# VC8E.net
KiCad netlist of a schematic drawn in EAGLE
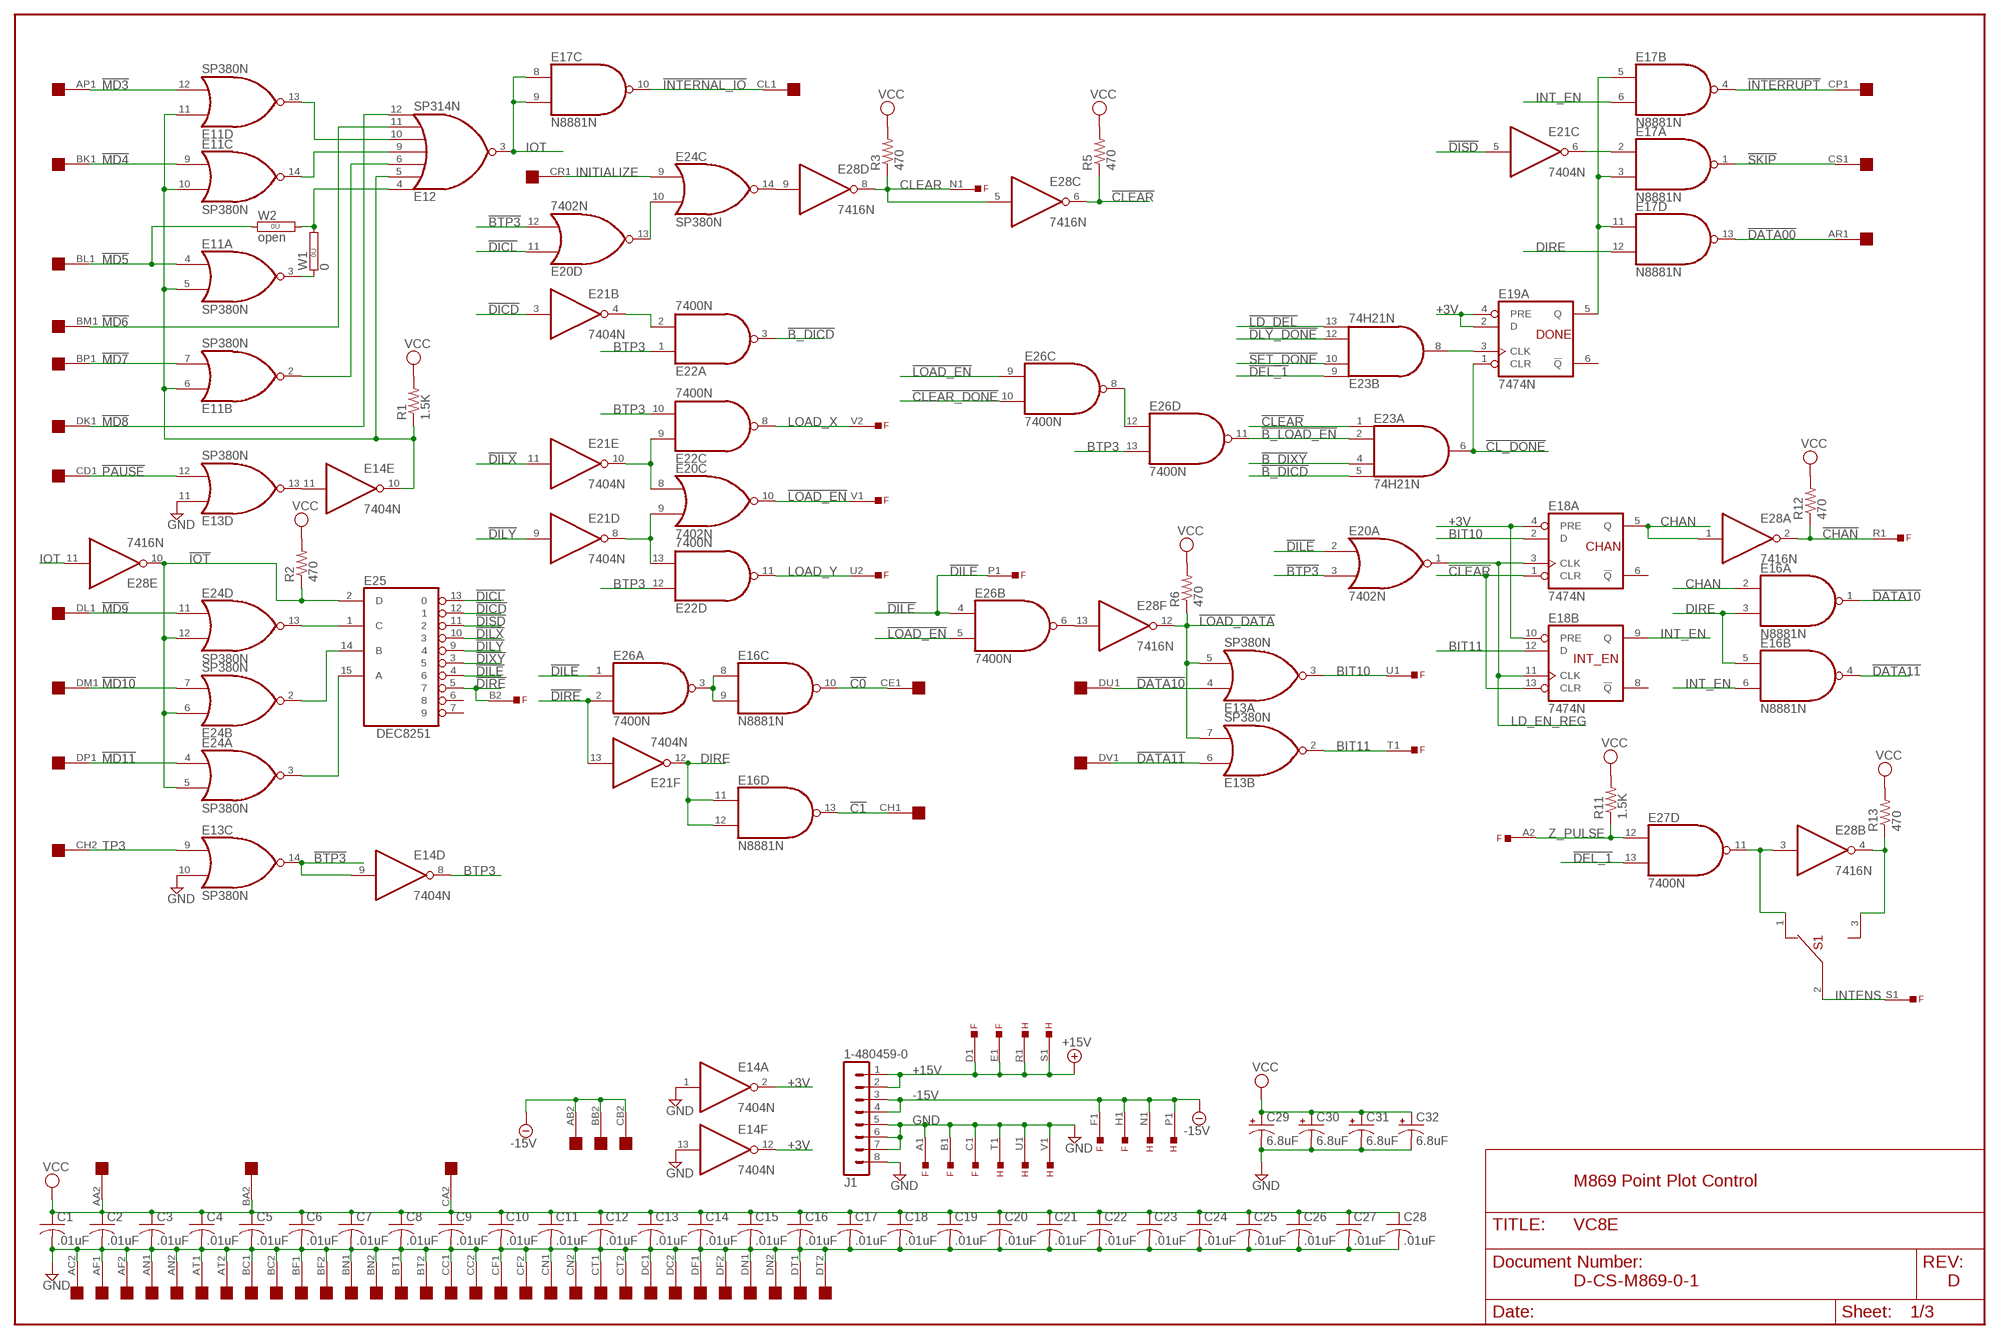
[diagram p0: schematic, sheet 1]
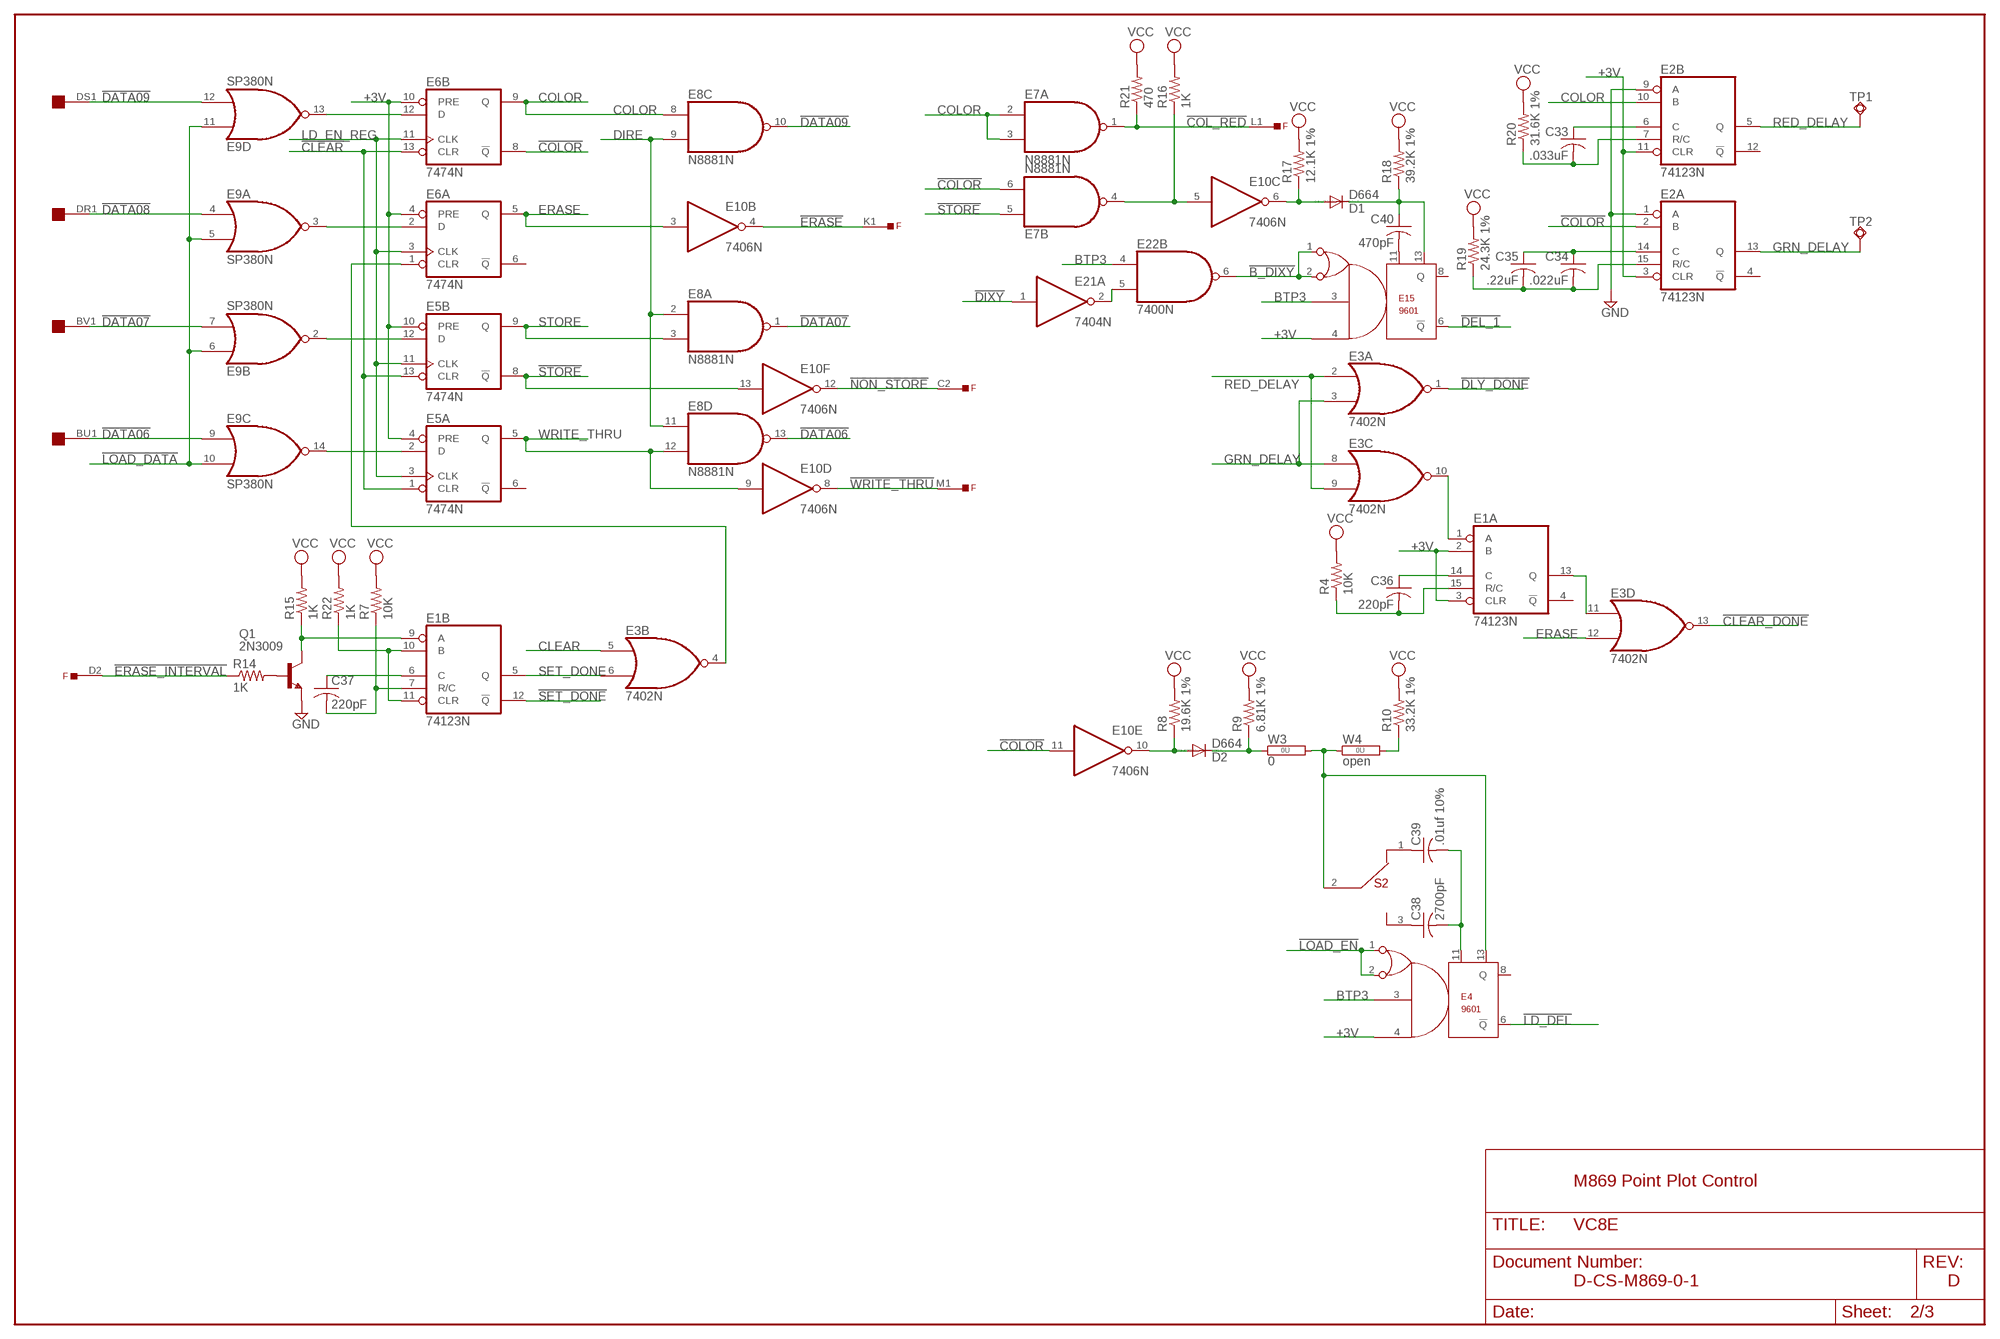
[diagram p1: schematic, sheet 2]
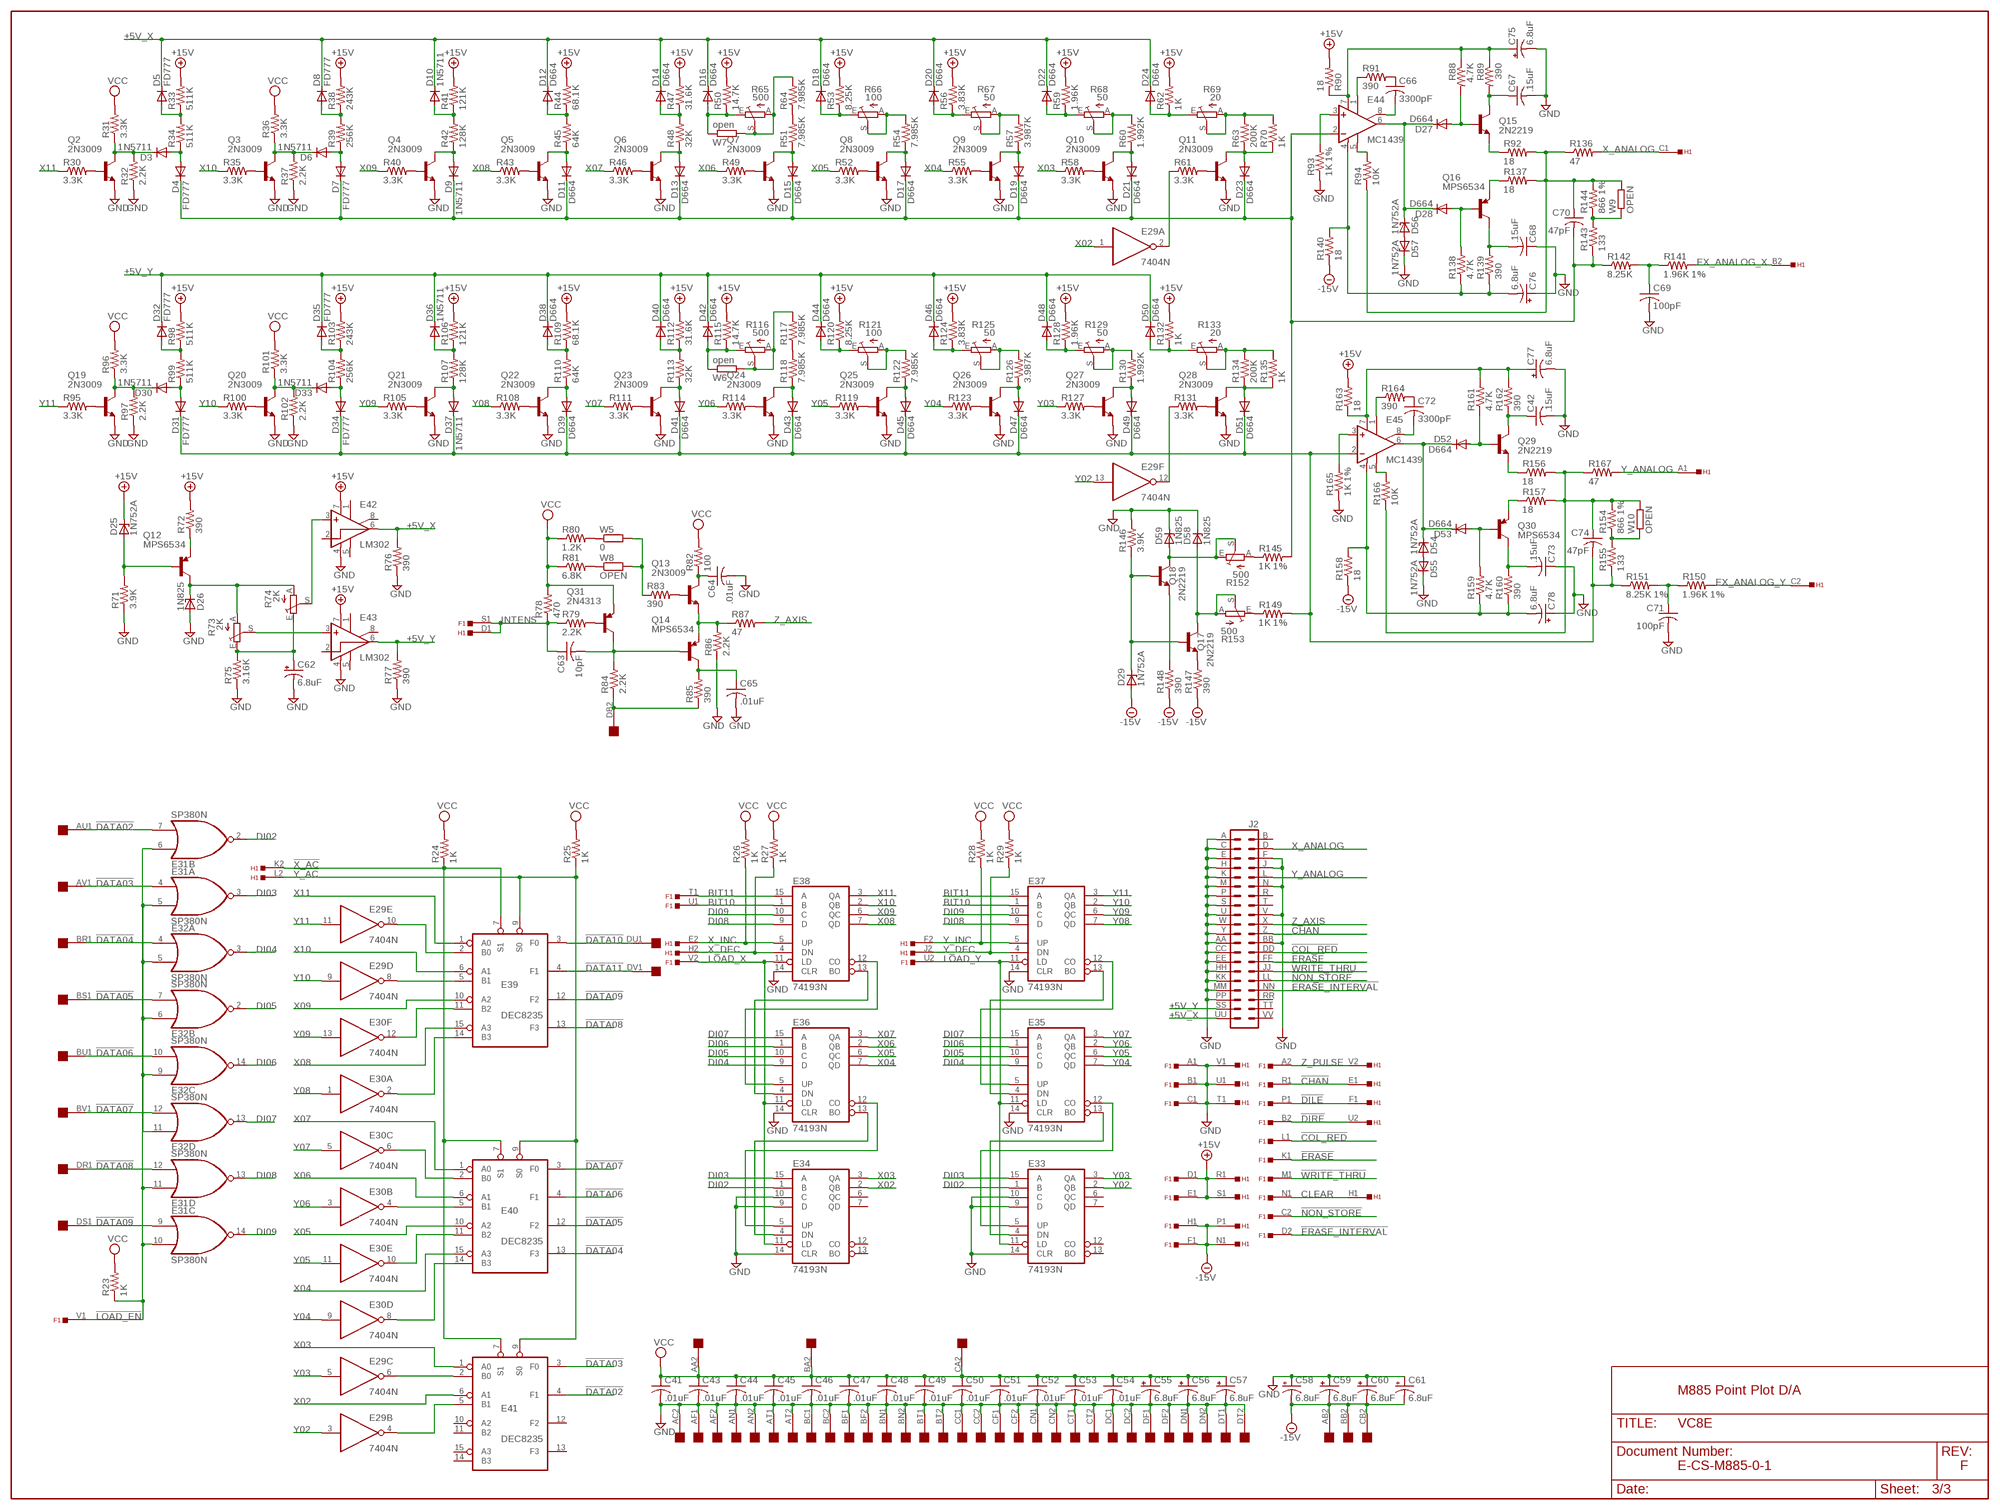
[diagram p2: schematic, sheet 3]

(export (version "E")
  (design (tool "Eeschema 10.0.6"))
  (components
    (comp (ref "C41")
      (value ".01uF")
      (footprint "eagle-import:C063-025X075")
      (libsource (lib "eagle-import") (part "C-US"))
    )
    (comp (ref "C42")
      (value ".15uF")
      (footprint "eagle-import:C150-054X183")
      (libsource (lib "eagle-import") (part "C-US150-054X183"))
    )
    (comp (ref "C43")
      (value ".01uF")
      (footprint "eagle-import:C063-025X075")
      (libsource (lib "eagle-import") (part "C-US"))
    )
    (comp (ref "C44")
      (value ".01uF")
      (footprint "eagle-import:C063-025X075")
      (libsource (lib "eagle-import") (part "C-US"))
    )
    (comp (ref "C45")
      (value ".01uF")
      (footprint "eagle-import:C063-025X075")
      (libsource (lib "eagle-import") (part "C-US"))
    )
    (comp (ref "C46")
      (value ".01uF")
      (footprint "eagle-import:C063-025X075")
      (libsource (lib "eagle-import") (part "C-US"))
    )
    (comp (ref "C47")
      (value ".01uF")
      (footprint "eagle-import:C063-025X075")
      (libsource (lib "eagle-import") (part "C-US"))
    )
    (comp (ref "C48")
      (value ".01uF")
      (footprint "eagle-import:C063-025X075")
      (libsource (lib "eagle-import") (part "C-US"))
    )
    (comp (ref "C49")
      (value ".01uF")
      (footprint "eagle-import:C063-025X075")
      (libsource (lib "eagle-import") (part "C-US"))
    )
    (comp (ref "C50")
      (value ".01uF")
      (footprint "eagle-import:C063-025X075")
      (libsource (lib "eagle-import") (part "C-US"))
    )
    (comp (ref "C51")
      (value ".01uF")
      (footprint "eagle-import:C063-025X075")
      (libsource (lib "eagle-import") (part "C-US"))
    )
    (comp (ref "C52")
      (value ".01uF")
      (footprint "eagle-import:C063-025X075")
      (libsource (lib "eagle-import") (part "C-US"))
    )
    (comp (ref "C53")
      (value ".01uF")
      (footprint "eagle-import:C063-025X075")
      (libsource (lib "eagle-import") (part "C-US"))
    )
    (comp (ref "C54")
      (value ".01uF")
      (footprint "eagle-import:C063-025X075")
      (libsource (lib "eagle-import") (part "C-US"))
    )
    (comp (ref "C55")
      (value "6.8uF")
      (footprint "eagle-import:E12-8")
      (libsource (lib "eagle-import") (part "CPOL-USE20-8AXIAL"))
    )
    (comp (ref "C56")
      (value "6.8uF")
      (footprint "eagle-import:E12-8")
      (libsource (lib "eagle-import") (part "CPOL-USE20-8AXIAL"))
    )
    (comp (ref "C57")
      (value "6.8uF")
      (footprint "eagle-import:E12-8")
      (libsource (lib "eagle-import") (part "CPOL-USE20-8AXIAL"))
    )
    (comp (ref "C58")
      (value "6.8uF")
      (footprint "eagle-import:E12-8")
      (libsource (lib "eagle-import") (part "CPOL-USE20-8AXIAL"))
    )
    (comp (ref "C59")
      (value "6.8uF")
      (footprint "eagle-import:E12-8")
      (libsource (lib "eagle-import") (part "CPOL-USE20-8AXIAL"))
    )
    (comp (ref "C60")
      (value "6.8uF")
      (footprint "eagle-import:E12-8")
      (libsource (lib "eagle-import") (part "CPOL-USE20-8AXIAL"))
    )
    (comp (ref "C61")
      (value "6.8uF")
      (footprint "eagle-import:E12-8")
      (libsource (lib "eagle-import") (part "CPOL-USE20-8AXIAL"))
    )
    (comp (ref "C62")
      (value "6.8uF")
      (footprint "eagle-import:E12-8")
      (libsource (lib "eagle-import") (part "CPOL-USE20-8AXIAL"))
    )
    (comp (ref "C63")
      (value "10pF")
      (footprint "eagle-import:C063-025X075")
      (libsource (lib "eagle-import") (part "C-US"))
    )
    (comp (ref "C64")
      (value ".01uF")
      (footprint "eagle-import:C063-025X075")
      (libsource (lib "eagle-import") (part "C-US"))
    )
    (comp (ref "C65")
      (value ".01uF")
      (footprint "eagle-import:C063-025X075")
      (libsource (lib "eagle-import") (part "C-US"))
    )
    (comp (ref "C66")
      (value "3300pF")
      (footprint "eagle-import:C150-054X183")
      (libsource (lib "eagle-import") (part "C-US150-054X183"))
    )
    (comp (ref "C67")
      (value ".15uF")
      (footprint "eagle-import:C150-054X183")
      (libsource (lib "eagle-import") (part "C-US150-054X183"))
    )
    (comp (ref "C68")
      (value ".15uF")
      (footprint "eagle-import:C150-054X183")
      (libsource (lib "eagle-import") (part "C-US150-054X183"))
    )
    (comp (ref "C69")
      (value "100pF")
      (footprint "eagle-import:C063-025X075")
      (libsource (lib "eagle-import") (part "C-US"))
    )
    (comp (ref "C70")
      (value "47pF")
      (footprint "eagle-import:C063-025X075")
      (libsource (lib "eagle-import") (part "C-US"))
    )
    (comp (ref "C71")
      (value "100pF")
      (footprint "eagle-import:C063-025X075")
      (libsource (lib "eagle-import") (part "C-US"))
    )
    (comp (ref "C72")
      (value "3300pF")
      (footprint "eagle-import:C150-054X183")
      (libsource (lib "eagle-import") (part "C-US150-054X183"))
    )
    (comp (ref "C73")
      (value ".15uF")
      (footprint "eagle-import:C150-054X183")
      (libsource (lib "eagle-import") (part "C-US150-054X183"))
    )
    (comp (ref "C74")
      (value "47pF")
      (footprint "eagle-import:C063-025X075")
      (libsource (lib "eagle-import") (part "C-US"))
    )
    (comp (ref "C75")
      (value "6.8uF")
      (footprint "eagle-import:E12-8")
      (libsource (lib "eagle-import") (part "CPOL-USE20-8AXIAL"))
    )
    (comp (ref "C76")
      (value "6.8uF")
      (footprint "eagle-import:E12-8")
      (libsource (lib "eagle-import") (part "CPOL-USE20-8AXIAL"))
    )
    (comp (ref "C77")
      (value "6.8uF")
      (footprint "eagle-import:E12-8")
      (libsource (lib "eagle-import") (part "CPOL-USE20-8AXIAL"))
    )
    (comp (ref "C78")
      (value "6.8uF")
      (footprint "eagle-import:E12-8")
      (libsource (lib "eagle-import") (part "CPOL-USE20-8AXIAL"))
    )
    (comp (ref "D3")
      (value "1N5711")
      (footprint "eagle-import:DO35-10")
      (libsource (lib "eagle-import") (part "DIODE-DO35-10"))
    )
    (comp (ref "D4")
      (value "FD777")
      (footprint "eagle-import:DO35-10")
      (libsource (lib "eagle-import") (part "DIODE-DO35-10"))
    )
    (comp (ref "D5")
      (value "FD777")
      (footprint "eagle-import:DO35-10")
      (libsource (lib "eagle-import") (part "DIODE-DO35-10"))
    )
    (comp (ref "D6")
      (value "1N5711")
      (footprint "eagle-import:DO35-10")
      (libsource (lib "eagle-import") (part "DIODE-DO35-10"))
    )
    (comp (ref "D7")
      (value "FD777")
      (footprint "eagle-import:DO35-10")
      (libsource (lib "eagle-import") (part "DIODE-DO35-10"))
    )
    (comp (ref "D8")
      (value "FD777")
      (footprint "eagle-import:DO35-10")
      (libsource (lib "eagle-import") (part "DIODE-DO35-10"))
    )
    (comp (ref "D9")
      (value "1N5711")
      (footprint "eagle-import:DO35-10")
      (libsource (lib "eagle-import") (part "DIODE-DO35-10"))
    )
    (comp (ref "D10")
      (value "1N5711")
      (footprint "eagle-import:DO35-10")
      (libsource (lib "eagle-import") (part "DIODE-DO35-10"))
    )
    (comp (ref "D11")
      (value "D664")
      (footprint "eagle-import:DO35-10")
      (libsource (lib "eagle-import") (part "DIODE-DO35-10"))
    )
    (comp (ref "D12")
      (value "D664")
      (footprint "eagle-import:DO35-10")
      (libsource (lib "eagle-import") (part "DIODE-DO35-10"))
    )
    (comp (ref "D13")
      (value "D664")
      (footprint "eagle-import:DO35-10")
      (libsource (lib "eagle-import") (part "DIODE-DO35-10"))
    )
    (comp (ref "D14")
      (value "D664")
      (footprint "eagle-import:DO35-10")
      (libsource (lib "eagle-import") (part "DIODE-DO35-10"))
    )
    (comp (ref "D15")
      (value "D664")
      (footprint "eagle-import:DO35-10")
      (libsource (lib "eagle-import") (part "DIODE-DO35-10"))
    )
    (comp (ref "D16")
      (value "D664")
      (footprint "eagle-import:DO35-10")
      (libsource (lib "eagle-import") (part "DIODE-DO35-10"))
    )
    (comp (ref "D17")
      (value "D664")
      (footprint "eagle-import:DO35-10")
      (libsource (lib "eagle-import") (part "DIODE-DO35-10"))
    )
    (comp (ref "D18")
      (value "D664")
      (footprint "eagle-import:DO35-10")
      (libsource (lib "eagle-import") (part "DIODE-DO35-10"))
    )
    (comp (ref "D19")
      (value "D664")
      (footprint "eagle-import:DO35-10")
      (libsource (lib "eagle-import") (part "DIODE-DO35-10"))
    )
    (comp (ref "D20")
      (value "D664")
      (footprint "eagle-import:DO35-10")
      (libsource (lib "eagle-import") (part "DIODE-DO35-10"))
    )
    (comp (ref "D21")
      (value "D664")
      (footprint "eagle-import:DO35-10")
      (libsource (lib "eagle-import") (part "DIODE-DO35-10"))
    )
    (comp (ref "D22")
      (value "D664")
      (footprint "eagle-import:DO35-10")
      (libsource (lib "eagle-import") (part "DIODE-DO35-10"))
    )
    (comp (ref "D23")
      (value "D664")
      (footprint "eagle-import:DO35-10")
      (libsource (lib "eagle-import") (part "DIODE-DO35-10"))
    )
    (comp (ref "D24")
      (value "D664")
      (footprint "eagle-import:DO35-10")
      (libsource (lib "eagle-import") (part "DIODE-DO35-10"))
    )
    (comp (ref "D25")
      (value "1N752A")
      (footprint "eagle-import:DO35Z10")
      (libsource (lib "eagle-import") (part "ZENER-DIODEDO35Z10"))
    )
    (comp (ref "D26")
      (value "1N825")
      (footprint "eagle-import:DO35Z10")
      (libsource (lib "eagle-import") (part "ZENER-DIODEDO35Z10"))
    )
    (comp (ref "D27")
      (value "D664")
      (footprint "eagle-import:DO35-10")
      (libsource (lib "eagle-import") (part "DIODE-DO35-10"))
    )
    (comp (ref "D28")
      (value "D664")
      (footprint "eagle-import:DO35-10")
      (libsource (lib "eagle-import") (part "DIODE-DO35-10"))
    )
    (comp (ref "D29")
      (value "1N752A")
      (footprint "eagle-import:DO35Z10")
      (libsource (lib "eagle-import") (part "ZENER-DIODEDO35Z10"))
    )
    (comp (ref "D30")
      (value "1N5711")
      (footprint "eagle-import:DO35-10")
      (libsource (lib "eagle-import") (part "DIODE-DO35-10"))
    )
    (comp (ref "D31")
      (value "FD777")
      (footprint "eagle-import:DO35-10")
      (libsource (lib "eagle-import") (part "DIODE-DO35-10"))
    )
    (comp (ref "D32")
      (value "FD777")
      (footprint "eagle-import:DO35-10")
      (libsource (lib "eagle-import") (part "DIODE-DO35-10"))
    )
    (comp (ref "D33")
      (value "1N5711")
      (footprint "eagle-import:DO35-10")
      (libsource (lib "eagle-import") (part "DIODE-DO35-10"))
    )
    (comp (ref "D34")
      (value "FD777")
      (footprint "eagle-import:DO35-10")
      (libsource (lib "eagle-import") (part "DIODE-DO35-10"))
    )
    (comp (ref "D35")
      (value "FD777")
      (footprint "eagle-import:DO35-10")
      (libsource (lib "eagle-import") (part "DIODE-DO35-10"))
    )
    (comp (ref "D36")
      (value "1N5711")
      (footprint "eagle-import:DO35-10")
      (libsource (lib "eagle-import") (part "DIODE-DO35-10"))
    )
    (comp (ref "D37")
      (value "1N5711")
      (footprint "eagle-import:DO35-10")
      (libsource (lib "eagle-import") (part "DIODE-DO35-10"))
    )
    (comp (ref "D38")
      (value "D664")
      (footprint "eagle-import:DO35-10")
      (libsource (lib "eagle-import") (part "DIODE-DO35-10"))
    )
    (comp (ref "D39")
      (value "D664")
      (footprint "eagle-import:DO35-10")
      (libsource (lib "eagle-import") (part "DIODE-DO35-10"))
    )
    (comp (ref "D40")
      (value "D664")
      (footprint "eagle-import:DO35-10")
      (libsource (lib "eagle-import") (part "DIODE-DO35-10"))
    )
    (comp (ref "D41")
      (value "D664")
      (footprint "eagle-import:DO35-10")
      (libsource (lib "eagle-import") (part "DIODE-DO35-10"))
    )
    (comp (ref "D42")
      (value "D664")
      (footprint "eagle-import:DO35-10")
      (libsource (lib "eagle-import") (part "DIODE-DO35-10"))
    )
    (comp (ref "D43")
      (value "D664")
      (footprint "eagle-import:DO35-10")
      (libsource (lib "eagle-import") (part "DIODE-DO35-10"))
    )
    (comp (ref "D44")
      (value "D664")
      (footprint "eagle-import:DO35-10")
      (libsource (lib "eagle-import") (part "DIODE-DO35-10"))
    )
    (comp (ref "D45")
      (value "D664")
      (footprint "eagle-import:DO35-10")
      (libsource (lib "eagle-import") (part "DIODE-DO35-10"))
    )
    (comp (ref "D46")
      (value "D664")
      (footprint "eagle-import:DO35-10")
      (libsource (lib "eagle-import") (part "DIODE-DO35-10"))
    )
    (comp (ref "D47")
      (value "D664")
      (footprint "eagle-import:DO35-10")
      (libsource (lib "eagle-import") (part "DIODE-DO35-10"))
    )
    (comp (ref "D48")
      (value "D664")
      (footprint "eagle-import:DO35-10")
      (libsource (lib "eagle-import") (part "DIODE-DO35-10"))
    )
    (comp (ref "D49")
      (value "D664")
      (footprint "eagle-import:DO35-10")
      (libsource (lib "eagle-import") (part "DIODE-DO35-10"))
    )
    (comp (ref "D50")
      (value "D664")
      (footprint "eagle-import:DO35-10")
      (libsource (lib "eagle-import") (part "DIODE-DO35-10"))
    )
    (comp (ref "D51")
      (value "D664")
      (footprint "eagle-import:DO35-10")
      (libsource (lib "eagle-import") (part "DIODE-DO35-10"))
    )
    (comp (ref "D52")
      (value "D664")
      (footprint "eagle-import:DO35-10")
      (libsource (lib "eagle-import") (part "DIODE-DO35-10"))
    )
    (comp (ref "D53")
      (value "D664")
      (footprint "eagle-import:DO35-10")
      (libsource (lib "eagle-import") (part "DIODE-DO35-10"))
    )
    (comp (ref "D54")
      (value "1N752A")
      (footprint "eagle-import:DO35Z10")
      (libsource (lib "eagle-import") (part "ZENER-DIODEDO35Z10"))
    )
    (comp (ref "D55")
      (value "1N752A")
      (footprint "eagle-import:DO35Z10")
      (libsource (lib "eagle-import") (part "ZENER-DIODEDO35Z10"))
    )
    (comp (ref "D56")
      (value "1N752A")
      (footprint "eagle-import:DO35Z10")
      (libsource (lib "eagle-import") (part "ZENER-DIODEDO35Z10"))
    )
    (comp (ref "D57")
      (value "1N752A")
      (footprint "eagle-import:DO35Z10")
      (libsource (lib "eagle-import") (part "ZENER-DIODEDO35Z10"))
    )
    (comp (ref "D58")
      (value "1N825")
      (footprint "eagle-import:DO35Z10")
      (libsource (lib "eagle-import") (part "ZENER-DIODEDO35Z10"))
    )
    (comp (ref "D59")
      (value "1N825")
      (footprint "eagle-import:DO35Z10")
      (libsource (lib "eagle-import") (part "ZENER-DIODEDO35Z10"))
    )
    (comp (ref "E29")
      (value "7404N")
      (footprint "eagle-import:DIL14")
      (libsource (lib "eagle-import") (part "7404N"))
    )
    (comp (ref "E30")
      (value "7404N")
      (footprint "eagle-import:DIL14")
      (libsource (lib "eagle-import") (part "7404N"))
    )
    (comp (ref "E31")
      (value "SP380N")
      (footprint "eagle-import:DIL14")
      (libsource (lib "eagle-import") (part "SP380N"))
    )
    (comp (ref "E32")
      (value "SP380N")
      (footprint "eagle-import:DIL14")
      (libsource (lib "eagle-import") (part "SP380N"))
    )
    (comp (ref "E33")
      (value "74193N")
      (footprint "eagle-import:DIL16")
      (libsource (lib "eagle-import") (part "74193N"))
    )
    (comp (ref "E34")
      (value "74193N")
      (footprint "eagle-import:DIL16")
      (libsource (lib "eagle-import") (part "74193N"))
    )
    (comp (ref "E35")
      (value "74193N")
      (footprint "eagle-import:DIL16")
      (libsource (lib "eagle-import") (part "74193N"))
    )
    (comp (ref "E36")
      (value "74193N")
      (footprint "eagle-import:DIL16")
      (libsource (lib "eagle-import") (part "74193N"))
    )
    (comp (ref "E37")
      (value "74193N")
      (footprint "eagle-import:DIL16")
      (libsource (lib "eagle-import") (part "74193N"))
    )
    (comp (ref "E38")
      (value "74193N")
      (footprint "eagle-import:DIL16")
      (libsource (lib "eagle-import") (part "74193N"))
    )
    (comp (ref "E39")
      (value "DEC8235")
      (footprint "eagle-import:DIL16")
      (libsource (lib "eagle-import") (part "DEC8235"))
    )
    (comp (ref "E40")
      (value "DEC8235")
      (footprint "eagle-import:DIL16")
      (libsource (lib "eagle-import") (part "DEC8235"))
    )
    (comp (ref "E41")
      (value "DEC8235")
      (footprint "eagle-import:DIL16")
      (libsource (lib "eagle-import") (part "DEC8235"))
    )
    (comp (ref "E42")
      (value "LM302")
      (footprint "eagle-import:TO99")
      (libsource (lib "eagle-import") (part "AD504H"))
    )
    (comp (ref "E43")
      (value "LM302")
      (footprint "eagle-import:TO99")
      (libsource (lib "eagle-import") (part "AD504H"))
    )
    (comp (ref "E44")
      (value "MC1439")
      (footprint "eagle-import:TO99")
      (libsource (lib "eagle-import") (part "AD504H"))
    )
    (comp (ref "E45")
      (value "MC1439")
      (footprint "eagle-import:TO99")
      (libsource (lib "eagle-import") (part "AD504H"))
    )
    (comp (ref "F1")
      (value "EDGE-TOP")
      (footprint "eagle-import:EDGE-CON2")
      (libsource (lib "eagle-import") (part "EDGE-TOP"))
    )
    (comp (ref "H1")
      (value "EDGE-TOP")
      (footprint "eagle-import:EDGE-CON2")
      (libsource (lib "eagle-import") (part "EDGE-TOP"))
    )
    (comp (ref "J2")
      (value "DEC40PINH")
      (footprint "eagle-import:DEC40PINH")
      (libsource (lib "eagle-import") (part "DEC40PINH"))
    )
    (comp (ref "OMNIBUS1")
      (value "QUAD")
      (footprint "eagle-import:EDGE-CON8")
      (libsource (lib "eagle-import") (part "QUAD"))
    )
    (comp (ref "Q2")
      (value "2N3009")
      (footprint "eagle-import:TO5")
      (libsource (lib "eagle-import") (part "-NPN-TO5"))
    )
    (comp (ref "Q3")
      (value "2N3009")
      (footprint "eagle-import:TO5")
      (libsource (lib "eagle-import") (part "-NPN-TO5"))
    )
    (comp (ref "Q4")
      (value "2N3009")
      (footprint "eagle-import:TO5")
      (libsource (lib "eagle-import") (part "-NPN-TO5"))
    )
    (comp (ref "Q5")
      (value "2N3009")
      (footprint "eagle-import:TO5")
      (libsource (lib "eagle-import") (part "-NPN-TO5"))
    )
    (comp (ref "Q6")
      (value "2N3009")
      (footprint "eagle-import:TO5")
      (libsource (lib "eagle-import") (part "-NPN-TO5"))
    )
    (comp (ref "Q7")
      (value "2N3009")
      (footprint "eagle-import:TO5")
      (libsource (lib "eagle-import") (part "-NPN-TO5"))
    )
    (comp (ref "Q8")
      (value "2N3009")
      (footprint "eagle-import:TO5")
      (libsource (lib "eagle-import") (part "-NPN-TO5"))
    )
    (comp (ref "Q9")
      (value "2N3009")
      (footprint "eagle-import:TO5")
      (libsource (lib "eagle-import") (part "-NPN-TO5"))
    )
    (comp (ref "Q10")
      (value "2N3009")
      (footprint "eagle-import:TO5")
      (libsource (lib "eagle-import") (part "-NPN-TO5"))
    )
    (comp (ref "Q11")
      (value "2N3009")
      (footprint "eagle-import:TO5")
      (libsource (lib "eagle-import") (part "-NPN-TO5"))
    )
    (comp (ref "Q12")
      (value "MPS6534")
      (footprint "eagle-import:TO5")
      (libsource (lib "eagle-import") (part "-PNP-TO5"))
    )
    (comp (ref "Q13")
      (value "2N3009")
      (footprint "eagle-import:TO5")
      (libsource (lib "eagle-import") (part "-NPN-TO5"))
    )
    (comp (ref "Q14")
      (value "MPS6534")
      (footprint "eagle-import:TO5")
      (libsource (lib "eagle-import") (part "-PNP-TO5"))
    )
    (comp (ref "Q15")
      (value "2N2219")
      (footprint "eagle-import:TO5")
      (libsource (lib "eagle-import") (part "-NPN-TO5"))
    )
    (comp (ref "Q16")
      (value "MPS6534")
      (footprint "eagle-import:TO5")
      (libsource (lib "eagle-import") (part "-PNP-TO5"))
    )
    (comp (ref "Q17")
      (value "2N2219")
      (footprint "eagle-import:TO5")
      (libsource (lib "eagle-import") (part "-NPN-TO5"))
    )
    (comp (ref "Q18")
      (value "2N2219")
      (footprint "eagle-import:TO5")
      (libsource (lib "eagle-import") (part "-NPN-TO5"))
    )
    (comp (ref "Q19")
      (value "2N3009")
      (footprint "eagle-import:TO5")
      (libsource (lib "eagle-import") (part "-NPN-TO5"))
    )
    (comp (ref "Q20")
      (value "2N3009")
      (footprint "eagle-import:TO5")
      (libsource (lib "eagle-import") (part "-NPN-TO5"))
    )
    (comp (ref "Q21")
      (value "2N3009")
      (footprint "eagle-import:TO5")
      (libsource (lib "eagle-import") (part "-NPN-TO5"))
    )
    (comp (ref "Q22")
      (value "2N3009")
      (footprint "eagle-import:TO5")
      (libsource (lib "eagle-import") (part "-NPN-TO5"))
    )
    (comp (ref "Q23")
      (value "2N3009")
      (footprint "eagle-import:TO5")
      (libsource (lib "eagle-import") (part "-NPN-TO5"))
    )
    (comp (ref "Q24")
      (value "2N3009")
      (footprint "eagle-import:TO5")
      (libsource (lib "eagle-import") (part "-NPN-TO5"))
    )
    (comp (ref "Q25")
      (value "2N3009")
      (footprint "eagle-import:TO5")
      (libsource (lib "eagle-import") (part "-NPN-TO5"))
    )
    (comp (ref "Q26")
      (value "2N3009")
      (footprint "eagle-import:TO5")
      (libsource (lib "eagle-import") (part "-NPN-TO5"))
    )
    (comp (ref "Q27")
      (value "2N3009")
      (footprint "eagle-import:TO5")
      (libsource (lib "eagle-import") (part "-NPN-TO5"))
    )
    (comp (ref "Q28")
      (value "2N3009")
      (footprint "eagle-import:TO5")
      (libsource (lib "eagle-import") (part "-NPN-TO5"))
    )
    (comp (ref "Q29")
      (value "2N2219")
      (footprint "eagle-import:TO5")
      (libsource (lib "eagle-import") (part "-NPN-TO5"))
    )
    (comp (ref "Q30")
      (value "MPS6534")
      (footprint "eagle-import:TO5")
      (libsource (lib "eagle-import") (part "-PNP-TO5"))
    )
    (comp (ref "Q31")
      (value "2N4313")
      (footprint "eagle-import:TO5")
      (libsource (lib "eagle-import") (part "-PNP-TO5"))
    )
    (comp (ref "R23")
      (value "1K")
      (footprint "eagle-import:0207_10")
      (libsource (lib "eagle-import") (part "R-US_0207/10"))
    )
    (comp (ref "R24")
      (value "1K")
      (footprint "eagle-import:0207_10")
      (libsource (lib "eagle-import") (part "R-US_0207/10"))
    )
    (comp (ref "R25")
      (value "1K")
      (footprint "eagle-import:0207_10")
      (libsource (lib "eagle-import") (part "R-US_0207/10"))
    )
    (comp (ref "R26")
      (value "1K")
      (footprint "eagle-import:0207_10")
      (libsource (lib "eagle-import") (part "R-US_0207/10"))
    )
    (comp (ref "R27")
      (value "1K")
      (footprint "eagle-import:0207_10")
      (libsource (lib "eagle-import") (part "R-US_0207/10"))
    )
    (comp (ref "R28")
      (value "1K")
      (footprint "eagle-import:0207_10")
      (libsource (lib "eagle-import") (part "R-US_0207/10"))
    )
    (comp (ref "R29")
      (value "1K")
      (footprint "eagle-import:0207_10")
      (libsource (lib "eagle-import") (part "R-US_0207/10"))
    )
    (comp (ref "R30")
      (value "3.3K")
      (footprint "eagle-import:0207_10")
      (libsource (lib "eagle-import") (part "R-US_0207/10"))
    )
    (comp (ref "R31")
      (value "3.3K")
      (footprint "eagle-import:0207_10")
      (libsource (lib "eagle-import") (part "R-US_0207/10"))
    )
    (comp (ref "R32")
      (value "2.2K")
      (footprint "eagle-import:0207_10")
      (libsource (lib "eagle-import") (part "R-US_0207/10"))
    )
    (comp (ref "R33")
      (value "511K")
      (footprint "eagle-import:0207_15")
      (libsource (lib "eagle-import") (part "R-US_0207/15"))
    )
    (comp (ref "R34")
      (value "511K")
      (footprint "eagle-import:0207_15")
      (libsource (lib "eagle-import") (part "R-US_0207/15"))
    )
    (comp (ref "R35")
      (value "3.3K")
      (footprint "eagle-import:0207_10")
      (libsource (lib "eagle-import") (part "R-US_0207/10"))
    )
    (comp (ref "R36")
      (value "3.3K")
      (footprint "eagle-import:0207_10")
      (libsource (lib "eagle-import") (part "R-US_0207/10"))
    )
    (comp (ref "R37")
      (value "2.2K")
      (footprint "eagle-import:0207_10")
      (libsource (lib "eagle-import") (part "R-US_0207/10"))
    )
    (comp (ref "R38")
      (value "243K")
      (footprint "eagle-import:0207_15")
      (libsource (lib "eagle-import") (part "R-US_0207/15"))
    )
    (comp (ref "R39")
      (value "256K")
      (footprint "eagle-import:0207_15")
      (libsource (lib "eagle-import") (part "R-US_0207/15"))
    )
    (comp (ref "R40")
      (value "3.3K")
      (footprint "eagle-import:0207_10")
      (libsource (lib "eagle-import") (part "R-US_0207/10"))
    )
    (comp (ref "R41")
      (value "121K")
      (footprint "eagle-import:0207_15")
      (libsource (lib "eagle-import") (part "R-US_0207/15"))
    )
    (comp (ref "R42")
      (value "128K")
      (footprint "eagle-import:0207_15")
      (libsource (lib "eagle-import") (part "R-US_0207/15"))
    )
    (comp (ref "R43")
      (value "3.3K")
      (footprint "eagle-import:0207_10")
      (libsource (lib "eagle-import") (part "R-US_0207/10"))
    )
    (comp (ref "R44")
      (value "68.1K")
      (footprint "eagle-import:0207_15")
      (libsource (lib "eagle-import") (part "R-US_0207/15"))
    )
    (comp (ref "R45")
      (value "64K")
      (footprint "eagle-import:0207_15")
      (libsource (lib "eagle-import") (part "R-US_0207/15"))
    )
    (comp (ref "R46")
      (value "3.3K")
      (footprint "eagle-import:0207_10")
      (libsource (lib "eagle-import") (part "R-US_0207/10"))
    )
    (comp (ref "R47")
      (value "31.6K")
      (footprint "eagle-import:0207_15")
      (libsource (lib "eagle-import") (part "R-US_0207/15"))
    )
    (comp (ref "R48")
      (value "32K")
      (footprint "eagle-import:0207_15")
      (libsource (lib "eagle-import") (part "R-US_0207/15"))
    )
    (comp (ref "R49")
      (value "3.3K")
      (footprint "eagle-import:0207_10")
      (libsource (lib "eagle-import") (part "R-US_0207/10"))
    )
    (comp (ref "R50")
      (value "14.7K")
      (footprint "eagle-import:0207_15")
      (libsource (lib "eagle-import") (part "R-US_0207/15"))
    )
    (comp (ref "R51")
      (value "7.985K")
      (footprint "eagle-import:0207_15")
      (libsource (lib "eagle-import") (part "R-US_0207/15"))
    )
    (comp (ref "R52")
      (value "3.3K")
      (footprint "eagle-import:0207_10")
      (libsource (lib "eagle-import") (part "R-US_0207/10"))
    )
    (comp (ref "R53")
      (value "8.25K")
      (footprint "eagle-import:0207_15")
      (libsource (lib "eagle-import") (part "R-US_0207/15"))
    )
    (comp (ref "R54")
      (value "7.985K")
      (footprint "eagle-import:0207_15")
      (libsource (lib "eagle-import") (part "R-US_0207/15"))
    )
    (comp (ref "R55")
      (value "3.3K")
      (footprint "eagle-import:0207_10")
      (libsource (lib "eagle-import") (part "R-US_0207/10"))
    )
    (comp (ref "R56")
      (value "3.83K")
      (footprint "eagle-import:0207_15")
      (libsource (lib "eagle-import") (part "R-US_0207/15"))
    )
    (comp (ref "R57")
      (value "3.987K")
      (footprint "eagle-import:0207_15")
      (libsource (lib "eagle-import") (part "R-US_0207/15"))
    )
    (comp (ref "R58")
      (value "3.3K")
      (footprint "eagle-import:0207_10")
      (libsource (lib "eagle-import") (part "R-US_0207/10"))
    )
    (comp (ref "R59")
      (value "1.96K")
      (footprint "eagle-import:0207_15")
      (libsource (lib "eagle-import") (part "R-US_0207/15"))
    )
    (comp (ref "R60")
      (value "1.992K")
      (footprint "eagle-import:0207_15")
      (libsource (lib "eagle-import") (part "R-US_0207/15"))
    )
    (comp (ref "R61")
      (value "3.3K")
      (footprint "eagle-import:0207_10")
      (libsource (lib "eagle-import") (part "R-US_0207/10"))
    )
    (comp (ref "R62")
      (value "1K")
      (footprint "eagle-import:0207_15")
      (libsource (lib "eagle-import") (part "R-US_0207/15"))
    )
    (comp (ref "R63")
      (value "200K")
      (footprint "eagle-import:0207_15")
      (libsource (lib "eagle-import") (part "R-US_0207/15"))
    )
    (comp (ref "R64")
      (value "7.985K")
      (footprint "eagle-import:0207_15")
      (libsource (lib "eagle-import") (part "R-US_0207/15"))
    )
    (comp (ref "R65")
      (value "500")
      (footprint "eagle-import:S75P")
      (libsource (lib "eagle-import") (part "TRIM_EU-S75P"))
    )
    (comp (ref "R66")
      (value "100")
      (footprint "eagle-import:S75P")
      (libsource (lib "eagle-import") (part "TRIM_EU-S75P"))
    )
    (comp (ref "R67")
      (value "50")
      (footprint "eagle-import:S75P")
      (libsource (lib "eagle-import") (part "TRIM_EU-S75P"))
    )
    (comp (ref "R68")
      (value "50")
      (footprint "eagle-import:S75P")
      (libsource (lib "eagle-import") (part "TRIM_EU-S75P"))
    )
    (comp (ref "R69")
      (value "20")
      (footprint "eagle-import:S75P")
      (libsource (lib "eagle-import") (part "TRIM_EU-S75P"))
    )
    (comp (ref "R70")
      (value "1K")
      (footprint "eagle-import:0207_15")
      (libsource (lib "eagle-import") (part "R-US_0207/15"))
    )
    (comp (ref "R71")
      (value "3.9K")
      (footprint "eagle-import:0207_10")
      (libsource (lib "eagle-import") (part "R-US_0207/10"))
    )
    (comp (ref "R72")
      (value "390")
      (footprint "eagle-import:0207_10")
      (libsource (lib "eagle-import") (part "R-US_0207/10"))
    )
    (comp (ref "R73")
      (value "2K")
      (footprint "eagle-import:SP19L")
      (libsource (lib "eagle-import") (part "TRIM_EU-B90P"))
    )
    (comp (ref "R74")
      (value "2K")
      (footprint "eagle-import:SP19L")
      (libsource (lib "eagle-import") (part "TRIM_EU-B90P"))
    )
    (comp (ref "R75")
      (value "3.16K")
      (footprint "eagle-import:0207_15")
      (libsource (lib "eagle-import") (part "R-US_0207/15"))
    )
    (comp (ref "R76")
      (value "390")
      (footprint "eagle-import:0207_10")
      (libsource (lib "eagle-import") (part "R-US_0207/10"))
    )
    (comp (ref "R77")
      (value "390")
      (footprint "eagle-import:0207_10")
      (libsource (lib "eagle-import") (part "R-US_0207/10"))
    )
    (comp (ref "R78")
      (value "470")
      (footprint "eagle-import:0207_10")
      (libsource (lib "eagle-import") (part "R-US_0207/10"))
    )
    (comp (ref "R79")
      (value "2.2K")
      (footprint "eagle-import:0207_10")
      (libsource (lib "eagle-import") (part "R-US_0207/10"))
    )
    (comp (ref "R80")
      (value "1.2K")
      (footprint "eagle-import:0207_10")
      (libsource (lib "eagle-import") (part "R-US_0207/10"))
    )
    (comp (ref "R81")
      (value "6.8K")
      (footprint "eagle-import:0207_10")
      (libsource (lib "eagle-import") (part "R-US_0207/10"))
    )
    (comp (ref "R82")
      (value "100")
      (footprint "eagle-import:0207_10")
      (libsource (lib "eagle-import") (part "R-US_0207/10"))
    )
    (comp (ref "R83")
      (value "390")
      (footprint "eagle-import:0207_10")
      (libsource (lib "eagle-import") (part "R-US_0207/10"))
    )
    (comp (ref "R84")
      (value "2.2K")
      (footprint "eagle-import:0207_10")
      (libsource (lib "eagle-import") (part "R-US_0207/10"))
    )
    (comp (ref "R85")
      (value "390")
      (footprint "eagle-import:0207_10")
      (libsource (lib "eagle-import") (part "R-US_0207/10"))
    )
    (comp (ref "R86")
      (value "2.2K")
      (footprint "eagle-import:0207_10")
      (libsource (lib "eagle-import") (part "R-US_0207/10"))
    )
    (comp (ref "R87")
      (value "47")
      (footprint "eagle-import:0207_10")
      (libsource (lib "eagle-import") (part "R-US_0207/10"))
    )
    (comp (ref "R88")
      (value "4.7K")
      (footprint "eagle-import:0207_10")
      (libsource (lib "eagle-import") (part "R-US_0207/10"))
    )
    (comp (ref "R89")
      (value "390")
      (footprint "eagle-import:0207_10")
      (libsource (lib "eagle-import") (part "R-US_0207/10"))
    )
    (comp (ref "R90")
      (value "18")
      (footprint "eagle-import:0207_10")
      (libsource (lib "eagle-import") (part "R-US_0207/10"))
    )
    (comp (ref "R91")
      (value "390")
      (footprint "eagle-import:0207_10")
      (libsource (lib "eagle-import") (part "R-US_0207/10"))
    )
    (comp (ref "R92")
      (value "18")
      (footprint "eagle-import:0207_10")
      (libsource (lib "eagle-import") (part "R-US_0207/10"))
    )
    (comp (ref "R93")
      (value "1K 1%")
      (footprint "eagle-import:0207_15")
      (libsource (lib "eagle-import") (part "R-US_0207/15"))
    )
    (comp (ref "R94")
      (value "10K")
      (footprint "eagle-import:0207_10")
      (libsource (lib "eagle-import") (part "R-US_0207/10"))
    )
    (comp (ref "R95")
      (value "3.3K")
      (footprint "eagle-import:0207_10")
      (libsource (lib "eagle-import") (part "R-US_0207/10"))
    )
    (comp (ref "R96")
      (value "3.3K")
      (footprint "eagle-import:0207_10")
      (libsource (lib "eagle-import") (part "R-US_0207/10"))
    )
    (comp (ref "R97")
      (value "2.2K")
      (footprint "eagle-import:0207_10")
      (libsource (lib "eagle-import") (part "R-US_0207/10"))
    )
    (comp (ref "R98")
      (value "511K")
      (footprint "eagle-import:0207_15")
      (libsource (lib "eagle-import") (part "R-US_0207/15"))
    )
    (comp (ref "R99")
      (value "511K")
      (footprint "eagle-import:0207_15")
      (libsource (lib "eagle-import") (part "R-US_0207/15"))
    )
    (comp (ref "R100")
      (value "3.3K")
      (footprint "eagle-import:0207_10")
      (libsource (lib "eagle-import") (part "R-US_0207/10"))
    )
    (comp (ref "R101")
      (value "3.3K")
      (footprint "eagle-import:0207_10")
      (libsource (lib "eagle-import") (part "R-US_0207/10"))
    )
    (comp (ref "R102")
      (value "2.2K")
      (footprint "eagle-import:0207_10")
      (libsource (lib "eagle-import") (part "R-US_0207/10"))
    )
    (comp (ref "R103")
      (value "243K")
      (footprint "eagle-import:0207_15")
      (libsource (lib "eagle-import") (part "R-US_0207/15"))
    )
    (comp (ref "R104")
      (value "256K")
      (footprint "eagle-import:0207_15")
      (libsource (lib "eagle-import") (part "R-US_0207/15"))
    )
    (comp (ref "R105")
      (value "3.3K")
      (footprint "eagle-import:0207_10")
      (libsource (lib "eagle-import") (part "R-US_0207/10"))
    )
    (comp (ref "R106")
      (value "121K")
      (footprint "eagle-import:0207_15")
      (libsource (lib "eagle-import") (part "R-US_0207/15"))
    )
    (comp (ref "R107")
      (value "128K")
      (footprint "eagle-import:0207_15")
      (libsource (lib "eagle-import") (part "R-US_0207/15"))
    )
    (comp (ref "R108")
      (value "3.3K")
      (footprint "eagle-import:0207_10")
      (libsource (lib "eagle-import") (part "R-US_0207/10"))
    )
    (comp (ref "R109")
      (value "68.1K")
      (footprint "eagle-import:0207_15")
      (libsource (lib "eagle-import") (part "R-US_0207/15"))
    )
    (comp (ref "R110")
      (value "64K")
      (footprint "eagle-import:0207_15")
      (libsource (lib "eagle-import") (part "R-US_0207/15"))
    )
    (comp (ref "R111")
      (value "3.3K")
      (footprint "eagle-import:0207_10")
      (libsource (lib "eagle-import") (part "R-US_0207/10"))
    )
    (comp (ref "R112")
      (value "31.6K")
      (footprint "eagle-import:0207_15")
      (libsource (lib "eagle-import") (part "R-US_0207/15"))
    )
    (comp (ref "R113")
      (value "32K")
      (footprint "eagle-import:0207_15")
      (libsource (lib "eagle-import") (part "R-US_0207/15"))
    )
    (comp (ref "R114")
      (value "3.3K")
      (footprint "eagle-import:0207_10")
      (libsource (lib "eagle-import") (part "R-US_0207/10"))
    )
    (comp (ref "R115")
      (value "14.7K")
      (footprint "eagle-import:0207_15")
      (libsource (lib "eagle-import") (part "R-US_0207/15"))
    )
    (comp (ref "R116")
      (value "500")
      (footprint "eagle-import:S75P")
      (libsource (lib "eagle-import") (part "TRIM_EU-S75P"))
    )
    (comp (ref "R117")
      (value "7.985K")
      (footprint "eagle-import:0207_15")
      (libsource (lib "eagle-import") (part "R-US_0207/15"))
    )
    (comp (ref "R118")
      (value "7.985K")
      (footprint "eagle-import:0207_15")
      (libsource (lib "eagle-import") (part "R-US_0207/15"))
    )
    (comp (ref "R119")
      (value "3.3K")
      (footprint "eagle-import:0207_10")
      (libsource (lib "eagle-import") (part "R-US_0207/10"))
    )
    (comp (ref "R120")
      (value "8.25K")
      (footprint "eagle-import:0207_15")
      (libsource (lib "eagle-import") (part "R-US_0207/15"))
    )
    (comp (ref "R121")
      (value "100")
      (footprint "eagle-import:S75P")
      (libsource (lib "eagle-import") (part "TRIM_EU-S75P"))
    )
    (comp (ref "R122")
      (value "7.985K")
      (footprint "eagle-import:0207_15")
      (libsource (lib "eagle-import") (part "R-US_0207/15"))
    )
    (comp (ref "R123")
      (value "3.3K")
      (footprint "eagle-import:0207_10")
      (libsource (lib "eagle-import") (part "R-US_0207/10"))
    )
    (comp (ref "R124")
      (value "3.83K")
      (footprint "eagle-import:0207_15")
      (libsource (lib "eagle-import") (part "R-US_0207/15"))
    )
    (comp (ref "R125")
      (value "50")
      (footprint "eagle-import:S75P")
      (libsource (lib "eagle-import") (part "TRIM_EU-S75P"))
    )
    (comp (ref "R126")
      (value "3.987K")
      (footprint "eagle-import:0207_15")
      (libsource (lib "eagle-import") (part "R-US_0207/15"))
    )
    (comp (ref "R127")
      (value "3.3K")
      (footprint "eagle-import:0207_10")
      (libsource (lib "eagle-import") (part "R-US_0207/10"))
    )
    (comp (ref "R128")
      (value "1.96K")
      (footprint "eagle-import:0207_15")
      (libsource (lib "eagle-import") (part "R-US_0207/15"))
    )
    (comp (ref "R129")
      (value "50")
      (footprint "eagle-import:S75P")
      (libsource (lib "eagle-import") (part "TRIM_EU-S75P"))
    )
    (comp (ref "R130")
      (value "1.992K")
      (footprint "eagle-import:0207_15")
      (libsource (lib "eagle-import") (part "R-US_0207/15"))
    )
    (comp (ref "R131")
      (value "3.3K")
      (footprint "eagle-import:0207_10")
      (libsource (lib "eagle-import") (part "R-US_0207/10"))
    )
    (comp (ref "R132")
      (value "1K")
      (footprint "eagle-import:0207_15")
      (libsource (lib "eagle-import") (part "R-US_0207/15"))
    )
    (comp (ref "R133")
      (value "20")
      (footprint "eagle-import:S75P")
      (libsource (lib "eagle-import") (part "TRIM_EU-S75P"))
    )
    (comp (ref "R134")
      (value "200K")
      (footprint "eagle-import:0207_15")
      (libsource (lib "eagle-import") (part "R-US_0207/15"))
    )
    (comp (ref "R135")
      (value "1K")
      (footprint "eagle-import:0207_15")
      (libsource (lib "eagle-import") (part "R-US_0207/15"))
    )
    (comp (ref "R136")
      (value "47")
      (footprint "eagle-import:0207_10")
      (libsource (lib "eagle-import") (part "R-US_0207/10"))
    )
    (comp (ref "R137")
      (value "18")
      (footprint "eagle-import:0207_10")
      (libsource (lib "eagle-import") (part "R-US_0207/10"))
    )
    (comp (ref "R138")
      (value "4.7K")
      (footprint "eagle-import:0207_10")
      (libsource (lib "eagle-import") (part "R-US_0207/10"))
    )
    (comp (ref "R139")
      (value "390")
      (footprint "eagle-import:0207_10")
      (libsource (lib "eagle-import") (part "R-US_0207/10"))
    )
    (comp (ref "R140")
      (value "18")
      (footprint "eagle-import:0207_10")
      (libsource (lib "eagle-import") (part "R-US_0207/10"))
    )
    (comp (ref "R141")
      (value "1.96K 1%")
      (footprint "eagle-import:0207_15")
      (libsource (lib "eagle-import") (part "R-US_0207/15"))
    )
    (comp (ref "R142")
      (value "8.25K")
      (footprint "eagle-import:0207_15")
      (libsource (lib "eagle-import") (part "R-US_0207/15"))
    )
    (comp (ref "R143")
      (value "133")
      (footprint "eagle-import:0207_15")
      (libsource (lib "eagle-import") (part "R-US_0207/15"))
    )
    (comp (ref "R144")
      (value "866 1%")
      (footprint "eagle-import:0207_15")
      (libsource (lib "eagle-import") (part "R-US_0207/15"))
    )
    (comp (ref "R145")
      (value "1K 1%")
      (footprint "eagle-import:0207_15")
      (libsource (lib "eagle-import") (part "R-US_0207/15"))
    )
    (comp (ref "R146")
      (value "3.9K")
      (footprint "eagle-import:0207_10")
      (libsource (lib "eagle-import") (part "R-US_0207/10"))
    )
    (comp (ref "R147")
      (value "390")
      (footprint "eagle-import:0207_10")
      (libsource (lib "eagle-import") (part "R-US_0207/10"))
    )
    (comp (ref "R148")
      (value "390")
      (footprint "eagle-import:0207_10")
      (libsource (lib "eagle-import") (part "R-US_0207/10"))
    )
    (comp (ref "R149")
      (value "1K 1%")
      (footprint "eagle-import:0207_15")
      (libsource (lib "eagle-import") (part "R-US_0207/15"))
    )
    (comp (ref "R150")
      (value "1.96K 1%")
      (footprint "eagle-import:0207_15")
      (libsource (lib "eagle-import") (part "R-US_0207/15"))
    )
    (comp (ref "R151")
      (value "8.25K 1%")
      (footprint "eagle-import:0207_10")
      (libsource (lib "eagle-import") (part "R-US_0207/10"))
    )
    (comp (ref "R152")
      (value "500")
      (footprint "eagle-import:SP19L")
      (libsource (lib "eagle-import") (part "TRIM_EU-B90P"))
    )
    (comp (ref "R153")
      (value "500")
      (footprint "eagle-import:SP19L")
      (libsource (lib "eagle-import") (part "TRIM_EU-B90P"))
    )
    (comp (ref "R154")
      (value "866 1%")
      (footprint "eagle-import:0207_15")
      (libsource (lib "eagle-import") (part "R-US_0207/15"))
    )
    (comp (ref "R155")
      (value "133")
      (footprint "eagle-import:0207_15")
      (libsource (lib "eagle-import") (part "R-US_0207/15"))
    )
    (comp (ref "R156")
      (value "18")
      (footprint "eagle-import:0207_10")
      (libsource (lib "eagle-import") (part "R-US_0207/10"))
    )
    (comp (ref "R157")
      (value "18")
      (footprint "eagle-import:0207_10")
      (libsource (lib "eagle-import") (part "R-US_0207/10"))
    )
    (comp (ref "R158")
      (value "18")
      (footprint "eagle-import:0207_10")
      (libsource (lib "eagle-import") (part "R-US_0207/10"))
    )
    (comp (ref "R159")
      (value "4.7K")
      (footprint "eagle-import:0207_10")
      (libsource (lib "eagle-import") (part "R-US_0207/10"))
    )
    (comp (ref "R160")
      (value "390")
      (footprint "eagle-import:0207_10")
      (libsource (lib "eagle-import") (part "R-US_0207/10"))
    )
    (comp (ref "R161")
      (value "4.7K")
      (footprint "eagle-import:0207_10")
      (libsource (lib "eagle-import") (part "R-US_0207/10"))
    )
    (comp (ref "R162")
      (value "390")
      (footprint "eagle-import:0207_10")
      (libsource (lib "eagle-import") (part "R-US_0207/10"))
    )
    (comp (ref "R163")
      (value "18")
      (footprint "eagle-import:0207_10")
      (libsource (lib "eagle-import") (part "R-US_0207/10"))
    )
    (comp (ref "R164")
      (value "390")
      (footprint "eagle-import:0207_10")
      (libsource (lib "eagle-import") (part "R-US_0207/10"))
    )
    (comp (ref "R165")
      (value "1K 1%")
      (footprint "eagle-import:0207_15")
      (libsource (lib "eagle-import") (part "R-US_0207/15"))
    )
    (comp (ref "R166")
      (value "10K")
      (footprint "eagle-import:0207_10")
      (libsource (lib "eagle-import") (part "R-US_0207/10"))
    )
    (comp (ref "R167")
      (value "47")
      (footprint "eagle-import:0207_10")
      (libsource (lib "eagle-import") (part "R-US_0207/10"))
    )
    (comp (ref "W5")
      (value "0")
      (footprint "eagle-import:0207_10")
      (libsource (lib "eagle-import") (part "R-EU_0207/10"))
    )
    (comp (ref "W6")
      (value "open")
      (footprint "eagle-import:0207_10")
      (libsource (lib "eagle-import") (part "R-EU_0207/10"))
    )
    (comp (ref "W7")
      (value "open")
      (footprint "eagle-import:0207_10")
      (libsource (lib "eagle-import") (part "R-EU_0207/10"))
    )
    (comp (ref "W8")
      (value "OPEN")
      (footprint "eagle-import:0207_10")
      (libsource (lib "eagle-import") (part "R-EU_0207/10"))
    )
    (comp (ref "W9")
      (value "OPEN")
      (footprint "eagle-import:0207_10")
      (libsource (lib "eagle-import") (part "R-EU_0207/10"))
    )
    (comp (ref "W10")
      (value "OPEN")
      (footprint "eagle-import:0207_10")
      (libsource (lib "eagle-import") (part "R-EU_0207/10"))
    )
    (comp (ref "C1")
      (value ".01uF")
      (footprint "eagle-import:C063-025X075")
      (libsource (lib "eagle-import") (part "C-US"))
    )
    (comp (ref "C2")
      (value ".01uF")
      (footprint "eagle-import:C063-025X075")
      (libsource (lib "eagle-import") (part "C-US"))
    )
    (comp (ref "C3")
      (value ".01uF")
      (footprint "eagle-import:C063-025X075")
      (libsource (lib "eagle-import") (part "C-US"))
    )
    (comp (ref "C4")
      (value ".01uF")
      (footprint "eagle-import:C063-025X075")
      (libsource (lib "eagle-import") (part "C-US"))
    )
    (comp (ref "C5")
      (value ".01uF")
      (footprint "eagle-import:C063-025X075")
      (libsource (lib "eagle-import") (part "C-US"))
    )
    (comp (ref "C6")
      (value ".01uF")
      (footprint "eagle-import:C063-025X075")
      (libsource (lib "eagle-import") (part "C-US"))
    )
    (comp (ref "C7")
      (value ".01uF")
      (footprint "eagle-import:C063-025X075")
      (libsource (lib "eagle-import") (part "C-US"))
    )
    (comp (ref "C8")
      (value ".01uF")
      (footprint "eagle-import:C063-025X075")
      (libsource (lib "eagle-import") (part "C-US"))
    )
    (comp (ref "C9")
      (value ".01uF")
      (footprint "eagle-import:C063-025X075")
      (libsource (lib "eagle-import") (part "C-US"))
    )
    (comp (ref "C10")
      (value ".01uF")
      (footprint "eagle-import:C063-025X075")
      (libsource (lib "eagle-import") (part "C-US"))
    )
    (comp (ref "C11")
      (value ".01uF")
      (footprint "eagle-import:C063-025X075")
      (libsource (lib "eagle-import") (part "C-US"))
    )
    (comp (ref "C12")
      (value ".01uF")
      (footprint "eagle-import:C063-025X075")
      (libsource (lib "eagle-import") (part "C-US"))
    )
    (comp (ref "C13")
      (value ".01uF")
      (footprint "eagle-import:C063-025X075")
      (libsource (lib "eagle-import") (part "C-US"))
    )
    (comp (ref "C14")
      (value ".01uF")
      (footprint "eagle-import:C063-025X075")
      (libsource (lib "eagle-import") (part "C-US"))
    )
    (comp (ref "C15")
      (value ".01uF")
      (footprint "eagle-import:C063-025X075")
      (libsource (lib "eagle-import") (part "C-US"))
    )
    (comp (ref "C16")
      (value ".01uF")
      (footprint "eagle-import:C063-025X075")
      (libsource (lib "eagle-import") (part "C-US"))
    )
    (comp (ref "C17")
      (value ".01uF")
      (footprint "eagle-import:C063-025X075")
      (libsource (lib "eagle-import") (part "C-US"))
    )
    (comp (ref "C18")
      (value ".01uF")
      (footprint "eagle-import:C063-025X075")
      (libsource (lib "eagle-import") (part "C-US"))
    )
    (comp (ref "C19")
      (value ".01uF")
      (footprint "eagle-import:C063-025X075")
      (libsource (lib "eagle-import") (part "C-US"))
    )
    (comp (ref "C20")
      (value ".01uF")
      (footprint "eagle-import:C063-025X075")
      (libsource (lib "eagle-import") (part "C-US"))
    )
    (comp (ref "C21")
      (value ".01uF")
      (footprint "eagle-import:C063-025X075")
      (libsource (lib "eagle-import") (part "C-US"))
    )
    (comp (ref "C22")
      (value ".01uF")
      (footprint "eagle-import:C063-025X075")
      (libsource (lib "eagle-import") (part "C-US"))
    )
    (comp (ref "C23")
      (value ".01uF")
      (footprint "eagle-import:C063-025X075")
      (libsource (lib "eagle-import") (part "C-US"))
    )
    (comp (ref "C24")
      (value ".01uF")
      (footprint "eagle-import:C063-025X075")
      (libsource (lib "eagle-import") (part "C-US"))
    )
    (comp (ref "C25")
      (value ".01uF")
      (footprint "eagle-import:C063-025X075")
      (libsource (lib "eagle-import") (part "C-US"))
    )
    (comp (ref "C26")
      (value ".01uF")
      (footprint "eagle-import:C063-025X075")
      (libsource (lib "eagle-import") (part "C-US"))
    )
    (comp (ref "C27")
      (value ".01uF")
      (footprint "eagle-import:C063-025X075")
      (libsource (lib "eagle-import") (part "C-US"))
    )
    (comp (ref "C28")
      (value ".01uF")
      (footprint "eagle-import:C063-025X075")
      (libsource (lib "eagle-import") (part "C-US"))
    )
    (comp (ref "C29")
      (value "6.8uF")
      (footprint "eagle-import:E12-8")
      (libsource (lib "eagle-import") (part "CPOL-USE20-8AXIAL"))
    )
    (comp (ref "C30")
      (value "6.8uF")
      (footprint "eagle-import:E12-8")
      (libsource (lib "eagle-import") (part "CPOL-USE20-8AXIAL"))
    )
    (comp (ref "C31")
      (value "6.8uF")
      (footprint "eagle-import:E12-8")
      (libsource (lib "eagle-import") (part "CPOL-USE20-8AXIAL"))
    )
    (comp (ref "C32")
      (value "6.8uF")
      (footprint "eagle-import:E12-8")
      (libsource (lib "eagle-import") (part "CPOL-USE20-8AXIAL"))
    )
    (comp (ref "E11")
      (value "SP380N")
      (footprint "eagle-import:DIL14")
      (libsource (lib "eagle-import") (part "SP380N"))
    )
    (comp (ref "E12")
      (value "SP314N")
      (footprint "eagle-import:DIL14")
      (libsource (lib "eagle-import") (part "SP314N"))
    )
    (comp (ref "E13")
      (value "SP380N")
      (footprint "eagle-import:DIL14")
      (libsource (lib "eagle-import") (part "SP380N"))
    )
    (comp (ref "E14")
      (value "7404N")
      (footprint "eagle-import:DIL14")
      (libsource (lib "eagle-import") (part "7404N"))
    )
    (comp (ref "E16")
      (value "N8881N")
      (footprint "eagle-import:DIL14")
      (libsource (lib "eagle-import") (part "N8881N"))
    )
    (comp (ref "E17")
      (value "N8881N")
      (footprint "eagle-import:DIL14")
      (libsource (lib "eagle-import") (part "N8881N"))
    )
    (comp (ref "E18")
      (value "7474N")
      (footprint "eagle-import:DIL14")
      (libsource (lib "eagle-import") (part "7474NS"))
    )
    (comp (ref "E19")
      (value "7474N")
      (footprint "eagle-import:DIL14")
      (libsource (lib "eagle-import") (part "7474NS"))
    )
    (comp (ref "E20")
      (value "7402N")
      (footprint "eagle-import:DIL14")
      (libsource (lib "eagle-import") (part "7402N"))
    )
    (comp (ref "E21")
      (value "7404N")
      (footprint "eagle-import:DIL14")
      (libsource (lib "eagle-import") (part "7404N"))
    )
    (comp (ref "E22")
      (value "7400N")
      (footprint "eagle-import:DIL14")
      (libsource (lib "eagle-import") (part "7400N"))
    )
    (comp (ref "E23")
      (value "74H21N")
      (footprint "eagle-import:DIL14")
      (libsource (lib "eagle-import") (part "7421NLS"))
    )
    (comp (ref "E24")
      (value "SP380N")
      (footprint "eagle-import:DIL14")
      (libsource (lib "eagle-import") (part "SP380N"))
    )
    (comp (ref "E25")
      (value "DEC8251")
      (footprint "eagle-import:DIL16")
      (libsource (lib "eagle-import") (part "DEC8251"))
    )
    (comp (ref "E26")
      (value "7400N")
      (footprint "eagle-import:DIL14")
      (libsource (lib "eagle-import") (part "7400N"))
    )
    (comp (ref "E27")
      (value "7400N")
      (footprint "eagle-import:DIL14")
      (libsource (lib "eagle-import") (part "7400N"))
    )
    (comp (ref "E28")
      (value "7416N")
      (footprint "eagle-import:DIL14")
      (libsource (lib "eagle-import") (part "7416N"))
    )
    (comp (ref "F")
      (value "EDGE-TOP")
      (footprint "eagle-import:EDGE-CON2")
      (libsource (lib "eagle-import") (part "EDGE-TOP"))
    )
    (comp (ref "H")
      (value "EDGE-TOP")
      (footprint "eagle-import:EDGE-CON2")
      (libsource (lib "eagle-import") (part "EDGE-TOP"))
    )
    (comp (ref "J1")
      (value "1-480459-0")
      (footprint "eagle-import:1-480459-0")
      (libsource (lib "eagle-import") (part "1-480459-0"))
    )
    (comp (ref "OMNIBUS")
      (value "QUAD")
      (footprint "eagle-import:EDGE-CON8")
      (libsource (lib "eagle-import") (part "QUAD"))
    )
    (comp (ref "R1")
      (value "1.5K")
      (footprint "eagle-import:0207_10")
      (libsource (lib "eagle-import") (part "R-US_0207/10"))
    )
    (comp (ref "R2")
      (value "470")
      (footprint "eagle-import:0207_10")
      (libsource (lib "eagle-import") (part "R-US_0207/10"))
    )
    (comp (ref "R3")
      (value "470")
      (footprint "eagle-import:0207_10")
      (libsource (lib "eagle-import") (part "R-US_0207/10"))
    )
    (comp (ref "R5")
      (value "470")
      (footprint "eagle-import:0207_10")
      (libsource (lib "eagle-import") (part "R-US_0207/10"))
    )
    (comp (ref "R6")
      (value "470")
      (footprint "eagle-import:0207_10")
      (libsource (lib "eagle-import") (part "R-US_0207/10"))
    )
    (comp (ref "R11")
      (value "1.5K")
      (footprint "eagle-import:0207_10")
      (libsource (lib "eagle-import") (part "R-US_0207/10"))
    )
    (comp (ref "R12")
      (value "470")
      (footprint "eagle-import:0207_10")
      (libsource (lib "eagle-import") (part "R-US_0207/10"))
    )
    (comp (ref "R13")
      (value "470")
      (footprint "eagle-import:0207_10")
      (libsource (lib "eagle-import") (part "R-US_0207/10"))
    )
    (comp (ref "S1")
      (value "12-09698")
      (footprint "eagle-import:23-021")
      (libsource (lib "eagle-import") (part "12-09698"))
    )
    (comp (ref "W1")
      (value "0")
      (footprint "eagle-import:0R_10")
      (libsource (lib "eagle-import") (part "0R"))
    )
    (comp (ref "W2")
      (value "open")
      (footprint "eagle-import:0R_10")
      (libsource (lib "eagle-import") (part "0R"))
    )
    (comp (ref "C33")
      (value ".033uF")
      (footprint "eagle-import:C325-137X374")
      (libsource (lib "eagle-import") (part "C-US325-137X374"))
    )
    (comp (ref "C34")
      (value ".022uF")
      (footprint "eagle-import:C203-054-229")
      (libsource (lib "eagle-import") (part "C-US8"))
    )
    (comp (ref "C35")
      (value ".22uF")
      (footprint "eagle-import:C203-054-229")
      (libsource (lib "eagle-import") (part "C-US8"))
    )
    (comp (ref "C36")
      (value "220pF")
      (footprint "eagle-import:C063-025X075")
      (libsource (lib "eagle-import") (part "C-US"))
    )
    (comp (ref "C37")
      (value "220pF")
      (footprint "eagle-import:C063-025X075")
      (libsource (lib "eagle-import") (part "C-US"))
    )
    (comp (ref "C38")
      (value "2700pF")
      (footprint "eagle-import:C102-043X133")
      (libsource (lib "eagle-import") (part "C-US102-043X133"))
    )
    (comp (ref "C39")
      (value ".01uf 10%")
      (footprint "eagle-import:C063-025X075")
      (libsource (lib "eagle-import") (part "C-US"))
    )
    (comp (ref "C40")
      (value "470pF")
      (footprint "eagle-import:C063-025X075")
      (libsource (lib "eagle-import") (part "C-US"))
    )
    (comp (ref "D1")
      (value "D664")
      (footprint "eagle-import:DO35-10")
      (libsource (lib "eagle-import") (part "DIODE-DO35-10"))
    )
    (comp (ref "D2")
      (value "D664")
      (footprint "eagle-import:DO35-10")
      (libsource (lib "eagle-import") (part "DIODE-DO35-10"))
    )
    (comp (ref "E1")
      (value "74123N")
      (footprint "eagle-import:DIL16")
      (libsource (lib "eagle-import") (part "74123N"))
    )
    (comp (ref "E2")
      (value "74123N")
      (footprint "eagle-import:DIL16")
      (libsource (lib "eagle-import") (part "74123N"))
    )
    (comp (ref "E3")
      (value "7402N")
      (footprint "eagle-import:DIL14")
      (libsource (lib "eagle-import") (part "7402N"))
    )
    (comp (ref "E4")
      (value "9601")
      (footprint "eagle-import:DIL14")
      (libsource (lib "eagle-import") (part "9601"))
    )
    (comp (ref "E5")
      (value "7474N")
      (footprint "eagle-import:DIL14")
      (libsource (lib "eagle-import") (part "7474NS"))
    )
    (comp (ref "E6")
      (value "7474N")
      (footprint "eagle-import:DIL14")
      (libsource (lib "eagle-import") (part "7474NS"))
    )
    (comp (ref "E7")
      (value "N8881N")
      (footprint "eagle-import:DIL14")
      (libsource (lib "eagle-import") (part "N8881N"))
    )
    (comp (ref "E8")
      (value "N8881N")
      (footprint "eagle-import:DIL14")
      (libsource (lib "eagle-import") (part "N8881N"))
    )
    (comp (ref "E9")
      (value "SP380N")
      (footprint "eagle-import:DIL14")
      (libsource (lib "eagle-import") (part "SP380N"))
    )
    (comp (ref "E10")
      (value "7406N")
      (footprint "eagle-import:DIL14")
      (libsource (lib "eagle-import") (part "7406N"))
    )
    (comp (ref "E15")
      (value "9601")
      (footprint "eagle-import:DIL14")
      (libsource (lib "eagle-import") (part "9601"))
    )
    (comp (ref "Q1")
      (value "2N3009")
      (footprint "eagle-import:TO18-")
      (libsource (lib "eagle-import") (part "-NPN-TO18-"))
    )
    (comp (ref "R4")
      (value "10K")
      (footprint "eagle-import:0207_10")
      (libsource (lib "eagle-import") (part "R-US_0207/10"))
    )
    (comp (ref "R7")
      (value "10K")
      (footprint "eagle-import:0207_10")
      (libsource (lib "eagle-import") (part "R-US_0207/10"))
    )
    (comp (ref "R8")
      (value "19.6K 1%")
      (footprint "eagle-import:0207_15")
      (libsource (lib "eagle-import") (part "R-US_0207/15"))
    )
    (comp (ref "R9")
      (value "6.81K 1%")
      (footprint "eagle-import:0207_15")
      (libsource (lib "eagle-import") (part "R-US_0207/15"))
    )
    (comp (ref "R10")
      (value "33.2K 1%")
      (footprint "eagle-import:0207_15")
      (libsource (lib "eagle-import") (part "R-US_0207/15"))
    )
    (comp (ref "R14")
      (value "1K")
      (footprint "eagle-import:0207_10")
      (libsource (lib "eagle-import") (part "R-US_0207/10"))
    )
    (comp (ref "R15")
      (value "1K")
      (footprint "eagle-import:0207_10")
      (libsource (lib "eagle-import") (part "R-US_0207/10"))
    )
    (comp (ref "R16")
      (value "1K")
      (footprint "eagle-import:0207_10")
      (libsource (lib "eagle-import") (part "R-US_0207/10"))
    )
    (comp (ref "R17")
      (value "12.1K 1%")
      (footprint "eagle-import:0207_15")
      (libsource (lib "eagle-import") (part "R-US_0207/15"))
    )
    (comp (ref "R18")
      (value "39.2K 1%")
      (footprint "eagle-import:0207_15")
      (libsource (lib "eagle-import") (part "R-US_0207/15"))
    )
    (comp (ref "R19")
      (value "24.3K 1%")
      (footprint "eagle-import:0207_15")
      (libsource (lib "eagle-import") (part "R-US_0207/15"))
    )
    (comp (ref "R20")
      (value "31.6K 1%")
      (footprint "eagle-import:0207_15")
      (libsource (lib "eagle-import") (part "R-US_0207/15"))
    )
    (comp (ref "R21")
      (value "470")
      (footprint "eagle-import:0207_10")
      (libsource (lib "eagle-import") (part "R-US_0207/10"))
    )
    (comp (ref "R22")
      (value "1K")
      (footprint "eagle-import:0207_10")
      (libsource (lib "eagle-import") (part "R-US_0207/10"))
    )
    (comp (ref "S2")
      (value "12-09698")
      (footprint "eagle-import:23-021")
      (libsource (lib "eagle-import") (part "12-09698"))
    )
    (comp (ref "TP1")
      (value "TPSQPAD1-17")
      (footprint "eagle-import:P1-17")
      (libsource (lib "eagle-import") (part "TPSQPAD1-17"))
    )
    (comp (ref "TP2")
      (value "TPSQPAD1-17")
      (footprint "eagle-import:P1-17")
      (libsource (lib "eagle-import") (part "TPSQPAD1-17"))
    )
    (comp (ref "W3")
      (value "0")
      (footprint "eagle-import:0R_10")
      (libsource (lib "eagle-import") (part "0R"))
    )
    (comp (ref "W4")
      (value "open")
      (footprint "eagle-import:0R_10")
      (libsource (lib "eagle-import") (part "0R"))
    )
  )
  (nets
    (net (code "1") (name "+3V") (class "Default")
      (node (ref "E1") (pin "2") (pinfunction "B_2") (pintype "input"))
      (node (ref "E1") (pin "3") (pinfunction "CLR_3") (pintype "input"))
      (node (ref "E14") (pin "12") (pinfunction "O_12") (pintype "output"))
      (node (ref "E14") (pin "2") (pinfunction "O_2") (pintype "output"))
      (node (ref "E15") (pin "4") (pinfunction "P$4_4") (pintype "input"))
      (node (ref "E18") (pin "10") (pinfunction "PRE_10") (pintype "input"))
      (node (ref "E18") (pin "4") (pinfunction "PRE_4") (pintype "input"))
      (node (ref "E19") (pin "2") (pinfunction "D_2") (pintype "input"))
      (node (ref "E19") (pin "4") (pinfunction "PRE_4") (pintype "input"))
      (node (ref "E2") (pin "11") (pinfunction "CLR_11") (pintype "input"))
      (node (ref "E2") (pin "3") (pinfunction "CLR_3") (pintype "input"))
      (node (ref "E4") (pin "4") (pinfunction "P$4_4") (pintype "input"))
      (node (ref "E5") (pin "10") (pinfunction "PRE_10") (pintype "input"))
      (node (ref "E5") (pin "4") (pinfunction "PRE_4") (pintype "input"))
      (node (ref "E6") (pin "10") (pinfunction "PRE_10") (pintype "input"))
      (node (ref "E6") (pin "4") (pinfunction "PRE_4") (pintype "input"))
    )
    (net (code "2") (name "+5V_X") (class "Default")
      (node (ref "D10") (pin "C") (pinfunction "C_C") (pintype "passive"))
      (node (ref "D12") (pin "C") (pinfunction "C_C") (pintype "passive"))
      (node (ref "D14") (pin "C") (pinfunction "C_C") (pintype "passive"))
      (node (ref "D16") (pin "C") (pinfunction "C_C") (pintype "passive"))
      (node (ref "D18") (pin "C") (pinfunction "C_C") (pintype "passive"))
      (node (ref "D20") (pin "C") (pinfunction "C_C") (pintype "passive"))
      (node (ref "D22") (pin "C") (pinfunction "C_C") (pintype "passive"))
      (node (ref "D24") (pin "C") (pinfunction "C_C") (pintype "passive"))
      (node (ref "D5") (pin "C") (pinfunction "C_C") (pintype "passive"))
      (node (ref "D8") (pin "C") (pinfunction "C_C") (pintype "passive"))
      (node (ref "E42") (pin "6") (pinfunction "OUT_6") (pintype "output"))
      (node (ref "J2") (pin "UU") (pinfunction "39_UU") (pintype "bidirectional"))
      (node (ref "R76") (pin "2") (pinfunction "2_2") (pintype "passive"))
    )
    (net (code "3") (name "+5V_Y") (class "Default")
      (node (ref "D32") (pin "C") (pinfunction "C_C") (pintype "passive"))
      (node (ref "D35") (pin "C") (pinfunction "C_C") (pintype "passive"))
      (node (ref "D36") (pin "C") (pinfunction "C_C") (pintype "passive"))
      (node (ref "D38") (pin "C") (pinfunction "C_C") (pintype "passive"))
      (node (ref "D40") (pin "C") (pinfunction "C_C") (pintype "passive"))
      (node (ref "D42") (pin "C") (pinfunction "C_C") (pintype "passive"))
      (node (ref "D44") (pin "C") (pinfunction "C_C") (pintype "passive"))
      (node (ref "D46") (pin "C") (pinfunction "C_C") (pintype "passive"))
      (node (ref "D48") (pin "C") (pinfunction "C_C") (pintype "passive"))
      (node (ref "D50") (pin "C") (pinfunction "C_C") (pintype "passive"))
      (node (ref "E43") (pin "6") (pinfunction "OUT_6") (pintype "output"))
      (node (ref "J2") (pin "SS") (pinfunction "37_SS") (pintype "bidirectional"))
      (node (ref "R77") (pin "2") (pinfunction "2_2") (pintype "passive"))
    )
    (net (code "4") (name "+15V") (class "Default")
      (node (ref "D25") (pin "C") (pinfunction "C_C") (pintype "passive"))
      (node (ref "E42") (pin "7") (pinfunction "V+_7") (pintype "power_in"))
      (node (ref "E43") (pin "7") (pinfunction "V+_7") (pintype "power_in"))
      (node (ref "F") (pin "D1") (pinfunction "P_D1") (pintype "passive"))
      (node (ref "F") (pin "E1") (pinfunction "P_E1") (pintype "passive"))
      (node (ref "F1") (pin "D1") (pinfunction "P_D1") (pintype "passive"))
      (node (ref "F1") (pin "E1") (pinfunction "P_E1") (pintype "passive"))
      (node (ref "H") (pin "R1") (pinfunction "P_R1") (pintype "passive"))
      (node (ref "H") (pin "S1") (pinfunction "P_S1") (pintype "passive"))
      (node (ref "H1") (pin "R1") (pinfunction "P_R1") (pintype "passive"))
      (node (ref "H1") (pin "S1") (pinfunction "P_S1") (pintype "passive"))
      (node (ref "J1") (pin "1") (pinfunction "1_1") (pintype "passive"))
      (node (ref "J1") (pin "2") (pinfunction "2_2") (pintype "passive"))
      (node (ref "R103") (pin "2") (pinfunction "2_2") (pintype "passive"))
      (node (ref "R106") (pin "2") (pinfunction "2_2") (pintype "passive"))
      (node (ref "R109") (pin "2") (pinfunction "2_2") (pintype "passive"))
      (node (ref "R112") (pin "2") (pinfunction "2_2") (pintype "passive"))
      (node (ref "R115") (pin "2") (pinfunction "2_2") (pintype "passive"))
      (node (ref "R120") (pin "2") (pinfunction "2_2") (pintype "passive"))
      (node (ref "R124") (pin "2") (pinfunction "2_2") (pintype "passive"))
      (node (ref "R128") (pin "2") (pinfunction "2_2") (pintype "passive"))
      (node (ref "R132") (pin "2") (pinfunction "2_2") (pintype "passive"))
      (node (ref "R163") (pin "2") (pinfunction "2_2") (pintype "passive"))
      (node (ref "R33") (pin "2") (pinfunction "2_2") (pintype "passive"))
      (node (ref "R38") (pin "2") (pinfunction "2_2") (pintype "passive"))
      (node (ref "R41") (pin "2") (pinfunction "2_2") (pintype "passive"))
      (node (ref "R44") (pin "2") (pinfunction "2_2") (pintype "passive"))
      (node (ref "R47") (pin "2") (pinfunction "2_2") (pintype "passive"))
      (node (ref "R50") (pin "2") (pinfunction "2_2") (pintype "passive"))
      (node (ref "R53") (pin "2") (pinfunction "2_2") (pintype "passive"))
      (node (ref "R56") (pin "2") (pinfunction "2_2") (pintype "passive"))
      (node (ref "R59") (pin "2") (pinfunction "2_2") (pintype "passive"))
      (node (ref "R62") (pin "2") (pinfunction "2_2") (pintype "passive"))
      (node (ref "R72") (pin "2") (pinfunction "2_2") (pintype "passive"))
      (node (ref "R90") (pin "2") (pinfunction "2_2") (pintype "passive"))
      (node (ref "R98") (pin "2") (pinfunction "2_2") (pintype "passive"))
    )
    (net (code "5") (name "-15V") (class "Default")
      (node (ref "C58") (pin "-") (pinfunction "-_-") (pintype "passive"))
      (node (ref "C59") (pin "-") (pinfunction "-_-") (pintype "passive"))
      (node (ref "C60") (pin "-") (pinfunction "-_-") (pintype "passive"))
      (node (ref "C61") (pin "-") (pinfunction "-_-") (pintype "passive"))
      (node (ref "D29") (pin "A") (pinfunction "A_A") (pintype "passive"))
      (node (ref "F") (pin "F1") (pinfunction "P_F1") (pintype "passive"))
      (node (ref "F") (pin "H1") (pinfunction "P_H1") (pintype "passive"))
      (node (ref "F1") (pin "F1") (pinfunction "P_F1") (pintype "passive"))
      (node (ref "F1") (pin "H1") (pinfunction "P_H1") (pintype "passive"))
      (node (ref "H") (pin "N1") (pinfunction "P_N1") (pintype "passive"))
      (node (ref "H") (pin "P1") (pinfunction "P_P1") (pintype "passive"))
      (node (ref "H1") (pin "N1") (pinfunction "P_N1") (pintype "passive"))
      (node (ref "H1") (pin "P1") (pinfunction "P_P1") (pintype "passive"))
      (node (ref "J1") (pin "3") (pinfunction "3_3") (pintype "passive"))
      (node (ref "J1") (pin "4") (pinfunction "4_4") (pintype "passive"))
      (node (ref "OMNIBUS") (pin "AB2") (pinfunction "1_AB2") (pintype "bidirectional"))
      (node (ref "OMNIBUS") (pin "BB2") (pinfunction "1_BB2") (pintype "bidirectional"))
      (node (ref "OMNIBUS") (pin "CB2") (pinfunction "1_CB2") (pintype "bidirectional"))
      (node (ref "OMNIBUS1") (pin "AB2") (pinfunction "1_AB2") (pintype "bidirectional"))
      (node (ref "OMNIBUS1") (pin "BB2") (pinfunction "1_BB2") (pintype "bidirectional"))
      (node (ref "OMNIBUS1") (pin "CB2") (pinfunction "1_CB2") (pintype "bidirectional"))
      (node (ref "R140") (pin "1") (pinfunction "1_1") (pintype "passive"))
      (node (ref "R147") (pin "1") (pinfunction "1_1") (pintype "passive"))
      (node (ref "R148") (pin "1") (pinfunction "1_1") (pintype "passive"))
      (node (ref "R158") (pin "1") (pinfunction "1_1") (pintype "passive"))
    )
    (net (code "6") (name "BIT10") (class "Default")
      (node (ref "E13") (pin "3") (pinfunction "O_3") (pintype "output"))
      (node (ref "E18") (pin "2") (pinfunction "D_2") (pintype "input"))
      (node (ref "E37") (pin "1") (pinfunction "B_1") (pintype "input"))
      (node (ref "E38") (pin "1") (pinfunction "B_1") (pintype "input"))
      (node (ref "F") (pin "U1") (pinfunction "P_U1") (pintype "passive"))
      (node (ref "F1") (pin "U1") (pinfunction "P_U1") (pintype "passive"))
    )
    (net (code "7") (name "BIT11") (class "Default")
      (node (ref "E13") (pin "2") (pinfunction "O_2") (pintype "output"))
      (node (ref "E18") (pin "12") (pinfunction "D_12") (pintype "input"))
      (node (ref "E37") (pin "15") (pinfunction "A_15") (pintype "input"))
      (node (ref "E38") (pin "15") (pinfunction "A_15") (pintype "input"))
      (node (ref "F") (pin "T1") (pinfunction "P_T1") (pintype "passive"))
      (node (ref "F1") (pin "T1") (pinfunction "P_T1") (pintype "passive"))
    )
    (net (code "8") (name "BTP3") (class "Default")
      (node (ref "E14") (pin "8") (pinfunction "O_8") (pintype "output"))
      (node (ref "E15") (pin "3") (pinfunction "P$3_3") (pintype "input"))
      (node (ref "E22") (pin "1") (pinfunction "I0_1") (pintype "input"))
      (node (ref "E22") (pin "10") (pinfunction "I1_10") (pintype "input"))
      (node (ref "E22") (pin "12") (pinfunction "I0_12") (pintype "input"))
      (node (ref "E22") (pin "4") (pinfunction "I0_4") (pintype "input"))
      (node (ref "E26") (pin "13") (pinfunction "I1_13") (pintype "input"))
      (node (ref "E4") (pin "3") (pinfunction "P$3_3") (pintype "input"))
    )
    (net (code "9") (name "CHAN") (class "Default")
      (node (ref "E16") (pin "2") (pinfunction "I0_2") (pintype "input"))
      (node (ref "E18") (pin "5") (pinfunction "Q_5") (pintype "output"))
      (node (ref "E28") (pin "1") (pinfunction "I_1") (pintype "input"))
    )
    (net (code "10") (name "CLEAR") (class "Default")
      (node (ref "E28") (pin "5") (pinfunction "I_5") (pintype "input"))
      (node (ref "E28") (pin "8") (pinfunction "O_8") (pintype "open_collector"))
      (node (ref "E3") (pin "5") (pinfunction "I0_5") (pintype "input"))
      (node (ref "F") (pin "N1") (pinfunction "P_N1") (pintype "passive"))
      (node (ref "F1") (pin "N1") (pinfunction "P_N1") (pintype "passive"))
      (node (ref "H1") (pin "H1") (pinfunction "P_H1") (pintype "passive"))
      (node (ref "R3") (pin "1") (pinfunction "1_1") (pintype "passive"))
    )
    (net (code "11") (name "COLOR") (class "Default")
      (node (ref "E2") (pin "10") (pinfunction "B_10") (pintype "input"))
      (node (ref "E6") (pin "9") (pinfunction "Q_9") (pintype "output"))
      (node (ref "E7") (pin "2") (pinfunction "I0_2") (pintype "input"))
      (node (ref "E7") (pin "3") (pinfunction "I1_3") (pintype "input"))
      (node (ref "E8") (pin "8") (pinfunction "I0_8") (pintype "input"))
    )
    (net (code "12") (name "DI02") (class "Default")
      (node (ref "E31") (pin "2") (pinfunction "O_2") (pintype "output"))
      (node (ref "E33") (pin "1") (pinfunction "B_1") (pintype "input"))
      (node (ref "E34") (pin "1") (pinfunction "B_1") (pintype "input"))
    )
    (net (code "13") (name "DI03") (class "Default")
      (node (ref "E31") (pin "3") (pinfunction "O_3") (pintype "output"))
      (node (ref "E33") (pin "15") (pinfunction "A_15") (pintype "input"))
      (node (ref "E34") (pin "15") (pinfunction "A_15") (pintype "input"))
    )
    (net (code "14") (name "DI04") (class "Default")
      (node (ref "E32") (pin "3") (pinfunction "O_3") (pintype "output"))
      (node (ref "E35") (pin "9") (pinfunction "D_9") (pintype "input"))
      (node (ref "E36") (pin "9") (pinfunction "D_9") (pintype "input"))
    )
    (net (code "15") (name "DI05") (class "Default")
      (node (ref "E32") (pin "2") (pinfunction "O_2") (pintype "output"))
      (node (ref "E35") (pin "10") (pinfunction "C_10") (pintype "input"))
      (node (ref "E36") (pin "10") (pinfunction "C_10") (pintype "input"))
    )
    (net (code "16") (name "DI06") (class "Default")
      (node (ref "E32") (pin "14") (pinfunction "O_14") (pintype "output"))
      (node (ref "E35") (pin "1") (pinfunction "B_1") (pintype "input"))
      (node (ref "E36") (pin "1") (pinfunction "B_1") (pintype "input"))
    )
    (net (code "17") (name "DI07") (class "Default")
      (node (ref "E32") (pin "13") (pinfunction "O_13") (pintype "output"))
      (node (ref "E35") (pin "15") (pinfunction "A_15") (pintype "input"))
      (node (ref "E36") (pin "15") (pinfunction "A_15") (pintype "input"))
    )
    (net (code "18") (name "DI08") (class "Default")
      (node (ref "E31") (pin "13") (pinfunction "O_13") (pintype "output"))
      (node (ref "E37") (pin "9") (pinfunction "D_9") (pintype "input"))
      (node (ref "E38") (pin "9") (pinfunction "D_9") (pintype "input"))
    )
    (net (code "19") (name "DI09") (class "Default")
      (node (ref "E31") (pin "14") (pinfunction "O_14") (pintype "output"))
      (node (ref "E37") (pin "10") (pinfunction "C_10") (pintype "input"))
      (node (ref "E38") (pin "10") (pinfunction "C_10") (pintype "input"))
    )
    (net (code "20") (name "DIRE") (class "Default")
      (node (ref "E16") (pin "11") (pinfunction "I0_11") (pintype "input"))
      (node (ref "E16") (pin "12") (pinfunction "I1_12") (pintype "input"))
      (node (ref "E16") (pin "3") (pinfunction "I1_3") (pintype "input"))
      (node (ref "E16") (pin "5") (pinfunction "I0_5") (pintype "input"))
      (node (ref "E17") (pin "12") (pinfunction "I1_12") (pintype "input"))
      (node (ref "E21") (pin "12") (pinfunction "O_12") (pintype "output"))
      (node (ref "E8") (pin "11") (pinfunction "I0_11") (pintype "input"))
      (node (ref "E8") (pin "2") (pinfunction "I0_2") (pintype "input"))
      (node (ref "E8") (pin "9") (pinfunction "I1_9") (pintype "input"))
    )
    (net (code "21") (name "ERASE") (class "Default")
      (node (ref "E10") (pin "3") (pinfunction "I_3") (pintype "input"))
      (node (ref "E3") (pin "12") (pinfunction "I1_12") (pintype "input"))
      (node (ref "E6") (pin "5") (pinfunction "Q_5") (pintype "output"))
    )
    (net (code "22") (name "EX_ANALOG_X") (class "Default")
      (node (ref "H1") (pin "B2") (pinfunction "P_B2") (pintype "passive"))
      (node (ref "R141") (pin "2") (pinfunction "2_2") (pintype "passive"))
    )
    (net (code "23") (name "EX_ANALOG_Y") (class "Default")
      (node (ref "H1") (pin "C2") (pinfunction "P_C2") (pintype "passive"))
      (node (ref "R150") (pin "2") (pinfunction "2_2") (pintype "passive"))
    )
    (net (code "24") (name "GND") (class "Default")
      (node (ref "C1") (pin "2") (pinfunction "2_2") (pintype "passive"))
      (node (ref "C10") (pin "2") (pinfunction "2_2") (pintype "passive"))
      (node (ref "C11") (pin "2") (pinfunction "2_2") (pintype "passive"))
      (node (ref "C12") (pin "2") (pinfunction "2_2") (pintype "passive"))
      (node (ref "C13") (pin "2") (pinfunction "2_2") (pintype "passive"))
      (node (ref "C14") (pin "2") (pinfunction "2_2") (pintype "passive"))
      (node (ref "C15") (pin "2") (pinfunction "2_2") (pintype "passive"))
      (node (ref "C16") (pin "2") (pinfunction "2_2") (pintype "passive"))
      (node (ref "C17") (pin "2") (pinfunction "2_2") (pintype "passive"))
      (node (ref "C18") (pin "2") (pinfunction "2_2") (pintype "passive"))
      (node (ref "C19") (pin "2") (pinfunction "2_2") (pintype "passive"))
      (node (ref "C2") (pin "2") (pinfunction "2_2") (pintype "passive"))
      (node (ref "C20") (pin "2") (pinfunction "2_2") (pintype "passive"))
      (node (ref "C21") (pin "2") (pinfunction "2_2") (pintype "passive"))
      (node (ref "C22") (pin "2") (pinfunction "2_2") (pintype "passive"))
      (node (ref "C23") (pin "2") (pinfunction "2_2") (pintype "passive"))
      (node (ref "C24") (pin "2") (pinfunction "2_2") (pintype "passive"))
      (node (ref "C25") (pin "2") (pinfunction "2_2") (pintype "passive"))
      (node (ref "C26") (pin "2") (pinfunction "2_2") (pintype "passive"))
      (node (ref "C27") (pin "2") (pinfunction "2_2") (pintype "passive"))
      (node (ref "C28") (pin "2") (pinfunction "2_2") (pintype "passive"))
      (node (ref "C29") (pin "-") (pinfunction "-_-") (pintype "passive"))
      (node (ref "C3") (pin "2") (pinfunction "2_2") (pintype "passive"))
      (node (ref "C30") (pin "-") (pinfunction "-_-") (pintype "passive"))
      (node (ref "C31") (pin "-") (pinfunction "-_-") (pintype "passive"))
      (node (ref "C32") (pin "-") (pinfunction "-_-") (pintype "passive"))
      (node (ref "C4") (pin "2") (pinfunction "2_2") (pintype "passive"))
      (node (ref "C41") (pin "2") (pinfunction "2_2") (pintype "passive"))
      (node (ref "C42") (pin "2") (pinfunction "2_2") (pintype "passive"))
      (node (ref "C43") (pin "2") (pinfunction "2_2") (pintype "passive"))
      (node (ref "C44") (pin "2") (pinfunction "2_2") (pintype "passive"))
      (node (ref "C45") (pin "2") (pinfunction "2_2") (pintype "passive"))
      (node (ref "C46") (pin "2") (pinfunction "2_2") (pintype "passive"))
      (node (ref "C47") (pin "2") (pinfunction "2_2") (pintype "passive"))
      (node (ref "C48") (pin "2") (pinfunction "2_2") (pintype "passive"))
      (node (ref "C49") (pin "2") (pinfunction "2_2") (pintype "passive"))
      (node (ref "C5") (pin "2") (pinfunction "2_2") (pintype "passive"))
      (node (ref "C50") (pin "2") (pinfunction "2_2") (pintype "passive"))
      (node (ref "C51") (pin "2") (pinfunction "2_2") (pintype "passive"))
      (node (ref "C52") (pin "2") (pinfunction "2_2") (pintype "passive"))
      (node (ref "C53") (pin "2") (pinfunction "2_2") (pintype "passive"))
      (node (ref "C54") (pin "2") (pinfunction "2_2") (pintype "passive"))
      (node (ref "C55") (pin "-") (pinfunction "-_-") (pintype "passive"))
      (node (ref "C56") (pin "-") (pinfunction "-_-") (pintype "passive"))
      (node (ref "C57") (pin "-") (pinfunction "-_-") (pintype "passive"))
      (node (ref "C58") (pin "+") (pinfunction "+_+") (pintype "passive"))
      (node (ref "C59") (pin "+") (pinfunction "+_+") (pintype "passive"))
      (node (ref "C6") (pin "2") (pinfunction "2_2") (pintype "passive"))
      (node (ref "C60") (pin "+") (pinfunction "+_+") (pintype "passive"))
      (node (ref "C61") (pin "+") (pinfunction "+_+") (pintype "passive"))
      (node (ref "C62") (pin "-") (pinfunction "-_-") (pintype "passive"))
      (node (ref "C64") (pin "2") (pinfunction "2_2") (pintype "passive"))
      (node (ref "C65") (pin "2") (pinfunction "2_2") (pintype "passive"))
      (node (ref "C67") (pin "2") (pinfunction "2_2") (pintype "passive"))
      (node (ref "C68") (pin "1") (pinfunction "1_1") (pintype "passive"))
      (node (ref "C69") (pin "2") (pinfunction "2_2") (pintype "passive"))
      (node (ref "C7") (pin "2") (pinfunction "2_2") (pintype "passive"))
      (node (ref "C71") (pin "2") (pinfunction "2_2") (pintype "passive"))
      (node (ref "C73") (pin "1") (pinfunction "1_1") (pintype "passive"))
      (node (ref "C75") (pin "-") (pinfunction "-_-") (pintype "passive"))
      (node (ref "C76") (pin "+") (pinfunction "+_+") (pintype "passive"))
      (node (ref "C77") (pin "-") (pinfunction "-_-") (pintype "passive"))
      (node (ref "C78") (pin "+") (pinfunction "+_+") (pintype "passive"))
      (node (ref "C8") (pin "2") (pinfunction "2_2") (pintype "passive"))
      (node (ref "C9") (pin "2") (pinfunction "2_2") (pintype "passive"))
      (node (ref "D26") (pin "A") (pinfunction "A_A") (pintype "passive"))
      (node (ref "D55") (pin "C") (pinfunction "C_C") (pintype "passive"))
      (node (ref "D57") (pin "C") (pinfunction "C_C") (pintype "passive"))
      (node (ref "D58") (pin "C") (pinfunction "C_C") (pintype "passive"))
      (node (ref "D59") (pin "C") (pinfunction "C_C") (pintype "passive"))
      (node (ref "E13") (pin "10") (pinfunction "I1_10") (pintype "input"))
      (node (ref "E13") (pin "11") (pinfunction "I0_11") (pintype "input"))
      (node (ref "E14") (pin "1") (pinfunction "I_1") (pintype "input"))
      (node (ref "E14") (pin "13") (pinfunction "I_13") (pintype "input"))
      (node (ref "E2") (pin "1") (pinfunction "A_1") (pintype "input"))
      (node (ref "E2") (pin "9") (pinfunction "A_9") (pintype "input"))
      (node (ref "E33") (pin "10") (pinfunction "C_10") (pintype "input"))
      (node (ref "E33") (pin "14") (pinfunction "CLR_14") (pintype "input"))
      (node (ref "E33") (pin "9") (pinfunction "D_9") (pintype "input"))
      (node (ref "E34") (pin "10") (pinfunction "C_10") (pintype "input"))
      (node (ref "E34") (pin "14") (pinfunction "CLR_14") (pintype "input"))
      (node (ref "E34") (pin "9") (pinfunction "D_9") (pintype "input"))
      (node (ref "E35") (pin "14") (pinfunction "CLR_14") (pintype "input"))
      (node (ref "E36") (pin "14") (pinfunction "CLR_14") (pintype "input"))
      (node (ref "E37") (pin "14") (pinfunction "CLR_14") (pintype "input"))
      (node (ref "E38") (pin "14") (pinfunction "CLR_14") (pintype "input"))
      (node (ref "E42") (pin "4") (pinfunction "V-_4") (pintype "power_in"))
      (node (ref "E43") (pin "4") (pinfunction "V-_4") (pintype "power_in"))
      (node (ref "F") (pin "A1") (pinfunction "P_A1") (pintype "passive"))
      (node (ref "F") (pin "B1") (pinfunction "P_B1") (pintype "passive"))
      (node (ref "F") (pin "C1") (pinfunction "P_C1") (pintype "passive"))
      (node (ref "F1") (pin "A1") (pinfunction "P_A1") (pintype "passive"))
      (node (ref "F1") (pin "B1") (pinfunction "P_B1") (pintype "passive"))
      (node (ref "F1") (pin "C1") (pinfunction "P_C1") (pintype "passive"))
      (node (ref "H") (pin "T1") (pinfunction "P_T1") (pintype "passive"))
      (node (ref "H") (pin "U1") (pinfunction "P_U1") (pintype "passive"))
      (node (ref "H") (pin "V1") (pinfunction "P_V1") (pintype "passive"))
      (node (ref "H1") (pin "T1") (pinfunction "P_T1") (pintype "passive"))
      (node (ref "H1") (pin "U1") (pinfunction "P_U1") (pintype "passive"))
      (node (ref "H1") (pin "V1") (pinfunction "P_V1") (pintype "passive"))
      (node (ref "J1") (pin "5") (pinfunction "5_5") (pintype "passive"))
      (node (ref "J1") (pin "6") (pinfunction "6_6") (pintype "passive"))
      (node (ref "J1") (pin "7") (pinfunction "7_7") (pintype "passive"))
      (node (ref "J1") (pin "8") (pinfunction "8_8") (pintype "passive"))
      (node (ref "J2") (pin "A") (pinfunction "1_A") (pintype "bidirectional"))
      (node (ref "J2") (pin "AA") (pinfunction "23_AA") (pintype "bidirectional"))
      (node (ref "J2") (pin "BB") (pinfunction "24_BB") (pintype "bidirectional"))
      (node (ref "J2") (pin "C") (pinfunction "3_C") (pintype "bidirectional"))
      (node (ref "J2") (pin "CC") (pinfunction "25_CC") (pintype "bidirectional"))
      (node (ref "J2") (pin "E") (pinfunction "5_E") (pintype "bidirectional"))
      (node (ref "J2") (pin "EE") (pinfunction "27_EE") (pintype "bidirectional"))
      (node (ref "J2") (pin "F") (pinfunction "6_F") (pintype "bidirectional"))
      (node (ref "J2") (pin "H") (pinfunction "7_H") (pintype "bidirectional"))
      (node (ref "J2") (pin "HH") (pinfunction "29_HH") (pintype "bidirectional"))
      (node (ref "J2") (pin "J") (pinfunction "8_J") (pintype "bidirectional"))
      (node (ref "J2") (pin "K") (pinfunction "9_K") (pintype "bidirectional"))
      (node (ref "J2") (pin "KK") (pinfunction "31_KK") (pintype "bidirectional"))
      (node (ref "J2") (pin "M") (pinfunction "11_M") (pintype "bidirectional"))
      (node (ref "J2") (pin "MM") (pinfunction "33_MM") (pintype "bidirectional"))
      (node (ref "J2") (pin "N") (pinfunction "12_N") (pintype "bidirectional"))
      (node (ref "J2") (pin "P") (pinfunction "13_P") (pintype "bidirectional"))
      (node (ref "J2") (pin "PP") (pinfunction "35_PP") (pintype "bidirectional"))
      (node (ref "J2") (pin "S") (pinfunction "15_S") (pintype "bidirectional"))
      (node (ref "J2") (pin "U") (pinfunction "17_U") (pintype "bidirectional"))
      (node (ref "J2") (pin "V") (pinfunction "18_V") (pintype "bidirectional"))
      (node (ref "J2") (pin "W") (pinfunction "19_W") (pintype "bidirectional"))
      (node (ref "J2") (pin "Y") (pinfunction "21_Y") (pintype "bidirectional"))
      (node (ref "OMNIBUS") (pin "AC2") (pinfunction "1_AC2") (pintype "bidirectional"))
      (node (ref "OMNIBUS") (pin "AF1") (pinfunction "1_AF1") (pintype "bidirectional"))
      (node (ref "OMNIBUS") (pin "AF2") (pinfunction "1_AF2") (pintype "bidirectional"))
      (node (ref "OMNIBUS") (pin "AN1") (pinfunction "1_AN1") (pintype "bidirectional"))
      (node (ref "OMNIBUS") (pin "AN2") (pinfunction "1_AN2") (pintype "bidirectional"))
      (node (ref "OMNIBUS") (pin "AT1") (pinfunction "1_AT1") (pintype "bidirectional"))
      (node (ref "OMNIBUS") (pin "AT2") (pinfunction "1_AT2") (pintype "bidirectional"))
      (node (ref "OMNIBUS") (pin "BC1") (pinfunction "1_BC1") (pintype "bidirectional"))
      (node (ref "OMNIBUS") (pin "BC2") (pinfunction "1_BC2") (pintype "bidirectional"))
      (node (ref "OMNIBUS") (pin "BF1") (pinfunction "1_BF1") (pintype "bidirectional"))
      (node (ref "OMNIBUS") (pin "BF2") (pinfunction "1_BF2") (pintype "bidirectional"))
      (node (ref "OMNIBUS") (pin "BN1") (pinfunction "1_BN1") (pintype "bidirectional"))
      (node (ref "OMNIBUS") (pin "BN2") (pinfunction "1_BN2") (pintype "bidirectional"))
      (node (ref "OMNIBUS") (pin "BT1") (pinfunction "1_BT1") (pintype "bidirectional"))
      (node (ref "OMNIBUS") (pin "BT2") (pinfunction "1_BT2") (pintype "bidirectional"))
      (node (ref "OMNIBUS") (pin "CC1") (pinfunction "1_CC1") (pintype "bidirectional"))
      (node (ref "OMNIBUS") (pin "CC2") (pinfunction "1_CC2") (pintype "bidirectional"))
      (node (ref "OMNIBUS") (pin "CF1") (pinfunction "1_CF1") (pintype "bidirectional"))
      (node (ref "OMNIBUS") (pin "CF2") (pinfunction "1_CF2") (pintype "bidirectional"))
      (node (ref "OMNIBUS") (pin "CN1") (pinfunction "1_CN1") (pintype "bidirectional"))
      (node (ref "OMNIBUS") (pin "CN2") (pinfunction "1_CN2") (pintype "bidirectional"))
      (node (ref "OMNIBUS") (pin "CT1") (pinfunction "1_CT1") (pintype "bidirectional"))
      (node (ref "OMNIBUS") (pin "CT2") (pinfunction "1_CT2") (pintype "bidirectional"))
      (node (ref "OMNIBUS") (pin "DC1") (pinfunction "1_DC1") (pintype "bidirectional"))
      (node (ref "OMNIBUS") (pin "DC2") (pinfunction "1_DC2") (pintype "bidirectional"))
      (node (ref "OMNIBUS") (pin "DF1") (pinfunction "1_DF1") (pintype "bidirectional"))
      (node (ref "OMNIBUS") (pin "DF2") (pinfunction "1_DF2") (pintype "bidirectional"))
      (node (ref "OMNIBUS") (pin "DN1") (pinfunction "1_DN1") (pintype "bidirectional"))
      (node (ref "OMNIBUS") (pin "DN2") (pinfunction "1_DN2") (pintype "bidirectional"))
      (node (ref "OMNIBUS") (pin "DT1") (pinfunction "1_DT1") (pintype "bidirectional"))
      (node (ref "OMNIBUS") (pin "DT2") (pinfunction "1_DT2") (pintype "bidirectional"))
      (node (ref "OMNIBUS1") (pin "AC2") (pinfunction "1_AC2") (pintype "bidirectional"))
      (node (ref "OMNIBUS1") (pin "AF1") (pinfunction "1_AF1") (pintype "bidirectional"))
      (node (ref "OMNIBUS1") (pin "AF2") (pinfunction "1_AF2") (pintype "bidirectional"))
      (node (ref "OMNIBUS1") (pin "AN1") (pinfunction "1_AN1") (pintype "bidirectional"))
      (node (ref "OMNIBUS1") (pin "AN2") (pinfunction "1_AN2") (pintype "bidirectional"))
      (node (ref "OMNIBUS1") (pin "AT1") (pinfunction "1_AT1") (pintype "bidirectional"))
      (node (ref "OMNIBUS1") (pin "AT2") (pinfunction "1_AT2") (pintype "bidirectional"))
      (node (ref "OMNIBUS1") (pin "BC1") (pinfunction "1_BC1") (pintype "bidirectional"))
      (node (ref "OMNIBUS1") (pin "BC2") (pinfunction "1_BC2") (pintype "bidirectional"))
      (node (ref "OMNIBUS1") (pin "BF1") (pinfunction "1_BF1") (pintype "bidirectional"))
      (node (ref "OMNIBUS1") (pin "BF2") (pinfunction "1_BF2") (pintype "bidirectional"))
      (node (ref "OMNIBUS1") (pin "BN1") (pinfunction "1_BN1") (pintype "bidirectional"))
      (node (ref "OMNIBUS1") (pin "BN2") (pinfunction "1_BN2") (pintype "bidirectional"))
      (node (ref "OMNIBUS1") (pin "BT1") (pinfunction "1_BT1") (pintype "bidirectional"))
      (node (ref "OMNIBUS1") (pin "BT2") (pinfunction "1_BT2") (pintype "bidirectional"))
      (node (ref "OMNIBUS1") (pin "CC1") (pinfunction "1_CC1") (pintype "bidirectional"))
      (node (ref "OMNIBUS1") (pin "CC2") (pinfunction "1_CC2") (pintype "bidirectional"))
      (node (ref "OMNIBUS1") (pin "CF1") (pinfunction "1_CF1") (pintype "bidirectional"))
      (node (ref "OMNIBUS1") (pin "CF2") (pinfunction "1_CF2") (pintype "bidirectional"))
      (node (ref "OMNIBUS1") (pin "CN1") (pinfunction "1_CN1") (pintype "bidirectional"))
      (node (ref "OMNIBUS1") (pin "CN2") (pinfunction "1_CN2") (pintype "bidirectional"))
      (node (ref "OMNIBUS1") (pin "CT1") (pinfunction "1_CT1") (pintype "bidirectional"))
      (node (ref "OMNIBUS1") (pin "CT2") (pinfunction "1_CT2") (pintype "bidirectional"))
      (node (ref "OMNIBUS1") (pin "DC1") (pinfunction "1_DC1") (pintype "bidirectional"))
      (node (ref "OMNIBUS1") (pin "DC2") (pinfunction "1_DC2") (pintype "bidirectional"))
      (node (ref "OMNIBUS1") (pin "DF1") (pinfunction "1_DF1") (pintype "bidirectional"))
      (node (ref "OMNIBUS1") (pin "DF2") (pinfunction "1_DF2") (pintype "bidirectional"))
      (node (ref "OMNIBUS1") (pin "DN1") (pinfunction "1_DN1") (pintype "bidirectional"))
      (node (ref "OMNIBUS1") (pin "DN2") (pinfunction "1_DN2") (pintype "bidirectional"))
      (node (ref "OMNIBUS1") (pin "DT1") (pinfunction "1_DT1") (pintype "bidirectional"))
      (node (ref "OMNIBUS1") (pin "DT2") (pinfunction "1_DT2") (pintype "bidirectional"))
      (node (ref "Q1") (pin "1") (pinfunction "E_1") (pintype "passive"))
      (node (ref "Q10") (pin "1") (pinfunction "E_1") (pintype "passive"))
      (node (ref "Q11") (pin "1") (pinfunction "E_1") (pintype "passive"))
      (node (ref "Q19") (pin "1") (pinfunction "E_1") (pintype "passive"))
      (node (ref "Q2") (pin "1") (pinfunction "E_1") (pintype "passive"))
      (node (ref "Q20") (pin "1") (pinfunction "E_1") (pintype "passive"))
      (node (ref "Q21") (pin "1") (pinfunction "E_1") (pintype "passive"))
      (node (ref "Q22") (pin "1") (pinfunction "E_1") (pintype "passive"))
      (node (ref "Q23") (pin "1") (pinfunction "E_1") (pintype "passive"))
      (node (ref "Q24") (pin "1") (pinfunction "E_1") (pintype "passive"))
      (node (ref "Q25") (pin "1") (pinfunction "E_1") (pintype "passive"))
      (node (ref "Q26") (pin "1") (pinfunction "E_1") (pintype "passive"))
      (node (ref "Q27") (pin "1") (pinfunction "E_1") (pintype "passive"))
      (node (ref "Q28") (pin "1") (pinfunction "E_1") (pintype "passive"))
      (node (ref "Q3") (pin "1") (pinfunction "E_1") (pintype "passive"))
      (node (ref "Q4") (pin "1") (pinfunction "E_1") (pintype "passive"))
      (node (ref "Q5") (pin "1") (pinfunction "E_1") (pintype "passive"))
      (node (ref "Q6") (pin "1") (pinfunction "E_1") (pintype "passive"))
      (node (ref "Q7") (pin "1") (pinfunction "E_1") (pintype "passive"))
      (node (ref "Q8") (pin "1") (pinfunction "E_1") (pintype "passive"))
      (node (ref "Q9") (pin "1") (pinfunction "E_1") (pintype "passive"))
      (node (ref "R102") (pin "1") (pinfunction "1_1") (pintype "passive"))
      (node (ref "R146") (pin "2") (pinfunction "2_2") (pintype "passive"))
      (node (ref "R165") (pin "1") (pinfunction "1_1") (pintype "passive"))
      (node (ref "R32") (pin "1") (pinfunction "1_1") (pintype "passive"))
      (node (ref "R37") (pin "1") (pinfunction "1_1") (pintype "passive"))
      (node (ref "R71") (pin "1") (pinfunction "1_1") (pintype "passive"))
      (node (ref "R75") (pin "1") (pinfunction "1_1") (pintype "passive"))
      (node (ref "R76") (pin "1") (pinfunction "1_1") (pintype "passive"))
      (node (ref "R77") (pin "1") (pinfunction "1_1") (pintype "passive"))
      (node (ref "R86") (pin "1") (pinfunction "1_1") (pintype "passive"))
      (node (ref "R93") (pin "1") (pinfunction "1_1") (pintype "passive"))
      (node (ref "R97") (pin "1") (pinfunction "1_1") (pintype "passive"))
    )
    (net (code "25") (name "GRN_DELAY") (class "Default")
      (node (ref "E2") (pin "13") (pinfunction "Q_13") (pintype "output"))
      (node (ref "E3") (pin "3") (pinfunction "I1_3") (pintype "input"))
      (node (ref "E3") (pin "8") (pinfunction "I0_8") (pintype "input"))
      (node (ref "TP2") (pin "TP") (pinfunction "TP_TP") (pintype "input"))
    )
    (net (code "26") (name "INITIALIZE") (class "Default")
      (node (ref "E24") (pin "9") (pinfunction "I0_9") (pintype "input"))
      (node (ref "OMNIBUS") (pin "CR1") (pinfunction "1_CR1") (pintype "bidirectional"))
    )
    (net (code "27") (name "INTENS") (class "Default")
      (node (ref "C63") (pin "1") (pinfunction "1_1") (pintype "passive"))
      (node (ref "F") (pin "S1") (pinfunction "P_S1") (pintype "passive"))
      (node (ref "F1") (pin "S1") (pinfunction "P_S1") (pintype "passive"))
      (node (ref "H1") (pin "D1") (pinfunction "P_D1") (pintype "passive"))
      (node (ref "R78") (pin "1") (pinfunction "1_1") (pintype "passive"))
      (node (ref "R79") (pin "1") (pinfunction "1_1") (pintype "passive"))
      (node (ref "S1") (pin "2") (pinfunction "A2_2") (pintype "bidirectional"))
    )
    (net (code "28") (name "INT_EN") (class "Default")
      (node (ref "E16") (pin "6") (pinfunction "I1_6") (pintype "input"))
      (node (ref "E17") (pin "6") (pinfunction "I1_6") (pintype "input"))
      (node (ref "E18") (pin "9") (pinfunction "Q_9") (pintype "output"))
    )
    (net (code "29") (name "IOT") (class "Default")
      (node (ref "E12") (pin "3") (pinfunction "O_3") (pintype "output"))
      (node (ref "E17") (pin "8") (pinfunction "I0_8") (pintype "input"))
      (node (ref "E17") (pin "9") (pinfunction "I1_9") (pintype "input"))
      (node (ref "E28") (pin "11") (pinfunction "I_11") (pintype "input"))
    )
    (net (code "30") (name "LD_EN_REG") (class "Default")
      (node (ref "E18") (pin "11") (pinfunction "CLK_11") (pintype "input"))
      (node (ref "E18") (pin "3") (pinfunction "CLK_3") (pintype "input"))
      (node (ref "E20") (pin "1") (pinfunction "O_1") (pintype "output"))
      (node (ref "E5") (pin "11") (pinfunction "CLK_11") (pintype "input"))
      (node (ref "E5") (pin "3") (pinfunction "CLK_3") (pintype "input"))
      (node (ref "E6") (pin "11") (pinfunction "CLK_11") (pintype "input"))
      (node (ref "E6") (pin "3") (pinfunction "CLK_3") (pintype "input"))
    )
    (net (code "31") (name "LOAD_X") (class "Default")
      (node (ref "E22") (pin "8") (pinfunction "O_8") (pintype "output"))
      (node (ref "E34") (pin "11") (pinfunction "LD_11") (pintype "input"))
      (node (ref "E36") (pin "11") (pinfunction "LD_11") (pintype "input"))
      (node (ref "E38") (pin "11") (pinfunction "LD_11") (pintype "input"))
      (node (ref "F") (pin "V2") (pinfunction "P_V2") (pintype "passive"))
      (node (ref "F1") (pin "V2") (pinfunction "P_V2") (pintype "passive"))
    )
    (net (code "32") (name "LOAD_Y") (class "Default")
      (node (ref "E22") (pin "11") (pinfunction "O_11") (pintype "output"))
      (node (ref "E33") (pin "11") (pinfunction "LD_11") (pintype "input"))
      (node (ref "E35") (pin "11") (pinfunction "LD_11") (pintype "input"))
      (node (ref "E37") (pin "11") (pinfunction "LD_11") (pintype "input"))
      (node (ref "F") (pin "U2") (pinfunction "P_U2") (pintype "passive"))
      (node (ref "F1") (pin "U2") (pinfunction "P_U2") (pintype "passive"))
    )
    (net (code "33") (name "Net-(C62-Pad+)") (class "Default")
      (node (ref "C62") (pin "+") (pinfunction "+_+") (pintype "passive"))
      (node (ref "R73") (pin "E") (pinfunction "E_E") (pintype "passive"))
      (node (ref "R74") (pin "E") (pinfunction "E_E") (pintype "passive"))
      (node (ref "R75") (pin "2") (pinfunction "2_2") (pintype "passive"))
    )
    (net (code "34") (name "Net-(C66-Pad1)") (class "Default")
      (node (ref "C66") (pin "1") (pinfunction "1_1") (pintype "passive"))
      (node (ref "R91") (pin "2") (pinfunction "2_2") (pintype "passive"))
    )
    (net (code "35") (name "Net-(C69-Pad1)") (class "Default")
      (node (ref "C69") (pin "1") (pinfunction "1_1") (pintype "passive"))
      (node (ref "R141") (pin "1") (pinfunction "1_1") (pintype "passive"))
      (node (ref "R142") (pin "2") (pinfunction "2_2") (pintype "passive"))
    )
    (net (code "36") (name "Net-(C70-Pad1)") (class "Default")
      (node (ref "C70") (pin "1") (pinfunction "1_1") (pintype "passive"))
      (node (ref "R136") (pin "1") (pinfunction "1_1") (pintype "passive"))
      (node (ref "R137") (pin "2") (pinfunction "2_2") (pintype "passive"))
      (node (ref "R144") (pin "2") (pinfunction "2_2") (pintype "passive"))
      (node (ref "R92") (pin "2") (pinfunction "2_2") (pintype "passive"))
      (node (ref "R94") (pin "1") (pinfunction "1_1") (pintype "passive"))
      (node (ref "W9") (pin "2") (pinfunction "2_2") (pintype "passive"))
    )
    (net (code "37") (name "Net-(C71-Pad1)") (class "Default")
      (node (ref "C71") (pin "1") (pinfunction "1_1") (pintype "passive"))
      (node (ref "R150") (pin "1") (pinfunction "1_1") (pintype "passive"))
      (node (ref "R151") (pin "2") (pinfunction "2_2") (pintype "passive"))
    )
    (net (code "38") (name "Net-(C72-Pad1)") (class "Default")
      (node (ref "C72") (pin "1") (pinfunction "1_1") (pintype "passive"))
      (node (ref "R164") (pin "2") (pinfunction "2_2") (pintype "passive"))
    )
    (net (code "39") (name "Net-(C74-Pad1)") (class "Default")
      (node (ref "C74") (pin "1") (pinfunction "1_1") (pintype "passive"))
      (node (ref "R154") (pin "2") (pinfunction "2_2") (pintype "passive"))
      (node (ref "R156") (pin "2") (pinfunction "2_2") (pintype "passive"))
      (node (ref "R157") (pin "2") (pinfunction "2_2") (pintype "passive"))
      (node (ref "R166") (pin "1") (pinfunction "1_1") (pintype "passive"))
      (node (ref "R167") (pin "1") (pinfunction "1_1") (pintype "passive"))
      (node (ref "W10") (pin "2") (pinfunction "2_2") (pintype "passive"))
    )
    (net (code "40") (name "Net-(D2-PadC)") (class "Default")
      (node (ref "D2") (pin "C") (pinfunction "C_C") (pintype "passive"))
      (node (ref "R9") (pin "1") (pinfunction "1_1") (pintype "passive"))
      (node (ref "W3") (pin "1") (pinfunction "1_1") (pintype "passive"))
    )
    (net (code "41") (name "Net-(D3-PadA)") (class "Default")
      (node (ref "D3") (pin "A") (pinfunction "A_A") (pintype "passive"))
      (node (ref "D4") (pin "A") (pinfunction "A_A") (pintype "passive"))
      (node (ref "R34") (pin "1") (pinfunction "1_1") (pintype "passive"))
    )
    (net (code "42") (name "Net-(D5-PadA)") (class "Default")
      (node (ref "D5") (pin "A") (pinfunction "A_A") (pintype "passive"))
      (node (ref "R33") (pin "1") (pinfunction "1_1") (pintype "passive"))
      (node (ref "R34") (pin "2") (pinfunction "2_2") (pintype "passive"))
    )
    (net (code "43") (name "Net-(D6-PadA)") (class "Default")
      (node (ref "D6") (pin "A") (pinfunction "A_A") (pintype "passive"))
      (node (ref "D7") (pin "A") (pinfunction "A_A") (pintype "passive"))
      (node (ref "R39") (pin "1") (pinfunction "1_1") (pintype "passive"))
    )
    (net (code "44") (name "Net-(D8-PadA)") (class "Default")
      (node (ref "D8") (pin "A") (pinfunction "A_A") (pintype "passive"))
      (node (ref "R38") (pin "1") (pinfunction "1_1") (pintype "passive"))
      (node (ref "R39") (pin "2") (pinfunction "2_2") (pintype "passive"))
    )
    (net (code "45") (name "Net-(D10-PadA)") (class "Default")
      (node (ref "D10") (pin "A") (pinfunction "A_A") (pintype "passive"))
      (node (ref "R41") (pin "1") (pinfunction "1_1") (pintype "passive"))
      (node (ref "R42") (pin "2") (pinfunction "2_2") (pintype "passive"))
    )
    (net (code "46") (name "Net-(D12-PadA)") (class "Default")
      (node (ref "D12") (pin "A") (pinfunction "A_A") (pintype "passive"))
      (node (ref "R44") (pin "1") (pinfunction "1_1") (pintype "passive"))
      (node (ref "R45") (pin "2") (pinfunction "2_2") (pintype "passive"))
    )
    (net (code "47") (name "Net-(D14-PadA)") (class "Default")
      (node (ref "D14") (pin "A") (pinfunction "A_A") (pintype "passive"))
      (node (ref "R47") (pin "1") (pinfunction "1_1") (pintype "passive"))
      (node (ref "R48") (pin "2") (pinfunction "2_2") (pintype "passive"))
    )
    (net (code "48") (name "Net-(D16-PadA)") (class "Default")
      (node (ref "D16") (pin "A") (pinfunction "A_A") (pintype "passive"))
      (node (ref "R50") (pin "1") (pinfunction "1_1") (pintype "passive"))
      (node (ref "R65") (pin "E") (pinfunction "E_E") (pintype "passive"))
      (node (ref "W7") (pin "1") (pinfunction "1_1") (pintype "passive"))
    )
    (net (code "49") (name "Net-(D18-PadA)") (class "Default")
      (node (ref "D18") (pin "A") (pinfunction "A_A") (pintype "passive"))
      (node (ref "R53") (pin "1") (pinfunction "1_1") (pintype "passive"))
      (node (ref "R66") (pin "E") (pinfunction "E_E") (pintype "passive"))
    )
    (net (code "50") (name "Net-(D20-PadA)") (class "Default")
      (node (ref "D20") (pin "A") (pinfunction "A_A") (pintype "passive"))
      (node (ref "R56") (pin "1") (pinfunction "1_1") (pintype "passive"))
      (node (ref "R67") (pin "E") (pinfunction "E_E") (pintype "passive"))
    )
    (net (code "51") (name "Net-(D22-PadA)") (class "Default")
      (node (ref "D22") (pin "A") (pinfunction "A_A") (pintype "passive"))
      (node (ref "R59") (pin "1") (pinfunction "1_1") (pintype "passive"))
      (node (ref "R68") (pin "E") (pinfunction "E_E") (pintype "passive"))
    )
    (net (code "52") (name "Net-(D24-PadA)") (class "Default")
      (node (ref "D24") (pin "A") (pinfunction "A_A") (pintype "passive"))
      (node (ref "R62") (pin "1") (pinfunction "1_1") (pintype "passive"))
      (node (ref "R69") (pin "E") (pinfunction "E_E") (pintype "passive"))
    )
    (net (code "53") (name "Net-(D30-PadA)") (class "Default")
      (node (ref "D30") (pin "A") (pinfunction "A_A") (pintype "passive"))
      (node (ref "D31") (pin "A") (pinfunction "A_A") (pintype "passive"))
      (node (ref "R99") (pin "1") (pinfunction "1_1") (pintype "passive"))
    )
    (net (code "54") (name "Net-(D32-PadA)") (class "Default")
      (node (ref "D32") (pin "A") (pinfunction "A_A") (pintype "passive"))
      (node (ref "R98") (pin "1") (pinfunction "1_1") (pintype "passive"))
      (node (ref "R99") (pin "2") (pinfunction "2_2") (pintype "passive"))
    )
    (net (code "55") (name "Net-(D33-PadA)") (class "Default")
      (node (ref "D33") (pin "A") (pinfunction "A_A") (pintype "passive"))
      (node (ref "D34") (pin "A") (pinfunction "A_A") (pintype "passive"))
      (node (ref "R104") (pin "1") (pinfunction "1_1") (pintype "passive"))
    )
    (net (code "56") (name "Net-(D35-PadA)") (class "Default")
      (node (ref "D35") (pin "A") (pinfunction "A_A") (pintype "passive"))
      (node (ref "R103") (pin "1") (pinfunction "1_1") (pintype "passive"))
      (node (ref "R104") (pin "2") (pinfunction "2_2") (pintype "passive"))
    )
    (net (code "57") (name "Net-(D36-PadA)") (class "Default")
      (node (ref "D36") (pin "A") (pinfunction "A_A") (pintype "passive"))
      (node (ref "R106") (pin "1") (pinfunction "1_1") (pintype "passive"))
      (node (ref "R107") (pin "2") (pinfunction "2_2") (pintype "passive"))
    )
    (net (code "58") (name "Net-(D38-PadA)") (class "Default")
      (node (ref "D38") (pin "A") (pinfunction "A_A") (pintype "passive"))
      (node (ref "R109") (pin "1") (pinfunction "1_1") (pintype "passive"))
      (node (ref "R110") (pin "2") (pinfunction "2_2") (pintype "passive"))
    )
    (net (code "59") (name "Net-(D40-PadA)") (class "Default")
      (node (ref "D40") (pin "A") (pinfunction "A_A") (pintype "passive"))
      (node (ref "R112") (pin "1") (pinfunction "1_1") (pintype "passive"))
      (node (ref "R113") (pin "2") (pinfunction "2_2") (pintype "passive"))
    )
    (net (code "60") (name "Net-(D42-PadA)") (class "Default")
      (node (ref "D42") (pin "A") (pinfunction "A_A") (pintype "passive"))
      (node (ref "R115") (pin "1") (pinfunction "1_1") (pintype "passive"))
      (node (ref "R116") (pin "E") (pinfunction "E_E") (pintype "passive"))
      (node (ref "W6") (pin "1") (pinfunction "1_1") (pintype "passive"))
    )
    (net (code "61") (name "Net-(D44-PadA)") (class "Default")
      (node (ref "D44") (pin "A") (pinfunction "A_A") (pintype "passive"))
      (node (ref "R120") (pin "1") (pinfunction "1_1") (pintype "passive"))
      (node (ref "R121") (pin "E") (pinfunction "E_E") (pintype "passive"))
    )
    (net (code "62") (name "Net-(D46-PadA)") (class "Default")
      (node (ref "D46") (pin "A") (pinfunction "A_A") (pintype "passive"))
      (node (ref "R124") (pin "1") (pinfunction "1_1") (pintype "passive"))
      (node (ref "R125") (pin "E") (pinfunction "E_E") (pintype "passive"))
    )
    (net (code "63") (name "Net-(D48-PadA)") (class "Default")
      (node (ref "D48") (pin "A") (pinfunction "A_A") (pintype "passive"))
      (node (ref "R128") (pin "1") (pinfunction "1_1") (pintype "passive"))
      (node (ref "R129") (pin "E") (pinfunction "E_E") (pintype "passive"))
    )
    (net (code "64") (name "Net-(D50-PadA)") (class "Default")
      (node (ref "D50") (pin "A") (pinfunction "A_A") (pintype "passive"))
      (node (ref "R132") (pin "1") (pinfunction "1_1") (pintype "passive"))
      (node (ref "R133") (pin "E") (pinfunction "E_E") (pintype "passive"))
    )
    (net (code "65") (name "Net-(D54-PadA)") (class "Default")
      (node (ref "D54") (pin "A") (pinfunction "A_A") (pintype "passive"))
      (node (ref "D55") (pin "A") (pinfunction "A_A") (pintype "passive"))
    )
    (net (code "66") (name "Net-(D56-PadA)") (class "Default")
      (node (ref "D56") (pin "A") (pinfunction "A_A") (pintype "passive"))
      (node (ref "D57") (pin "A") (pinfunction "A_A") (pintype "passive"))
    )
    (net (code "67") (name "Net-(E1A-A)") (class "Default")
      (node (ref "E1") (pin "1") (pinfunction "A_1") (pintype "input"))
      (node (ref "E3") (pin "10") (pinfunction "O_10") (pintype "output"))
    )
    (net (code "68") (name "Net-(E1A-C)") (class "Default")
      (node (ref "C36") (pin "1") (pinfunction "1_1") (pintype "passive"))
      (node (ref "E1") (pin "14") (pinfunction "C_14") (pintype "input"))
    )
    (net (code "69") (name "Net-(E1A-Q)") (class "Default")
      (node (ref "E1") (pin "13") (pinfunction "Q_13") (pintype "output"))
      (node (ref "E3") (pin "11") (pinfunction "I0_11") (pintype "input"))
    )
    (net (code "70") (name "Net-(E1A-R{slash}C)") (class "Default")
      (node (ref "C36") (pin "2") (pinfunction "2_2") (pintype "passive"))
      (node (ref "E1") (pin "15") (pinfunction "R/C_15") (pintype "input"))
      (node (ref "R4") (pin "1") (pinfunction "1_1") (pintype "passive"))
    )
    (net (code "71") (name "Net-(E1B-A)") (class "Default")
      (node (ref "E1") (pin "9") (pinfunction "A_9") (pintype "input"))
      (node (ref "Q1") (pin "3") (pinfunction "C_3") (pintype "passive"))
      (node (ref "R15") (pin "1") (pinfunction "1_1") (pintype "passive"))
    )
    (net (code "72") (name "Net-(E1B-B)") (class "Default")
      (node (ref "E1") (pin "10") (pinfunction "B_10") (pintype "input"))
      (node (ref "E1") (pin "11") (pinfunction "CLR_11") (pintype "input"))
      (node (ref "R22") (pin "1") (pinfunction "1_1") (pintype "passive"))
    )
    (net (code "73") (name "Net-(E1B-C)") (class "Default")
      (node (ref "C37") (pin "1") (pinfunction "1_1") (pintype "passive"))
      (node (ref "E1") (pin "6") (pinfunction "C_6") (pintype "input"))
    )
    (net (code "74") (name "Net-(E1B-R{slash}C)") (class "Default")
      (node (ref "C37") (pin "2") (pinfunction "2_2") (pintype "passive"))
      (node (ref "E1") (pin "7") (pinfunction "R/C_7") (pintype "input"))
      (node (ref "R7") (pin "1") (pinfunction "1_1") (pintype "passive"))
    )
    (net (code "75") (name "Net-(E2A-C)") (class "Default")
      (node (ref "C34") (pin "1") (pinfunction "1_1") (pintype "passive"))
      (node (ref "C35") (pin "1") (pinfunction "1_1") (pintype "passive"))
      (node (ref "E2") (pin "14") (pinfunction "C_14") (pintype "input"))
    )
    (net (code "76") (name "Net-(E2A-R{slash}C)") (class "Default")
      (node (ref "C34") (pin "2") (pinfunction "2_2") (pintype "passive"))
      (node (ref "C35") (pin "2") (pinfunction "2_2") (pintype "passive"))
      (node (ref "E2") (pin "15") (pinfunction "R/C_15") (pintype "input"))
      (node (ref "R19") (pin "1") (pinfunction "1_1") (pintype "passive"))
    )
    (net (code "77") (name "Net-(E2B-C)") (class "Default")
      (node (ref "C33") (pin "1") (pinfunction "1_1") (pintype "passive"))
      (node (ref "E2") (pin "6") (pinfunction "C_6") (pintype "input"))
    )
    (net (code "78") (name "Net-(E2B-R{slash}C)") (class "Default")
      (node (ref "C33") (pin "2") (pinfunction "2_2") (pintype "passive"))
      (node (ref "E2") (pin "7") (pinfunction "R/C_7") (pintype "input"))
      (node (ref "R20") (pin "1") (pinfunction "1_1") (pintype "passive"))
    )
    (net (code "79") (name "Net-(E3B-O)") (class "Default")
      (node (ref "E3") (pin "4") (pinfunction "O_4") (pintype "output"))
      (node (ref "E6") (pin "1") (pinfunction "CLR_1") (pintype "input"))
    )
    (net (code "80") (name "Net-(E4A-P$5)") (class "Default")
      (node (ref "C38") (pin "2") (pinfunction "2_2") (pintype "passive"))
      (node (ref "C39") (pin "2") (pinfunction "2_2") (pintype "passive"))
      (node (ref "E4") (pin "11") (pinfunction "P$5_11") (pintype "bidirectional"))
    )
    (net (code "81") (name "Net-(E4A-P$6)") (class "Default")
      (node (ref "E4") (pin "13") (pinfunction "P$6_13") (pintype "bidirectional"))
      (node (ref "S2") (pin "2") (pinfunction "A2_2") (pintype "bidirectional"))
      (node (ref "W3") (pin "2") (pinfunction "2_2") (pintype "passive"))
      (node (ref "W4") (pin "1") (pinfunction "1_1") (pintype "passive"))
    )
    (net (code "82") (name "Net-(E5A-D)") (class "Default")
      (node (ref "E5") (pin "2") (pinfunction "D_2") (pintype "input"))
      (node (ref "E9") (pin "14") (pinfunction "O_14") (pintype "output"))
    )
    (net (code "83") (name "Net-(E5B-D)") (class "Default")
      (node (ref "E5") (pin "12") (pinfunction "D_12") (pintype "input"))
      (node (ref "E9") (pin "2") (pinfunction "O_2") (pintype "output"))
    )
    (net (code "84") (name "Net-(E6A-D)") (class "Default")
      (node (ref "E6") (pin "2") (pinfunction "D_2") (pintype "input"))
      (node (ref "E9") (pin "3") (pinfunction "O_3") (pintype "output"))
    )
    (net (code "85") (name "Net-(E6B-D)") (class "Default")
      (node (ref "E6") (pin "12") (pinfunction "D_12") (pintype "input"))
      (node (ref "E9") (pin "13") (pinfunction "O_13") (pintype "output"))
    )
    (net (code "86") (name "Net-(E10C-I)") (class "Default")
      (node (ref "E10") (pin "5") (pinfunction "I_5") (pintype "input"))
      (node (ref "E7") (pin "4") (pinfunction "O_4") (pintype "open_collector"))
      (node (ref "R16") (pin "1") (pinfunction "1_1") (pintype "passive"))
    )
    (net (code "87") (name "Net-(E10C-O)") (class "Default")
      (node (ref "D1") (pin "A") (pinfunction "A_A") (pintype "passive"))
      (node (ref "E10") (pin "6") (pinfunction "O_6") (pintype "open_collector"))
      (node (ref "R17") (pin "1") (pinfunction "1_1") (pintype "passive"))
    )
    (net (code "88") (name "Net-(E10E-O)") (class "Default")
      (node (ref "D2") (pin "A") (pinfunction "A_A") (pintype "passive"))
      (node (ref "E10") (pin "10") (pinfunction "O_10") (pintype "open_collector"))
      (node (ref "R8") (pin "1") (pinfunction "1_1") (pintype "passive"))
    )
    (net (code "89") (name "Net-(E11A-I1)") (class "Default")
      (node (ref "E11") (pin "10") (pinfunction "I1_10") (pintype "input"))
      (node (ref "E11") (pin "11") (pinfunction "I0_11") (pintype "input"))
      (node (ref "E11") (pin "5") (pinfunction "I1_5") (pintype "input"))
      (node (ref "E11") (pin "6") (pinfunction "I0_6") (pintype "input"))
      (node (ref "E12") (pin "5") (pinfunction "I1_5") (pintype "input"))
      (node (ref "E14") (pin "10") (pinfunction "O_10") (pintype "output"))
      (node (ref "R1") (pin "1") (pinfunction "1_1") (pintype "passive"))
    )
    (net (code "90") (name "Net-(E11A-O)") (class "Default")
      (node (ref "E11") (pin "3") (pinfunction "O_3") (pintype "output"))
      (node (ref "W1") (pin "1") (pinfunction "1_1") (pintype "passive"))
    )
    (net (code "91") (name "Net-(E11B-O)") (class "Default")
      (node (ref "E11") (pin "2") (pinfunction "O_2") (pintype "output"))
      (node (ref "E12") (pin "6") (pinfunction "I2_6") (pintype "input"))
    )
    (net (code "92") (name "Net-(E11C-O)") (class "Default")
      (node (ref "E11") (pin "14") (pinfunction "O_14") (pintype "output"))
      (node (ref "E12") (pin "9") (pinfunction "I3_9") (pintype "input"))
    )
    (net (code "93") (name "Net-(E11D-O)") (class "Default")
      (node (ref "E11") (pin "13") (pinfunction "O_13") (pintype "output"))
      (node (ref "E12") (pin "10") (pinfunction "I4_10") (pintype "input"))
    )
    (net (code "94") (name "Net-(E12A-I0)") (class "Default")
      (node (ref "E12") (pin "4") (pinfunction "I0_4") (pintype "input"))
      (node (ref "W1") (pin "2") (pinfunction "2_2") (pintype "passive"))
      (node (ref "W2") (pin "2") (pinfunction "2_2") (pintype "passive"))
    )
    (net (code "95") (name "Net-(E13D-O)") (class "Default")
      (node (ref "E13") (pin "13") (pinfunction "O_13") (pintype "output"))
      (node (ref "E14") (pin "11") (pinfunction "I_11") (pintype "input"))
    )
    (net (code "96") (name "Net-(E15A-P$5)") (class "Default")
      (node (ref "C40") (pin "2") (pinfunction "2_2") (pintype "passive"))
      (node (ref "E15") (pin "11") (pinfunction "P$5_11") (pintype "bidirectional"))
    )
    (net (code "97") (name "Net-(E15A-P$6)") (class "Default")
      (node (ref "C40") (pin "1") (pinfunction "1_1") (pintype "passive"))
      (node (ref "D1") (pin "C") (pinfunction "C_C") (pintype "passive"))
      (node (ref "E15") (pin "13") (pinfunction "P$6_13") (pintype "bidirectional"))
      (node (ref "R18") (pin "1") (pinfunction "1_1") (pintype "passive"))
    )
    (net (code "98") (name "Net-(E16C-I0)") (class "Default")
      (node (ref "E16") (pin "8") (pinfunction "I0_8") (pintype "input"))
      (node (ref "E16") (pin "9") (pinfunction "I1_9") (pintype "input"))
      (node (ref "E26") (pin "3") (pinfunction "O_3") (pintype "output"))
    )
    (net (code "99") (name "Net-(E17A-I0)") (class "Default")
      (node (ref "E17") (pin "2") (pinfunction "I0_2") (pintype "input"))
      (node (ref "E21") (pin "6") (pinfunction "O_6") (pintype "output"))
    )
    (net (code "100") (name "Net-(E17A-I1)") (class "Default")
      (node (ref "E17") (pin "11") (pinfunction "I0_11") (pintype "input"))
      (node (ref "E17") (pin "3") (pinfunction "I1_3") (pintype "input"))
      (node (ref "E17") (pin "5") (pinfunction "I0_5") (pintype "input"))
      (node (ref "E19") (pin "5") (pinfunction "Q_5") (pintype "output"))
    )
    (net (code "101") (name "Net-(E19A-CLK)") (class "Default")
      (node (ref "E19") (pin "3") (pinfunction "CLK_3") (pintype "input"))
      (node (ref "E23") (pin "8") (pinfunction "O_8") (pintype "output"))
    )
    (net (code "102") (name "Net-(E20C-I0)") (class "Default")
      (node (ref "E20") (pin "8") (pinfunction "I0_8") (pintype "input"))
      (node (ref "E21") (pin "10") (pinfunction "O_10") (pintype "output"))
      (node (ref "E22") (pin "9") (pinfunction "I0_9") (pintype "input"))
    )
    (net (code "103") (name "Net-(E20C-I1)") (class "Default")
      (node (ref "E20") (pin "9") (pinfunction "I1_9") (pintype "input"))
      (node (ref "E21") (pin "8") (pinfunction "O_8") (pintype "output"))
      (node (ref "E22") (pin "13") (pinfunction "I1_13") (pintype "input"))
    )
    (net (code "104") (name "Net-(E20D-O)") (class "Default")
      (node (ref "E20") (pin "13") (pinfunction "O_13") (pintype "output"))
      (node (ref "E24") (pin "10") (pinfunction "I1_10") (pintype "input"))
    )
    (net (code "105") (name "Net-(E21A-O)") (class "Default")
      (node (ref "E21") (pin "2") (pinfunction "O_2") (pintype "output"))
      (node (ref "E22") (pin "5") (pinfunction "I1_5") (pintype "input"))
    )
    (net (code "106") (name "Net-(E21B-O)") (class "Default")
      (node (ref "E21") (pin "4") (pinfunction "O_4") (pintype "output"))
      (node (ref "E22") (pin "2") (pinfunction "I1_2") (pintype "input"))
    )
    (net (code "107") (name "Net-(E24A-O)") (class "Default")
      (node (ref "E24") (pin "3") (pinfunction "O_3") (pintype "output"))
      (node (ref "E25") (pin "15") (pinfunction "A_15") (pintype "input"))
    )
    (net (code "108") (name "Net-(E24B-O)") (class "Default")
      (node (ref "E24") (pin "2") (pinfunction "O_2") (pintype "output"))
      (node (ref "E25") (pin "14") (pinfunction "B_14") (pintype "input"))
    )
    (net (code "109") (name "Net-(E24C-O)") (class "Default")
      (node (ref "E24") (pin "14") (pinfunction "O_14") (pintype "output"))
      (node (ref "E28") (pin "9") (pinfunction "I_9") (pintype "input"))
    )
    (net (code "110") (name "Net-(E24D-O)") (class "Default")
      (node (ref "E24") (pin "13") (pinfunction "O_13") (pintype "output"))
      (node (ref "E25") (pin "1") (pinfunction "C_1") (pintype "input"))
    )
    (net (code "111") (name "Net-(E26B-O)") (class "Default")
      (node (ref "E26") (pin "6") (pinfunction "O_6") (pintype "output"))
      (node (ref "E28") (pin "13") (pinfunction "I_13") (pintype "input"))
    )
    (net (code "112") (name "Net-(E26C-O)") (class "Default")
      (node (ref "E26") (pin "12") (pinfunction "I0_12") (pintype "input"))
      (node (ref "E26") (pin "8") (pinfunction "O_8") (pintype "output"))
    )
    (net (code "113") (name "Net-(E27D-O)") (class "Default")
      (node (ref "E27") (pin "11") (pinfunction "O_11") (pintype "output"))
      (node (ref "E28") (pin "3") (pinfunction "I_3") (pintype "input"))
      (node (ref "S1") (pin "1") (pinfunction "A1_1") (pintype "bidirectional"))
    )
    (net (code "114") (name "Net-(E28B-O)") (class "Default")
      (node (ref "E28") (pin "4") (pinfunction "O_4") (pintype "open_collector"))
      (node (ref "R13") (pin "1") (pinfunction "1_1") (pintype "passive"))
      (node (ref "S1") (pin "3") (pinfunction "A3_3") (pintype "bidirectional"))
    )
    (net (code "115") (name "Net-(E29A-O)") (class "Default")
      (node (ref "E29") (pin "2") (pinfunction "O_2") (pintype "output"))
      (node (ref "R61") (pin "1") (pinfunction "1_1") (pintype "passive"))
    )
    (net (code "116") (name "Net-(E29B-O)") (class "Default")
      (node (ref "E29") (pin "4") (pinfunction "O_4") (pintype "output"))
      (node (ref "E41") (pin "5") (pinfunction "B1_5") (pintype "input"))
    )
    (net (code "117") (name "Net-(E29C-O)") (class "Default")
      (node (ref "E29") (pin "6") (pinfunction "O_6") (pintype "output"))
      (node (ref "E41") (pin "2") (pinfunction "B0_2") (pintype "input"))
    )
    (net (code "118") (name "Net-(E29D-O)") (class "Default")
      (node (ref "E29") (pin "8") (pinfunction "O_8") (pintype "output"))
      (node (ref "E39") (pin "5") (pinfunction "B1_5") (pintype "input"))
    )
    (net (code "119") (name "Net-(E29E-O)") (class "Default")
      (node (ref "E29") (pin "10") (pinfunction "O_10") (pintype "output"))
      (node (ref "E39") (pin "2") (pinfunction "B0_2") (pintype "input"))
    )
    (net (code "120") (name "Net-(E29F-O)") (class "Default")
      (node (ref "E29") (pin "12") (pinfunction "O_12") (pintype "output"))
      (node (ref "R131") (pin "1") (pinfunction "1_1") (pintype "passive"))
    )
    (net (code "121") (name "Net-(E30A-O)") (class "Default")
      (node (ref "E30") (pin "2") (pinfunction "O_2") (pintype "output"))
      (node (ref "E39") (pin "14") (pinfunction "B3_14") (pintype "input"))
    )
    (net (code "122") (name "Net-(E30B-O)") (class "Default")
      (node (ref "E30") (pin "4") (pinfunction "O_4") (pintype "output"))
      (node (ref "E40") (pin "5") (pinfunction "B1_5") (pintype "input"))
    )
    (net (code "123") (name "Net-(E30C-O)") (class "Default")
      (node (ref "E30") (pin "6") (pinfunction "O_6") (pintype "output"))
      (node (ref "E40") (pin "2") (pinfunction "B0_2") (pintype "input"))
    )
    (net (code "124") (name "Net-(E30D-O)") (class "Default")
      (node (ref "E30") (pin "8") (pinfunction "O_8") (pintype "output"))
      (node (ref "E40") (pin "14") (pinfunction "B3_14") (pintype "input"))
    )
    (net (code "125") (name "Net-(E30E-O)") (class "Default")
      (node (ref "E30") (pin "10") (pinfunction "O_10") (pintype "output"))
      (node (ref "E40") (pin "11") (pinfunction "B2_11") (pintype "input"))
    )
    (net (code "126") (name "Net-(E30F-O)") (class "Default")
      (node (ref "E30") (pin "12") (pinfunction "O_12") (pintype "output"))
      (node (ref "E39") (pin "11") (pinfunction "B2_11") (pintype "input"))
    )
    (net (code "127") (name "Net-(E33A-DN)") (class "Default")
      (node (ref "E33") (pin "4") (pinfunction "DN_4") (pintype "input"))
      (node (ref "E35") (pin "13") (pinfunction "BO_13") (pintype "output"))
    )
    (net (code "128") (name "Net-(E33A-UP)") (class "Default")
      (node (ref "E33") (pin "5") (pinfunction "UP_5") (pintype "input"))
      (node (ref "E35") (pin "12") (pinfunction "CO_12") (pintype "output"))
    )
    (net (code "129") (name "Net-(E34A-DN)") (class "Default")
      (node (ref "E34") (pin "4") (pinfunction "DN_4") (pintype "input"))
      (node (ref "E36") (pin "13") (pinfunction "BO_13") (pintype "output"))
    )
    (net (code "130") (name "Net-(E34A-UP)") (class "Default")
      (node (ref "E34") (pin "5") (pinfunction "UP_5") (pintype "input"))
      (node (ref "E36") (pin "12") (pinfunction "CO_12") (pintype "output"))
    )
    (net (code "131") (name "Net-(E35A-DN)") (class "Default")
      (node (ref "E35") (pin "4") (pinfunction "DN_4") (pintype "input"))
      (node (ref "E37") (pin "13") (pinfunction "BO_13") (pintype "output"))
    )
    (net (code "132") (name "Net-(E35A-UP)") (class "Default")
      (node (ref "E35") (pin "5") (pinfunction "UP_5") (pintype "input"))
      (node (ref "E37") (pin "12") (pinfunction "CO_12") (pintype "output"))
    )
    (net (code "133") (name "Net-(E36A-DN)") (class "Default")
      (node (ref "E36") (pin "4") (pinfunction "DN_4") (pintype "input"))
      (node (ref "E38") (pin "13") (pinfunction "BO_13") (pintype "output"))
    )
    (net (code "134") (name "Net-(E36A-UP)") (class "Default")
      (node (ref "E36") (pin "5") (pinfunction "UP_5") (pintype "input"))
      (node (ref "E38") (pin "12") (pinfunction "CO_12") (pintype "output"))
    )
    (net (code "135") (name "Net-(E42-+IN)") (class "Default")
      (node (ref "E42") (pin "3") (pinfunction "+IN_3") (pintype "input"))
      (node (ref "R74") (pin "S") (pinfunction "S_S") (pintype "passive"))
    )
    (net (code "136") (name "Net-(E43-+IN)") (class "Default")
      (node (ref "E43") (pin "3") (pinfunction "+IN_3") (pintype "input"))
      (node (ref "R73") (pin "S") (pinfunction "S_S") (pintype "passive"))
    )
    (net (code "137") (name "Net-(E44-+IN)") (class "Default")
      (node (ref "E44") (pin "3") (pinfunction "+IN_3") (pintype "input"))
      (node (ref "R93") (pin "2") (pinfunction "2_2") (pintype "passive"))
    )
    (net (code "138") (name "Net-(E44--IN)") (class "Default")
      (node (ref "C70") (pin "2") (pinfunction "2_2") (pintype "passive"))
      (node (ref "D11") (pin "C") (pinfunction "C_C") (pintype "passive"))
      (node (ref "D13") (pin "C") (pinfunction "C_C") (pintype "passive"))
      (node (ref "D15") (pin "C") (pinfunction "C_C") (pintype "passive"))
      (node (ref "D17") (pin "C") (pinfunction "C_C") (pintype "passive"))
      (node (ref "D19") (pin "C") (pinfunction "C_C") (pintype "passive"))
      (node (ref "D21") (pin "C") (pinfunction "C_C") (pintype "passive"))
      (node (ref "D23") (pin "C") (pinfunction "C_C") (pintype "passive"))
      (node (ref "D4") (pin "C") (pinfunction "C_C") (pintype "passive"))
      (node (ref "D7") (pin "C") (pinfunction "C_C") (pintype "passive"))
      (node (ref "D9") (pin "C") (pinfunction "C_C") (pintype "passive"))
      (node (ref "E44") (pin "2") (pinfunction "-IN_2") (pintype "input"))
      (node (ref "R142") (pin "1") (pinfunction "1_1") (pintype "passive"))
      (node (ref "R143") (pin "1") (pinfunction "1_1") (pintype "passive"))
      (node (ref "R145") (pin "2") (pinfunction "2_2") (pintype "passive"))
    )
    (net (code "139") (name "Net-(E44-ON1)") (class "Default")
      (node (ref "E44") (pin "1") (pinfunction "ON1_1") (pintype "passive"))
      (node (ref "R91") (pin "1") (pinfunction "1_1") (pintype "passive"))
    )
    (net (code "140") (name "Net-(E44-ON2)") (class "Default")
      (node (ref "C66") (pin "2") (pinfunction "2_2") (pintype "passive"))
      (node (ref "E44") (pin "8") (pinfunction "ON2_8") (pintype "passive"))
    )
    (net (code "141") (name "Net-(E44-OPT)") (class "Default")
      (node (ref "E44") (pin "5") (pinfunction "OPT_5") (pintype "passive"))
      (node (ref "R94") (pin "2") (pinfunction "2_2") (pintype "passive"))
    )
    (net (code "142") (name "Net-(E44-OUT)") (class "Default")
      (node (ref "D27") (pin "C") (pinfunction "C_C") (pintype "passive"))
      (node (ref "D28") (pin "C") (pinfunction "C_C") (pintype "passive"))
      (node (ref "D56") (pin "C") (pinfunction "C_C") (pintype "passive"))
      (node (ref "E44") (pin "6") (pinfunction "OUT_6") (pintype "output"))
    )
    (net (code "143") (name "Net-(E44-V+)") (class "Default")
      (node (ref "C75") (pin "+") (pinfunction "+_+") (pintype "passive"))
      (node (ref "E44") (pin "7") (pinfunction "V+_7") (pintype "power_in"))
      (node (ref "R88") (pin "1") (pinfunction "1_1") (pintype "passive"))
      (node (ref "R89") (pin "1") (pinfunction "1_1") (pintype "passive"))
      (node (ref "R90") (pin "1") (pinfunction "1_1") (pintype "passive"))
    )
    (net (code "144") (name "Net-(E44-V-)") (class "Default")
      (node (ref "C76") (pin "-") (pinfunction "-_-") (pintype "passive"))
      (node (ref "E44") (pin "4") (pinfunction "V-_4") (pintype "power_in"))
      (node (ref "R138") (pin "1") (pinfunction "1_1") (pintype "passive"))
      (node (ref "R139") (pin "1") (pinfunction "1_1") (pintype "passive"))
      (node (ref "R140") (pin "2") (pinfunction "2_2") (pintype "passive"))
    )
    (net (code "145") (name "Net-(E45-+IN)") (class "Default")
      (node (ref "E45") (pin "3") (pinfunction "+IN_3") (pintype "input"))
      (node (ref "R165") (pin "2") (pinfunction "2_2") (pintype "passive"))
    )
    (net (code "146") (name "Net-(E45--IN)") (class "Default")
      (node (ref "C74") (pin "2") (pinfunction "2_2") (pintype "passive"))
      (node (ref "D31") (pin "C") (pinfunction "C_C") (pintype "passive"))
      (node (ref "D34") (pin "C") (pinfunction "C_C") (pintype "passive"))
      (node (ref "D37") (pin "C") (pinfunction "C_C") (pintype "passive"))
      (node (ref "D39") (pin "C") (pinfunction "C_C") (pintype "passive"))
      (node (ref "D41") (pin "C") (pinfunction "C_C") (pintype "passive"))
      (node (ref "D43") (pin "C") (pinfunction "C_C") (pintype "passive"))
      (node (ref "D45") (pin "C") (pinfunction "C_C") (pintype "passive"))
      (node (ref "D47") (pin "C") (pinfunction "C_C") (pintype "passive"))
      (node (ref "D49") (pin "C") (pinfunction "C_C") (pintype "passive"))
      (node (ref "D51") (pin "C") (pinfunction "C_C") (pintype "passive"))
      (node (ref "E45") (pin "2") (pinfunction "-IN_2") (pintype "input"))
      (node (ref "R149") (pin "2") (pinfunction "2_2") (pintype "passive"))
      (node (ref "R151") (pin "1") (pinfunction "1_1") (pintype "passive"))
      (node (ref "R155") (pin "1") (pinfunction "1_1") (pintype "passive"))
    )
    (net (code "147") (name "Net-(E45-ON1)") (class "Default")
      (node (ref "E45") (pin "1") (pinfunction "ON1_1") (pintype "passive"))
      (node (ref "R164") (pin "1") (pinfunction "1_1") (pintype "passive"))
    )
    (net (code "148") (name "Net-(E45-ON2)") (class "Default")
      (node (ref "C72") (pin "2") (pinfunction "2_2") (pintype "passive"))
      (node (ref "E45") (pin "8") (pinfunction "ON2_8") (pintype "passive"))
    )
    (net (code "149") (name "Net-(E45-OPT)") (class "Default")
      (node (ref "E45") (pin "5") (pinfunction "OPT_5") (pintype "passive"))
      (node (ref "R166") (pin "2") (pinfunction "2_2") (pintype "passive"))
    )
    (net (code "150") (name "Net-(E45-OUT)") (class "Default")
      (node (ref "D52") (pin "C") (pinfunction "C_C") (pintype "passive"))
      (node (ref "D53") (pin "C") (pinfunction "C_C") (pintype "passive"))
      (node (ref "D54") (pin "C") (pinfunction "C_C") (pintype "passive"))
      (node (ref "E45") (pin "6") (pinfunction "OUT_6") (pintype "output"))
    )
    (net (code "151") (name "Net-(E45-V+)") (class "Default")
      (node (ref "C77") (pin "+") (pinfunction "+_+") (pintype "passive"))
      (node (ref "E45") (pin "7") (pinfunction "V+_7") (pintype "power_in"))
      (node (ref "R161") (pin "2") (pinfunction "2_2") (pintype "passive"))
      (node (ref "R162") (pin "2") (pinfunction "2_2") (pintype "passive"))
      (node (ref "R163") (pin "1") (pinfunction "1_1") (pintype "passive"))
    )
    (net (code "152") (name "Net-(E45-V-)") (class "Default")
      (node (ref "C78") (pin "-") (pinfunction "-_-") (pintype "passive"))
      (node (ref "E45") (pin "4") (pinfunction "V-_4") (pintype "power_in"))
      (node (ref "R158") (pin "2") (pinfunction "2_2") (pintype "passive"))
      (node (ref "R159") (pin "1") (pinfunction "1_1") (pintype "passive"))
      (node (ref "R160") (pin "1") (pinfunction "1_1") (pintype "passive"))
    )
    (net (code "153") (name "Net-(OMNIBUS1DH-1)") (class "Default")
      (node (ref "OMNIBUS1") (pin "DB2") (pinfunction "1_DB2") (pintype "bidirectional"))
      (node (ref "R84") (pin "1") (pinfunction "1_1") (pintype "passive"))
      (node (ref "R85") (pin "1") (pinfunction "1_1") (pintype "passive"))
    )
    (net (code "154") (name "Net-(Q1-B)") (class "Default")
      (node (ref "Q1") (pin "2") (pinfunction "B_2") (pintype "passive"))
      (node (ref "R14") (pin "2") (pinfunction "2_2") (pintype "passive"))
    )
    (net (code "155") (name "Net-(Q2-B)") (class "Default")
      (node (ref "Q2") (pin "2") (pinfunction "B_2") (pintype "passive"))
      (node (ref "R30") (pin "2") (pinfunction "2_2") (pintype "passive"))
    )
    (net (code "156") (name "Net-(Q2-C)") (class "Default")
      (node (ref "D3") (pin "C") (pinfunction "C_C") (pintype "passive"))
      (node (ref "Q2") (pin "3") (pinfunction "C_3") (pintype "passive"))
      (node (ref "R31") (pin "1") (pinfunction "1_1") (pintype "passive"))
      (node (ref "R32") (pin "2") (pinfunction "2_2") (pintype "passive"))
    )
    (net (code "157") (name "Net-(Q3-B)") (class "Default")
      (node (ref "Q3") (pin "2") (pinfunction "B_2") (pintype "passive"))
      (node (ref "R35") (pin "2") (pinfunction "2_2") (pintype "passive"))
    )
    (net (code "158") (name "Net-(Q3-C)") (class "Default")
      (node (ref "D6") (pin "C") (pinfunction "C_C") (pintype "passive"))
      (node (ref "Q3") (pin "3") (pinfunction "C_3") (pintype "passive"))
      (node (ref "R36") (pin "1") (pinfunction "1_1") (pintype "passive"))
      (node (ref "R37") (pin "2") (pinfunction "2_2") (pintype "passive"))
    )
    (net (code "159") (name "Net-(Q4-B)") (class "Default")
      (node (ref "Q4") (pin "2") (pinfunction "B_2") (pintype "passive"))
      (node (ref "R40") (pin "2") (pinfunction "2_2") (pintype "passive"))
    )
    (net (code "160") (name "Net-(Q4-C)") (class "Default")
      (node (ref "D9") (pin "A") (pinfunction "A_A") (pintype "passive"))
      (node (ref "Q4") (pin "3") (pinfunction "C_3") (pintype "passive"))
      (node (ref "R42") (pin "1") (pinfunction "1_1") (pintype "passive"))
    )
    (net (code "161") (name "Net-(Q5-B)") (class "Default")
      (node (ref "Q5") (pin "2") (pinfunction "B_2") (pintype "passive"))
      (node (ref "R43") (pin "2") (pinfunction "2_2") (pintype "passive"))
    )
    (net (code "162") (name "Net-(Q5-C)") (class "Default")
      (node (ref "D11") (pin "A") (pinfunction "A_A") (pintype "passive"))
      (node (ref "Q5") (pin "3") (pinfunction "C_3") (pintype "passive"))
      (node (ref "R45") (pin "1") (pinfunction "1_1") (pintype "passive"))
    )
    (net (code "163") (name "Net-(Q6-B)") (class "Default")
      (node (ref "Q6") (pin "2") (pinfunction "B_2") (pintype "passive"))
      (node (ref "R46") (pin "2") (pinfunction "2_2") (pintype "passive"))
    )
    (net (code "164") (name "Net-(Q6-C)") (class "Default")
      (node (ref "D13") (pin "A") (pinfunction "A_A") (pintype "passive"))
      (node (ref "Q6") (pin "3") (pinfunction "C_3") (pintype "passive"))
      (node (ref "R48") (pin "1") (pinfunction "1_1") (pintype "passive"))
    )
    (net (code "165") (name "Net-(Q7-B)") (class "Default")
      (node (ref "Q7") (pin "2") (pinfunction "B_2") (pintype "passive"))
      (node (ref "R49") (pin "2") (pinfunction "2_2") (pintype "passive"))
    )
    (net (code "166") (name "Net-(Q7-C)") (class "Default")
      (node (ref "D15") (pin "A") (pinfunction "A_A") (pintype "passive"))
      (node (ref "Q7") (pin "3") (pinfunction "C_3") (pintype "passive"))
      (node (ref "R51") (pin "1") (pinfunction "1_1") (pintype "passive"))
    )
    (net (code "167") (name "Net-(Q8-B)") (class "Default")
      (node (ref "Q8") (pin "2") (pinfunction "B_2") (pintype "passive"))
      (node (ref "R52") (pin "2") (pinfunction "2_2") (pintype "passive"))
    )
    (net (code "168") (name "Net-(Q8-C)") (class "Default")
      (node (ref "D17") (pin "A") (pinfunction "A_A") (pintype "passive"))
      (node (ref "Q8") (pin "3") (pinfunction "C_3") (pintype "passive"))
      (node (ref "R54") (pin "1") (pinfunction "1_1") (pintype "passive"))
    )
    (net (code "169") (name "Net-(Q9-B)") (class "Default")
      (node (ref "Q9") (pin "2") (pinfunction "B_2") (pintype "passive"))
      (node (ref "R55") (pin "2") (pinfunction "2_2") (pintype "passive"))
    )
    (net (code "170") (name "Net-(Q9-C)") (class "Default")
      (node (ref "D19") (pin "A") (pinfunction "A_A") (pintype "passive"))
      (node (ref "Q9") (pin "3") (pinfunction "C_3") (pintype "passive"))
      (node (ref "R57") (pin "1") (pinfunction "1_1") (pintype "passive"))
    )
    (net (code "171") (name "Net-(Q10-B)") (class "Default")
      (node (ref "Q10") (pin "2") (pinfunction "B_2") (pintype "passive"))
      (node (ref "R58") (pin "2") (pinfunction "2_2") (pintype "passive"))
    )
    (net (code "172") (name "Net-(Q10-C)") (class "Default")
      (node (ref "D21") (pin "A") (pinfunction "A_A") (pintype "passive"))
      (node (ref "Q10") (pin "3") (pinfunction "C_3") (pintype "passive"))
      (node (ref "R60") (pin "1") (pinfunction "1_1") (pintype "passive"))
    )
    (net (code "173") (name "Net-(Q11-B)") (class "Default")
      (node (ref "Q11") (pin "2") (pinfunction "B_2") (pintype "passive"))
      (node (ref "R61") (pin "2") (pinfunction "2_2") (pintype "passive"))
    )
    (net (code "174") (name "Net-(Q11-C)") (class "Default")
      (node (ref "D23") (pin "A") (pinfunction "A_A") (pintype "passive"))
      (node (ref "Q11") (pin "3") (pinfunction "C_3") (pintype "passive"))
      (node (ref "R63") (pin "1") (pinfunction "1_1") (pintype "passive"))
      (node (ref "R70") (pin "1") (pinfunction "1_1") (pintype "passive"))
    )
    (net (code "175") (name "Net-(Q12-B)") (class "Default")
      (node (ref "D25") (pin "A") (pinfunction "A_A") (pintype "passive"))
      (node (ref "Q12") (pin "2") (pinfunction "B_2") (pintype "passive"))
      (node (ref "R71") (pin "2") (pinfunction "2_2") (pintype "passive"))
    )
    (net (code "176") (name "Net-(Q12-C)") (class "Default")
      (node (ref "D26") (pin "C") (pinfunction "C_C") (pintype "passive"))
      (node (ref "Q12") (pin "3") (pinfunction "C_3") (pintype "passive"))
      (node (ref "R73") (pin "A") (pinfunction "A_A") (pintype "passive"))
      (node (ref "R74") (pin "A") (pinfunction "A_A") (pintype "passive"))
    )
    (net (code "177") (name "Net-(Q12-E)") (class "Default")
      (node (ref "Q12") (pin "1") (pinfunction "E_1") (pintype "passive"))
      (node (ref "R72") (pin "1") (pinfunction "1_1") (pintype "passive"))
    )
    (net (code "178") (name "Net-(Q13-B)") (class "Default")
      (node (ref "Q13") (pin "2") (pinfunction "B_2") (pintype "passive"))
      (node (ref "R83") (pin "2") (pinfunction "2_2") (pintype "passive"))
    )
    (net (code "179") (name "Net-(Q13-C)") (class "Default")
      (node (ref "C64") (pin "1") (pinfunction "1_1") (pintype "passive"))
      (node (ref "Q13") (pin "3") (pinfunction "C_3") (pintype "passive"))
      (node (ref "R82") (pin "1") (pinfunction "1_1") (pintype "passive"))
    )
    (net (code "180") (name "Net-(Q13-E)") (class "Default")
      (node (ref "Q13") (pin "1") (pinfunction "E_1") (pintype "passive"))
      (node (ref "Q14") (pin "1") (pinfunction "E_1") (pintype "passive"))
      (node (ref "R86") (pin "2") (pinfunction "2_2") (pintype "passive"))
      (node (ref "R87") (pin "1") (pinfunction "1_1") (pintype "passive"))
    )
    (net (code "181") (name "Net-(Q14-B)") (class "Default")
      (node (ref "C63") (pin "2") (pinfunction "2_2") (pintype "passive"))
      (node (ref "Q14") (pin "2") (pinfunction "B_2") (pintype "passive"))
      (node (ref "Q31") (pin "3") (pinfunction "C_3") (pintype "passive"))
      (node (ref "R84") (pin "2") (pinfunction "2_2") (pintype "passive"))
    )
    (net (code "182") (name "Net-(Q14-C)") (class "Default")
      (node (ref "C65") (pin "1") (pinfunction "1_1") (pintype "passive"))
      (node (ref "Q14") (pin "3") (pinfunction "C_3") (pintype "passive"))
      (node (ref "R85") (pin "2") (pinfunction "2_2") (pintype "passive"))
    )
    (net (code "183") (name "Net-(Q15-B)") (class "Default")
      (node (ref "D27") (pin "A") (pinfunction "A_A") (pintype "passive"))
      (node (ref "Q15") (pin "2") (pinfunction "B_2") (pintype "passive"))
      (node (ref "R88") (pin "2") (pinfunction "2_2") (pintype "passive"))
    )
    (net (code "184") (name "Net-(Q15-C)") (class "Default")
      (node (ref "C67") (pin "1") (pinfunction "1_1") (pintype "passive"))
      (node (ref "Q15") (pin "3") (pinfunction "C_3") (pintype "passive"))
      (node (ref "R89") (pin "2") (pinfunction "2_2") (pintype "passive"))
    )
    (net (code "185") (name "Net-(Q15-E)") (class "Default")
      (node (ref "Q15") (pin "1") (pinfunction "E_1") (pintype "passive"))
      (node (ref "R92") (pin "1") (pinfunction "1_1") (pintype "passive"))
    )
    (net (code "186") (name "Net-(Q16-B)") (class "Default")
      (node (ref "D28") (pin "A") (pinfunction "A_A") (pintype "passive"))
      (node (ref "Q16") (pin "2") (pinfunction "B_2") (pintype "passive"))
      (node (ref "R138") (pin "2") (pinfunction "2_2") (pintype "passive"))
    )
    (net (code "187") (name "Net-(Q16-C)") (class "Default")
      (node (ref "C68") (pin "2") (pinfunction "2_2") (pintype "passive"))
      (node (ref "Q16") (pin "3") (pinfunction "C_3") (pintype "passive"))
      (node (ref "R139") (pin "2") (pinfunction "2_2") (pintype "passive"))
    )
    (net (code "188") (name "Net-(Q16-E)") (class "Default")
      (node (ref "Q16") (pin "1") (pinfunction "E_1") (pintype "passive"))
      (node (ref "R137") (pin "1") (pinfunction "1_1") (pintype "passive"))
    )
    (net (code "189") (name "Net-(Q17-B)") (class "Default")
      (node (ref "D29") (pin "C") (pinfunction "C_C") (pintype "passive"))
      (node (ref "Q17") (pin "2") (pinfunction "B_2") (pintype "passive"))
      (node (ref "Q18") (pin "2") (pinfunction "B_2") (pintype "passive"))
      (node (ref "R146") (pin "1") (pinfunction "1_1") (pintype "passive"))
    )
    (net (code "190") (name "Net-(Q17-C)") (class "Default")
      (node (ref "D58") (pin "A") (pinfunction "A_A") (pintype "passive"))
      (node (ref "Q17") (pin "3") (pinfunction "C_3") (pintype "passive"))
      (node (ref "R153") (pin "A") (pinfunction "A_A") (pintype "passive"))
      (node (ref "R153") (pin "S") (pinfunction "S_S") (pintype "passive"))
    )
    (net (code "191") (name "Net-(Q17-E)") (class "Default")
      (node (ref "Q17") (pin "1") (pinfunction "E_1") (pintype "passive"))
      (node (ref "R147") (pin "2") (pinfunction "2_2") (pintype "passive"))
    )
    (net (code "192") (name "Net-(Q18-C)") (class "Default")
      (node (ref "D59") (pin "A") (pinfunction "A_A") (pintype "passive"))
      (node (ref "Q18") (pin "3") (pinfunction "C_3") (pintype "passive"))
      (node (ref "R152") (pin "E") (pinfunction "E_E") (pintype "passive"))
      (node (ref "R152") (pin "S") (pinfunction "S_S") (pintype "passive"))
    )
    (net (code "193") (name "Net-(Q18-E)") (class "Default")
      (node (ref "Q18") (pin "1") (pinfunction "E_1") (pintype "passive"))
      (node (ref "R148") (pin "2") (pinfunction "2_2") (pintype "passive"))
    )
    (net (code "194") (name "Net-(Q19-B)") (class "Default")
      (node (ref "Q19") (pin "2") (pinfunction "B_2") (pintype "passive"))
      (node (ref "R95") (pin "2") (pinfunction "2_2") (pintype "passive"))
    )
    (net (code "195") (name "Net-(Q19-C)") (class "Default")
      (node (ref "D30") (pin "C") (pinfunction "C_C") (pintype "passive"))
      (node (ref "Q19") (pin "3") (pinfunction "C_3") (pintype "passive"))
      (node (ref "R96") (pin "1") (pinfunction "1_1") (pintype "passive"))
      (node (ref "R97") (pin "2") (pinfunction "2_2") (pintype "passive"))
    )
    (net (code "196") (name "Net-(Q20-B)") (class "Default")
      (node (ref "Q20") (pin "2") (pinfunction "B_2") (pintype "passive"))
      (node (ref "R100") (pin "2") (pinfunction "2_2") (pintype "passive"))
    )
    (net (code "197") (name "Net-(Q20-C)") (class "Default")
      (node (ref "D33") (pin "C") (pinfunction "C_C") (pintype "passive"))
      (node (ref "Q20") (pin "3") (pinfunction "C_3") (pintype "passive"))
      (node (ref "R101") (pin "1") (pinfunction "1_1") (pintype "passive"))
      (node (ref "R102") (pin "2") (pinfunction "2_2") (pintype "passive"))
    )
    (net (code "198") (name "Net-(Q21-B)") (class "Default")
      (node (ref "Q21") (pin "2") (pinfunction "B_2") (pintype "passive"))
      (node (ref "R105") (pin "2") (pinfunction "2_2") (pintype "passive"))
    )
    (net (code "199") (name "Net-(Q21-C)") (class "Default")
      (node (ref "D37") (pin "A") (pinfunction "A_A") (pintype "passive"))
      (node (ref "Q21") (pin "3") (pinfunction "C_3") (pintype "passive"))
      (node (ref "R107") (pin "1") (pinfunction "1_1") (pintype "passive"))
    )
    (net (code "200") (name "Net-(Q22-B)") (class "Default")
      (node (ref "Q22") (pin "2") (pinfunction "B_2") (pintype "passive"))
      (node (ref "R108") (pin "2") (pinfunction "2_2") (pintype "passive"))
    )
    (net (code "201") (name "Net-(Q22-C)") (class "Default")
      (node (ref "D39") (pin "A") (pinfunction "A_A") (pintype "passive"))
      (node (ref "Q22") (pin "3") (pinfunction "C_3") (pintype "passive"))
      (node (ref "R110") (pin "1") (pinfunction "1_1") (pintype "passive"))
    )
    (net (code "202") (name "Net-(Q23-B)") (class "Default")
      (node (ref "Q23") (pin "2") (pinfunction "B_2") (pintype "passive"))
      (node (ref "R111") (pin "2") (pinfunction "2_2") (pintype "passive"))
    )
    (net (code "203") (name "Net-(Q23-C)") (class "Default")
      (node (ref "D41") (pin "A") (pinfunction "A_A") (pintype "passive"))
      (node (ref "Q23") (pin "3") (pinfunction "C_3") (pintype "passive"))
      (node (ref "R113") (pin "1") (pinfunction "1_1") (pintype "passive"))
    )
    (net (code "204") (name "Net-(Q24-B)") (class "Default")
      (node (ref "Q24") (pin "2") (pinfunction "B_2") (pintype "passive"))
      (node (ref "R114") (pin "2") (pinfunction "2_2") (pintype "passive"))
    )
    (net (code "205") (name "Net-(Q24-C)") (class "Default")
      (node (ref "D43") (pin "A") (pinfunction "A_A") (pintype "passive"))
      (node (ref "Q24") (pin "3") (pinfunction "C_3") (pintype "passive"))
      (node (ref "R118") (pin "1") (pinfunction "1_1") (pintype "passive"))
    )
    (net (code "206") (name "Net-(Q25-B)") (class "Default")
      (node (ref "Q25") (pin "2") (pinfunction "B_2") (pintype "passive"))
      (node (ref "R119") (pin "2") (pinfunction "2_2") (pintype "passive"))
    )
    (net (code "207") (name "Net-(Q25-C)") (class "Default")
      (node (ref "D45") (pin "A") (pinfunction "A_A") (pintype "passive"))
      (node (ref "Q25") (pin "3") (pinfunction "C_3") (pintype "passive"))
      (node (ref "R122") (pin "1") (pinfunction "1_1") (pintype "passive"))
    )
    (net (code "208") (name "Net-(Q26-B)") (class "Default")
      (node (ref "Q26") (pin "2") (pinfunction "B_2") (pintype "passive"))
      (node (ref "R123") (pin "2") (pinfunction "2_2") (pintype "passive"))
    )
    (net (code "209") (name "Net-(Q26-C)") (class "Default")
      (node (ref "D47") (pin "A") (pinfunction "A_A") (pintype "passive"))
      (node (ref "Q26") (pin "3") (pinfunction "C_3") (pintype "passive"))
      (node (ref "R126") (pin "1") (pinfunction "1_1") (pintype "passive"))
    )
    (net (code "210") (name "Net-(Q27-B)") (class "Default")
      (node (ref "Q27") (pin "2") (pinfunction "B_2") (pintype "passive"))
      (node (ref "R127") (pin "2") (pinfunction "2_2") (pintype "passive"))
    )
    (net (code "211") (name "Net-(Q27-C)") (class "Default")
      (node (ref "D49") (pin "A") (pinfunction "A_A") (pintype "passive"))
      (node (ref "Q27") (pin "3") (pinfunction "C_3") (pintype "passive"))
      (node (ref "R130") (pin "1") (pinfunction "1_1") (pintype "passive"))
    )
    (net (code "212") (name "Net-(Q28-B)") (class "Default")
      (node (ref "Q28") (pin "2") (pinfunction "B_2") (pintype "passive"))
      (node (ref "R131") (pin "2") (pinfunction "2_2") (pintype "passive"))
    )
    (net (code "213") (name "Net-(Q28-C)") (class "Default")
      (node (ref "D51") (pin "A") (pinfunction "A_A") (pintype "passive"))
      (node (ref "Q28") (pin "3") (pinfunction "C_3") (pintype "passive"))
      (node (ref "R134") (pin "1") (pinfunction "1_1") (pintype "passive"))
      (node (ref "R135") (pin "1") (pinfunction "1_1") (pintype "passive"))
    )
    (net (code "214") (name "Net-(Q29-B)") (class "Default")
      (node (ref "D52") (pin "A") (pinfunction "A_A") (pintype "passive"))
      (node (ref "Q29") (pin "2") (pinfunction "B_2") (pintype "passive"))
      (node (ref "R161") (pin "1") (pinfunction "1_1") (pintype "passive"))
    )
    (net (code "215") (name "Net-(Q29-C)") (class "Default")
      (node (ref "C42") (pin "1") (pinfunction "1_1") (pintype "passive"))
      (node (ref "Q29") (pin "3") (pinfunction "C_3") (pintype "passive"))
      (node (ref "R162") (pin "1") (pinfunction "1_1") (pintype "passive"))
    )
    (net (code "216") (name "Net-(Q29-E)") (class "Default")
      (node (ref "Q29") (pin "1") (pinfunction "E_1") (pintype "passive"))
      (node (ref "R156") (pin "1") (pinfunction "1_1") (pintype "passive"))
    )
    (net (code "217") (name "Net-(Q30-B)") (class "Default")
      (node (ref "D53") (pin "A") (pinfunction "A_A") (pintype "passive"))
      (node (ref "Q30") (pin "2") (pinfunction "B_2") (pintype "passive"))
      (node (ref "R159") (pin "2") (pinfunction "2_2") (pintype "passive"))
    )
    (net (code "218") (name "Net-(Q30-C)") (class "Default")
      (node (ref "C73") (pin "2") (pinfunction "2_2") (pintype "passive"))
      (node (ref "Q30") (pin "3") (pinfunction "C_3") (pintype "passive"))
      (node (ref "R160") (pin "2") (pinfunction "2_2") (pintype "passive"))
    )
    (net (code "219") (name "Net-(Q30-E)") (class "Default")
      (node (ref "Q30") (pin "1") (pinfunction "E_1") (pintype "passive"))
      (node (ref "R157") (pin "1") (pinfunction "1_1") (pintype "passive"))
    )
    (net (code "220") (name "Net-(Q31-B)") (class "Default")
      (node (ref "Q31") (pin "2") (pinfunction "B_2") (pintype "passive"))
      (node (ref "R79") (pin "2") (pinfunction "2_2") (pintype "passive"))
    )
    (net (code "221") (name "Net-(R10-Pad1)") (class "Default")
      (node (ref "R10") (pin "1") (pinfunction "1_1") (pintype "passive"))
      (node (ref "W4") (pin "2") (pinfunction "2_2") (pintype "passive"))
    )
    (net (code "222") (name "Net-(R51-Pad2)") (class "Default")
      (node (ref "R51") (pin "2") (pinfunction "2_2") (pintype "passive"))
      (node (ref "R64") (pin "1") (pinfunction "1_1") (pintype "passive"))
    )
    (net (code "223") (name "Net-(R54-Pad2)") (class "Default")
      (node (ref "R54") (pin "2") (pinfunction "2_2") (pintype "passive"))
      (node (ref "R66") (pin "A") (pinfunction "A_A") (pintype "passive"))
      (node (ref "R66") (pin "S") (pinfunction "S_S") (pintype "passive"))
    )
    (net (code "224") (name "Net-(R57-Pad2)") (class "Default")
      (node (ref "R57") (pin "2") (pinfunction "2_2") (pintype "passive"))
      (node (ref "R67") (pin "A") (pinfunction "A_A") (pintype "passive"))
      (node (ref "R67") (pin "S") (pinfunction "S_S") (pintype "passive"))
    )
    (net (code "225") (name "Net-(R60-Pad2)") (class "Default")
      (node (ref "R60") (pin "2") (pinfunction "2_2") (pintype "passive"))
      (node (ref "R68") (pin "A") (pinfunction "A_A") (pintype "passive"))
      (node (ref "R68") (pin "S") (pinfunction "S_S") (pintype "passive"))
    )
    (net (code "226") (name "Net-(R63-Pad2)") (class "Default")
      (node (ref "R63") (pin "2") (pinfunction "2_2") (pintype "passive"))
      (node (ref "R69") (pin "A") (pinfunction "A_A") (pintype "passive"))
      (node (ref "R69") (pin "S") (pinfunction "S_S") (pintype "passive"))
      (node (ref "R70") (pin "2") (pinfunction "2_2") (pintype "passive"))
    )
    (net (code "227") (name "Net-(R64-Pad2)") (class "Default")
      (node (ref "R64") (pin "2") (pinfunction "2_2") (pintype "passive"))
      (node (ref "R65") (pin "A") (pinfunction "A_A") (pintype "passive"))
      (node (ref "R65") (pin "S") (pinfunction "S_S") (pintype "passive"))
      (node (ref "W7") (pin "2") (pinfunction "2_2") (pintype "passive"))
    )
    (net (code "228") (name "Net-(R80-Pad2)") (class "Default")
      (node (ref "R80") (pin "2") (pinfunction "2_2") (pintype "passive"))
      (node (ref "W5") (pin "1") (pinfunction "1_1") (pintype "passive"))
    )
    (net (code "229") (name "Net-(R81-Pad2)") (class "Default")
      (node (ref "R81") (pin "2") (pinfunction "2_2") (pintype "passive"))
      (node (ref "W8") (pin "1") (pinfunction "1_1") (pintype "passive"))
    )
    (net (code "230") (name "Net-(R83-Pad1)") (class "Default")
      (node (ref "R83") (pin "1") (pinfunction "1_1") (pintype "passive"))
      (node (ref "W5") (pin "2") (pinfunction "2_2") (pintype "passive"))
      (node (ref "W8") (pin "2") (pinfunction "2_2") (pintype "passive"))
    )
    (net (code "231") (name "Net-(R116-PadA)") (class "Default")
      (node (ref "R116") (pin "A") (pinfunction "A_A") (pintype "passive"))
      (node (ref "R116") (pin "S") (pinfunction "S_S") (pintype "passive"))
      (node (ref "R117") (pin "2") (pinfunction "2_2") (pintype "passive"))
      (node (ref "W6") (pin "2") (pinfunction "2_2") (pintype "passive"))
    )
    (net (code "232") (name "Net-(R117-Pad1)") (class "Default")
      (node (ref "R117") (pin "1") (pinfunction "1_1") (pintype "passive"))
      (node (ref "R118") (pin "2") (pinfunction "2_2") (pintype "passive"))
    )
    (net (code "233") (name "Net-(R121-PadA)") (class "Default")
      (node (ref "R121") (pin "A") (pinfunction "A_A") (pintype "passive"))
      (node (ref "R121") (pin "S") (pinfunction "S_S") (pintype "passive"))
      (node (ref "R122") (pin "2") (pinfunction "2_2") (pintype "passive"))
    )
    (net (code "234") (name "Net-(R125-PadA)") (class "Default")
      (node (ref "R125") (pin "A") (pinfunction "A_A") (pintype "passive"))
      (node (ref "R125") (pin "S") (pinfunction "S_S") (pintype "passive"))
      (node (ref "R126") (pin "2") (pinfunction "2_2") (pintype "passive"))
    )
    (net (code "235") (name "Net-(R129-PadA)") (class "Default")
      (node (ref "R129") (pin "A") (pinfunction "A_A") (pintype "passive"))
      (node (ref "R129") (pin "S") (pinfunction "S_S") (pintype "passive"))
      (node (ref "R130") (pin "2") (pinfunction "2_2") (pintype "passive"))
    )
    (net (code "236") (name "Net-(R133-PadA)") (class "Default")
      (node (ref "R133") (pin "A") (pinfunction "A_A") (pintype "passive"))
      (node (ref "R133") (pin "S") (pinfunction "S_S") (pintype "passive"))
      (node (ref "R134") (pin "2") (pinfunction "2_2") (pintype "passive"))
      (node (ref "R135") (pin "2") (pinfunction "2_2") (pintype "passive"))
    )
    (net (code "237") (name "Net-(R143-Pad2)") (class "Default")
      (node (ref "R143") (pin "2") (pinfunction "2_2") (pintype "passive"))
      (node (ref "R144") (pin "1") (pinfunction "1_1") (pintype "passive"))
      (node (ref "W9") (pin "1") (pinfunction "1_1") (pintype "passive"))
    )
    (net (code "238") (name "Net-(R145-Pad1)") (class "Default")
      (node (ref "R145") (pin "1") (pinfunction "1_1") (pintype "passive"))
      (node (ref "R152") (pin "A") (pinfunction "A_A") (pintype "passive"))
    )
    (net (code "239") (name "Net-(R149-Pad1)") (class "Default")
      (node (ref "R149") (pin "1") (pinfunction "1_1") (pintype "passive"))
      (node (ref "R153") (pin "E") (pinfunction "E_E") (pintype "passive"))
    )
    (net (code "240") (name "Net-(R154-Pad1)") (class "Default")
      (node (ref "R154") (pin "1") (pinfunction "1_1") (pintype "passive"))
      (node (ref "R155") (pin "2") (pinfunction "2_2") (pintype "passive"))
      (node (ref "W10") (pin "1") (pinfunction "1_1") (pintype "passive"))
    )
    (net (code "241") (name "Net-(S2-A1)") (class "Default")
      (node (ref "C39") (pin "1") (pinfunction "1_1") (pintype "passive"))
      (node (ref "S2") (pin "1") (pinfunction "A1_1") (pintype "bidirectional"))
    )
    (net (code "242") (name "Net-(S2-A3)") (class "Default")
      (node (ref "C38") (pin "1") (pinfunction "1_1") (pintype "passive"))
      (node (ref "S2") (pin "3") (pinfunction "A3_3") (pintype "bidirectional"))
    )
    (net (code "243") (name "RED_DELAY") (class "Default")
      (node (ref "E2") (pin "5") (pinfunction "Q_5") (pintype "output"))
      (node (ref "E3") (pin "2") (pinfunction "I0_2") (pintype "input"))
      (node (ref "E3") (pin "9") (pinfunction "I1_9") (pintype "input"))
      (node (ref "TP1") (pin "TP") (pinfunction "TP_TP") (pintype "input"))
    )
    (net (code "244") (name "SET_DONE") (class "Default")
      (node (ref "E1") (pin "5") (pinfunction "Q_5") (pintype "output"))
      (node (ref "E3") (pin "6") (pinfunction "I1_6") (pintype "input"))
    )
    (net (code "245") (name "STORE") (class "Default")
      (node (ref "E5") (pin "9") (pinfunction "Q_9") (pintype "output"))
      (node (ref "E8") (pin "3") (pinfunction "I1_3") (pintype "input"))
    )
    (net (code "246") (name "TP3") (class "Default")
      (node (ref "E13") (pin "9") (pinfunction "I0_9") (pintype "input"))
      (node (ref "OMNIBUS") (pin "CH2") (pinfunction "1_CH2") (pintype "bidirectional"))
    )
    (net (code "247") (name "VCC") (class "Default")
      (node (ref "C1") (pin "1") (pinfunction "1_1") (pintype "passive"))
      (node (ref "C10") (pin "1") (pinfunction "1_1") (pintype "passive"))
      (node (ref "C11") (pin "1") (pinfunction "1_1") (pintype "passive"))
      (node (ref "C12") (pin "1") (pinfunction "1_1") (pintype "passive"))
      (node (ref "C13") (pin "1") (pinfunction "1_1") (pintype "passive"))
      (node (ref "C14") (pin "1") (pinfunction "1_1") (pintype "passive"))
      (node (ref "C15") (pin "1") (pinfunction "1_1") (pintype "passive"))
      (node (ref "C16") (pin "1") (pinfunction "1_1") (pintype "passive"))
      (node (ref "C17") (pin "1") (pinfunction "1_1") (pintype "passive"))
      (node (ref "C18") (pin "1") (pinfunction "1_1") (pintype "passive"))
      (node (ref "C19") (pin "1") (pinfunction "1_1") (pintype "passive"))
      (node (ref "C2") (pin "1") (pinfunction "1_1") (pintype "passive"))
      (node (ref "C20") (pin "1") (pinfunction "1_1") (pintype "passive"))
      (node (ref "C21") (pin "1") (pinfunction "1_1") (pintype "passive"))
      (node (ref "C22") (pin "1") (pinfunction "1_1") (pintype "passive"))
      (node (ref "C23") (pin "1") (pinfunction "1_1") (pintype "passive"))
      (node (ref "C24") (pin "1") (pinfunction "1_1") (pintype "passive"))
      (node (ref "C25") (pin "1") (pinfunction "1_1") (pintype "passive"))
      (node (ref "C26") (pin "1") (pinfunction "1_1") (pintype "passive"))
      (node (ref "C27") (pin "1") (pinfunction "1_1") (pintype "passive"))
      (node (ref "C28") (pin "1") (pinfunction "1_1") (pintype "passive"))
      (node (ref "C29") (pin "+") (pinfunction "+_+") (pintype "passive"))
      (node (ref "C3") (pin "1") (pinfunction "1_1") (pintype "passive"))
      (node (ref "C30") (pin "+") (pinfunction "+_+") (pintype "passive"))
      (node (ref "C31") (pin "+") (pinfunction "+_+") (pintype "passive"))
      (node (ref "C32") (pin "+") (pinfunction "+_+") (pintype "passive"))
      (node (ref "C4") (pin "1") (pinfunction "1_1") (pintype "passive"))
      (node (ref "C41") (pin "1") (pinfunction "1_1") (pintype "passive"))
      (node (ref "C43") (pin "1") (pinfunction "1_1") (pintype "passive"))
      (node (ref "C44") (pin "1") (pinfunction "1_1") (pintype "passive"))
      (node (ref "C45") (pin "1") (pinfunction "1_1") (pintype "passive"))
      (node (ref "C46") (pin "1") (pinfunction "1_1") (pintype "passive"))
      (node (ref "C47") (pin "1") (pinfunction "1_1") (pintype "passive"))
      (node (ref "C48") (pin "1") (pinfunction "1_1") (pintype "passive"))
      (node (ref "C49") (pin "1") (pinfunction "1_1") (pintype "passive"))
      (node (ref "C5") (pin "1") (pinfunction "1_1") (pintype "passive"))
      (node (ref "C50") (pin "1") (pinfunction "1_1") (pintype "passive"))
      (node (ref "C51") (pin "1") (pinfunction "1_1") (pintype "passive"))
      (node (ref "C52") (pin "1") (pinfunction "1_1") (pintype "passive"))
      (node (ref "C53") (pin "1") (pinfunction "1_1") (pintype "passive"))
      (node (ref "C54") (pin "1") (pinfunction "1_1") (pintype "passive"))
      (node (ref "C55") (pin "+") (pinfunction "+_+") (pintype "passive"))
      (node (ref "C56") (pin "+") (pinfunction "+_+") (pintype "passive"))
      (node (ref "C57") (pin "+") (pinfunction "+_+") (pintype "passive"))
      (node (ref "C6") (pin "1") (pinfunction "1_1") (pintype "passive"))
      (node (ref "C7") (pin "1") (pinfunction "1_1") (pintype "passive"))
      (node (ref "C8") (pin "1") (pinfunction "1_1") (pintype "passive"))
      (node (ref "C9") (pin "1") (pinfunction "1_1") (pintype "passive"))
      (node (ref "OMNIBUS") (pin "AA2") (pinfunction "1_AA2") (pintype "bidirectional"))
      (node (ref "OMNIBUS") (pin "BA2") (pinfunction "1_BA2") (pintype "bidirectional"))
      (node (ref "OMNIBUS") (pin "CA2") (pinfunction "1_CA2") (pintype "bidirectional"))
      (node (ref "OMNIBUS1") (pin "AA2") (pinfunction "1_AA2") (pintype "bidirectional"))
      (node (ref "OMNIBUS1") (pin "BA2") (pinfunction "1_BA2") (pintype "bidirectional"))
      (node (ref "OMNIBUS1") (pin "CA2") (pinfunction "1_CA2") (pintype "bidirectional"))
      (node (ref "Q31") (pin "1") (pinfunction "E_1") (pintype "passive"))
      (node (ref "R1") (pin "2") (pinfunction "2_2") (pintype "passive"))
      (node (ref "R10") (pin "2") (pinfunction "2_2") (pintype "passive"))
      (node (ref "R101") (pin "2") (pinfunction "2_2") (pintype "passive"))
      (node (ref "R11") (pin "2") (pinfunction "2_2") (pintype "passive"))
      (node (ref "R12") (pin "2") (pinfunction "2_2") (pintype "passive"))
      (node (ref "R13") (pin "2") (pinfunction "2_2") (pintype "passive"))
      (node (ref "R15") (pin "2") (pinfunction "2_2") (pintype "passive"))
      (node (ref "R16") (pin "2") (pinfunction "2_2") (pintype "passive"))
      (node (ref "R17") (pin "2") (pinfunction "2_2") (pintype "passive"))
      (node (ref "R18") (pin "2") (pinfunction "2_2") (pintype "passive"))
      (node (ref "R19") (pin "2") (pinfunction "2_2") (pintype "passive"))
      (node (ref "R2") (pin "2") (pinfunction "2_2") (pintype "passive"))
      (node (ref "R20") (pin "2") (pinfunction "2_2") (pintype "passive"))
      (node (ref "R21") (pin "2") (pinfunction "2_2") (pintype "passive"))
      (node (ref "R22") (pin "2") (pinfunction "2_2") (pintype "passive"))
      (node (ref "R23") (pin "2") (pinfunction "2_2") (pintype "passive"))
      (node (ref "R24") (pin "2") (pinfunction "2_2") (pintype "passive"))
      (node (ref "R25") (pin "2") (pinfunction "2_2") (pintype "passive"))
      (node (ref "R26") (pin "2") (pinfunction "2_2") (pintype "passive"))
      (node (ref "R27") (pin "2") (pinfunction "2_2") (pintype "passive"))
      (node (ref "R28") (pin "2") (pinfunction "2_2") (pintype "passive"))
      (node (ref "R29") (pin "2") (pinfunction "2_2") (pintype "passive"))
      (node (ref "R3") (pin "2") (pinfunction "2_2") (pintype "passive"))
      (node (ref "R31") (pin "2") (pinfunction "2_2") (pintype "passive"))
      (node (ref "R36") (pin "2") (pinfunction "2_2") (pintype "passive"))
      (node (ref "R4") (pin "2") (pinfunction "2_2") (pintype "passive"))
      (node (ref "R5") (pin "2") (pinfunction "2_2") (pintype "passive"))
      (node (ref "R6") (pin "2") (pinfunction "2_2") (pintype "passive"))
      (node (ref "R7") (pin "2") (pinfunction "2_2") (pintype "passive"))
      (node (ref "R78") (pin "2") (pinfunction "2_2") (pintype "passive"))
      (node (ref "R8") (pin "2") (pinfunction "2_2") (pintype "passive"))
      (node (ref "R80") (pin "1") (pinfunction "1_1") (pintype "passive"))
      (node (ref "R81") (pin "1") (pinfunction "1_1") (pintype "passive"))
      (node (ref "R82") (pin "2") (pinfunction "2_2") (pintype "passive"))
      (node (ref "R9") (pin "2") (pinfunction "2_2") (pintype "passive"))
      (node (ref "R96") (pin "2") (pinfunction "2_2") (pintype "passive"))
    )
    (net (code "248") (name "WRITE_THRU") (class "Default")
      (node (ref "E10") (pin "9") (pinfunction "I_9") (pintype "input"))
      (node (ref "E5") (pin "5") (pinfunction "Q_5") (pintype "output"))
      (node (ref "E8") (pin "12") (pinfunction "I1_12") (pintype "input"))
    )
    (net (code "249") (name "X02") (class "Default")
      (node (ref "E29") (pin "1") (pinfunction "I_1") (pintype "input"))
      (node (ref "E34") (pin "2") (pinfunction "QB_2") (pintype "output"))
      (node (ref "E41") (pin "6") (pinfunction "A1_6") (pintype "input"))
    )
    (net (code "250") (name "X03") (class "Default")
      (node (ref "E34") (pin "3") (pinfunction "QA_3") (pintype "output"))
      (node (ref "E41") (pin "1") (pinfunction "A0_1") (pintype "input"))
      (node (ref "R58") (pin "1") (pinfunction "1_1") (pintype "passive"))
    )
    (net (code "251") (name "X04") (class "Default")
      (node (ref "E36") (pin "7") (pinfunction "QD_7") (pintype "output"))
      (node (ref "E40") (pin "15") (pinfunction "A3_15") (pintype "input"))
      (node (ref "R55") (pin "1") (pinfunction "1_1") (pintype "passive"))
    )
    (net (code "252") (name "X05") (class "Default")
      (node (ref "E36") (pin "6") (pinfunction "QC_6") (pintype "output"))
      (node (ref "E40") (pin "10") (pinfunction "A2_10") (pintype "input"))
      (node (ref "R52") (pin "1") (pinfunction "1_1") (pintype "passive"))
    )
    (net (code "253") (name "X06") (class "Default")
      (node (ref "E36") (pin "2") (pinfunction "QB_2") (pintype "output"))
      (node (ref "E40") (pin "6") (pinfunction "A1_6") (pintype "input"))
      (node (ref "R49") (pin "1") (pinfunction "1_1") (pintype "passive"))
    )
    (net (code "254") (name "X07") (class "Default")
      (node (ref "E36") (pin "3") (pinfunction "QA_3") (pintype "output"))
      (node (ref "E40") (pin "1") (pinfunction "A0_1") (pintype "input"))
      (node (ref "R46") (pin "1") (pinfunction "1_1") (pintype "passive"))
    )
    (net (code "255") (name "X08") (class "Default")
      (node (ref "E38") (pin "7") (pinfunction "QD_7") (pintype "output"))
      (node (ref "E39") (pin "15") (pinfunction "A3_15") (pintype "input"))
      (node (ref "R43") (pin "1") (pinfunction "1_1") (pintype "passive"))
    )
    (net (code "256") (name "X09") (class "Default")
      (node (ref "E38") (pin "6") (pinfunction "QC_6") (pintype "output"))
      (node (ref "E39") (pin "10") (pinfunction "A2_10") (pintype "input"))
      (node (ref "R40") (pin "1") (pinfunction "1_1") (pintype "passive"))
    )
    (net (code "257") (name "X10") (class "Default")
      (node (ref "E38") (pin "2") (pinfunction "QB_2") (pintype "output"))
      (node (ref "E39") (pin "6") (pinfunction "A1_6") (pintype "input"))
      (node (ref "R35") (pin "1") (pinfunction "1_1") (pintype "passive"))
    )
    (net (code "258") (name "X11") (class "Default")
      (node (ref "E38") (pin "3") (pinfunction "QA_3") (pintype "output"))
      (node (ref "E39") (pin "1") (pinfunction "A0_1") (pintype "input"))
      (node (ref "R30") (pin "1") (pinfunction "1_1") (pintype "passive"))
    )
    (net (code "259") (name "X_ANALOG") (class "Default")
      (node (ref "H1") (pin "C1") (pinfunction "P_C1") (pintype "passive"))
      (node (ref "J2") (pin "D") (pinfunction "4_D") (pintype "bidirectional"))
      (node (ref "R136") (pin "2") (pinfunction "2_2") (pintype "passive"))
    )
    (net (code "260") (name "X_DEC") (class "Default")
      (node (ref "E38") (pin "4") (pinfunction "DN_4") (pintype "input"))
      (node (ref "H1") (pin "H2") (pinfunction "P_H2") (pintype "passive"))
      (node (ref "R27") (pin "1") (pinfunction "1_1") (pintype "passive"))
    )
    (net (code "261") (name "X_INC") (class "Default")
      (node (ref "E38") (pin "5") (pinfunction "UP_5") (pintype "input"))
      (node (ref "H1") (pin "E2") (pinfunction "P_E2") (pintype "passive"))
      (node (ref "R26") (pin "1") (pinfunction "1_1") (pintype "passive"))
    )
    (net (code "262") (name "Y02") (class "Default")
      (node (ref "E29") (pin "13") (pinfunction "I_13") (pintype "input"))
      (node (ref "E29") (pin "3") (pinfunction "I_3") (pintype "input"))
      (node (ref "E33") (pin "2") (pinfunction "QB_2") (pintype "output"))
    )
    (net (code "263") (name "Y03") (class "Default")
      (node (ref "E29") (pin "5") (pinfunction "I_5") (pintype "input"))
      (node (ref "E33") (pin "3") (pinfunction "QA_3") (pintype "output"))
      (node (ref "R127") (pin "1") (pinfunction "1_1") (pintype "passive"))
    )
    (net (code "264") (name "Y04") (class "Default")
      (node (ref "E30") (pin "9") (pinfunction "I_9") (pintype "input"))
      (node (ref "E35") (pin "7") (pinfunction "QD_7") (pintype "output"))
      (node (ref "R123") (pin "1") (pinfunction "1_1") (pintype "passive"))
    )
    (net (code "265") (name "Y05") (class "Default")
      (node (ref "E30") (pin "11") (pinfunction "I_11") (pintype "input"))
      (node (ref "E35") (pin "6") (pinfunction "QC_6") (pintype "output"))
      (node (ref "R119") (pin "1") (pinfunction "1_1") (pintype "passive"))
    )
    (net (code "266") (name "Y06") (class "Default")
      (node (ref "E30") (pin "3") (pinfunction "I_3") (pintype "input"))
      (node (ref "E35") (pin "2") (pinfunction "QB_2") (pintype "output"))
      (node (ref "R114") (pin "1") (pinfunction "1_1") (pintype "passive"))
    )
    (net (code "267") (name "Y07") (class "Default")
      (node (ref "E30") (pin "5") (pinfunction "I_5") (pintype "input"))
      (node (ref "E35") (pin "3") (pinfunction "QA_3") (pintype "output"))
      (node (ref "R111") (pin "1") (pinfunction "1_1") (pintype "passive"))
    )
    (net (code "268") (name "Y08") (class "Default")
      (node (ref "E30") (pin "1") (pinfunction "I_1") (pintype "input"))
      (node (ref "E37") (pin "7") (pinfunction "QD_7") (pintype "output"))
      (node (ref "R108") (pin "1") (pinfunction "1_1") (pintype "passive"))
    )
    (net (code "269") (name "Y09") (class "Default")
      (node (ref "E30") (pin "13") (pinfunction "I_13") (pintype "input"))
      (node (ref "E37") (pin "6") (pinfunction "QC_6") (pintype "output"))
      (node (ref "R105") (pin "1") (pinfunction "1_1") (pintype "passive"))
    )
    (net (code "270") (name "Y10") (class "Default")
      (node (ref "E29") (pin "9") (pinfunction "I_9") (pintype "input"))
      (node (ref "E37") (pin "2") (pinfunction "QB_2") (pintype "output"))
      (node (ref "R100") (pin "1") (pinfunction "1_1") (pintype "passive"))
    )
    (net (code "271") (name "Y11") (class "Default")
      (node (ref "E29") (pin "11") (pinfunction "I_11") (pintype "input"))
      (node (ref "E37") (pin "3") (pinfunction "QA_3") (pintype "output"))
      (node (ref "R95") (pin "1") (pinfunction "1_1") (pintype "passive"))
    )
    (net (code "272") (name "Y_ANALOG") (class "Default")
      (node (ref "H1") (pin "A1") (pinfunction "P_A1") (pintype "passive"))
      (node (ref "J2") (pin "L") (pinfunction "10_L") (pintype "bidirectional"))
      (node (ref "R167") (pin "2") (pinfunction "2_2") (pintype "passive"))
    )
    (net (code "273") (name "Y_DEC") (class "Default")
      (node (ref "E37") (pin "4") (pinfunction "DN_4") (pintype "input"))
      (node (ref "H1") (pin "J2") (pinfunction "P_J2") (pintype "passive"))
      (node (ref "R29") (pin "1") (pinfunction "1_1") (pintype "passive"))
    )
    (net (code "274") (name "Y_INC") (class "Default")
      (node (ref "E37") (pin "5") (pinfunction "UP_5") (pintype "input"))
      (node (ref "H1") (pin "F2") (pinfunction "P_F2") (pintype "passive"))
      (node (ref "R28") (pin "1") (pinfunction "1_1") (pintype "passive"))
    )
    (net (code "275") (name "Z_AXIS") (class "Default")
      (node (ref "J2") (pin "X") (pinfunction "20_X") (pintype "bidirectional"))
      (node (ref "R87") (pin "2") (pinfunction "2_2") (pintype "passive"))
    )
    (net (code "276") (name "Z_PULSE") (class "Default")
      (node (ref "E27") (pin "12") (pinfunction "I0_12") (pintype "input"))
      (node (ref "F") (pin "A2") (pinfunction "P_A2") (pintype "passive"))
      (node (ref "F1") (pin "A2") (pinfunction "P_A2") (pintype "passive"))
      (node (ref "H1") (pin "V2") (pinfunction "P_V2") (pintype "passive"))
      (node (ref "R11") (pin "1") (pinfunction "1_1") (pintype "passive"))
    )
    (net (code "277") (name "unconnected-(E1A-~{Q}-Pad4)") (class "Default")
      (node (ref "E1") (pin "4") (pinfunction "~{Q}_4") (pintype "output"))
    )
    (net (code "278") (name "unconnected-(E2A-~{Q}-Pad4)") (class "Default")
      (node (ref "E2") (pin "4") (pinfunction "~{Q}_4") (pintype "output"))
    )
    (net (code "279") (name "unconnected-(E2B-~{Q}-Pad12)") (class "Default")
      (node (ref "E2") (pin "12") (pinfunction "~{Q}_12") (pintype "output"))
    )
    (net (code "280") (name "unconnected-(E4A-Q-Pad8)") (class "Default")
      (node (ref "E4") (pin "8") (pinfunction "Q_8") (pintype "output"))
    )
    (net (code "281") (name "unconnected-(E5A-~{Q}-Pad6)") (class "Default")
      (node (ref "E5") (pin "6") (pinfunction "~{Q}_6") (pintype "output"))
    )
    (net (code "282") (name "unconnected-(E6A-~{Q}-Pad6)") (class "Default")
      (node (ref "E6") (pin "6") (pinfunction "~{Q}_6") (pintype "output"))
    )
    (net (code "283") (name "unconnected-(E15A-Q-Pad8)") (class "Default")
      (node (ref "E15") (pin "8") (pinfunction "Q_8") (pintype "output"))
    )
    (net (code "284") (name "unconnected-(E18A-~{Q}-Pad6)") (class "Default")
      (node (ref "E18") (pin "6") (pinfunction "~{Q}_6") (pintype "output"))
    )
    (net (code "285") (name "unconnected-(E18B-~{Q}-Pad8)") (class "Default")
      (node (ref "E18") (pin "8") (pinfunction "~{Q}_8") (pintype "output"))
    )
    (net (code "286") (name "unconnected-(E19A-~{Q}-Pad6)") (class "Default")
      (node (ref "E19") (pin "6") (pinfunction "~{Q}_6") (pintype "output"))
    )
    (net (code "287") (name "unconnected-(E25A-8-Pad6)") (class "Default")
      (node (ref "E25") (pin "6") (pinfunction "8_6") (pintype "output"))
    )
    (net (code "288") (name "unconnected-(E25A-9-Pad7)") (class "Default")
      (node (ref "E25") (pin "7") (pinfunction "9_7") (pintype "output"))
    )
    (net (code "289") (name "unconnected-(E33A-BO-Pad13)") (class "Default")
      (node (ref "E33") (pin "13") (pinfunction "BO_13") (pintype "output"))
    )
    (net (code "290") (name "unconnected-(E33A-CO-Pad12)") (class "Default")
      (node (ref "E33") (pin "12") (pinfunction "CO_12") (pintype "output"))
    )
    (net (code "291") (name "unconnected-(E33A-QC-Pad6)") (class "Default")
      (node (ref "E33") (pin "6") (pinfunction "QC_6") (pintype "output"))
    )
    (net (code "292") (name "unconnected-(E33A-QD-Pad7)") (class "Default")
      (node (ref "E33") (pin "7") (pinfunction "QD_7") (pintype "output"))
    )
    (net (code "293") (name "unconnected-(E34A-BO-Pad13)") (class "Default")
      (node (ref "E34") (pin "13") (pinfunction "BO_13") (pintype "output"))
    )
    (net (code "294") (name "unconnected-(E34A-CO-Pad12)") (class "Default")
      (node (ref "E34") (pin "12") (pinfunction "CO_12") (pintype "output"))
    )
    (net (code "295") (name "unconnected-(E34A-QC-Pad6)") (class "Default")
      (node (ref "E34") (pin "6") (pinfunction "QC_6") (pintype "output"))
    )
    (net (code "296") (name "unconnected-(E34A-QD-Pad7)") (class "Default")
      (node (ref "E34") (pin "7") (pinfunction "QD_7") (pintype "output"))
    )
    (net (code "297") (name "unconnected-(E41A-A2-Pad10)") (class "Default")
      (node (ref "E41") (pin "10") (pinfunction "A2_10") (pintype "input"))
    )
    (net (code "298") (name "unconnected-(E41A-A3-Pad15)") (class "Default")
      (node (ref "E41") (pin "15") (pinfunction "A3_15") (pintype "input"))
    )
    (net (code "299") (name "unconnected-(E41A-B2-Pad11)") (class "Default")
      (node (ref "E41") (pin "11") (pinfunction "B2_11") (pintype "input"))
    )
    (net (code "300") (name "unconnected-(E41A-B3-Pad14)") (class "Default")
      (node (ref "E41") (pin "14") (pinfunction "B3_14") (pintype "input"))
    )
    (net (code "301") (name "unconnected-(E41A-F2-Pad12)") (class "Default")
      (node (ref "E41") (pin "12") (pinfunction "F2_12") (pintype "open_collector"))
    )
    (net (code "302") (name "unconnected-(E41A-F3-Pad13)") (class "Default")
      (node (ref "E41") (pin "13") (pinfunction "F3_13") (pintype "open_collector"))
    )
    (net (code "303") (name "unconnected-(E42--IN-Pad2)") (class "Default")
      (node (ref "E42") (pin "2") (pinfunction "-IN_2") (pintype "input"))
    )
    (net (code "304") (name "unconnected-(E42-ON1-Pad1)") (class "Default")
      (node (ref "E42") (pin "1") (pinfunction "ON1_1") (pintype "passive"))
    )
    (net (code "305") (name "unconnected-(E42-ON2-Pad8)") (class "Default")
      (node (ref "E42") (pin "8") (pinfunction "ON2_8") (pintype "passive"))
    )
    (net (code "306") (name "unconnected-(E42-OPT-Pad5)") (class "Default")
      (node (ref "E42") (pin "5") (pinfunction "OPT_5") (pintype "passive"))
    )
    (net (code "307") (name "unconnected-(E43--IN-Pad2)") (class "Default")
      (node (ref "E43") (pin "2") (pinfunction "-IN_2") (pintype "input"))
    )
    (net (code "308") (name "unconnected-(E43-ON1-Pad1)") (class "Default")
      (node (ref "E43") (pin "1") (pinfunction "ON1_1") (pintype "passive"))
    )
    (net (code "309") (name "unconnected-(E43-ON2-Pad8)") (class "Default")
      (node (ref "E43") (pin "8") (pinfunction "ON2_8") (pintype "passive"))
    )
    (net (code "310") (name "unconnected-(E43-OPT-Pad5)") (class "Default")
      (node (ref "E43") (pin "5") (pinfunction "OPT_5") (pintype "passive"))
    )
    (net (code "311") (name "unconnected-(J2-2-PadB)") (class "Default")
      (node (ref "J2") (pin "B") (pinfunction "2_B") (pintype "bidirectional"))
    )
    (net (code "312") (name "unconnected-(J2-14-PadR)") (class "Default")
      (node (ref "J2") (pin "R") (pinfunction "14_R") (pintype "bidirectional"))
    )
    (net (code "313") (name "unconnected-(J2-16-PadT)") (class "Default")
      (node (ref "J2") (pin "T") (pinfunction "16_T") (pintype "bidirectional"))
    )
    (net (code "314") (name "unconnected-(J2-36-PadRR)") (class "Default")
      (node (ref "J2") (pin "RR") (pinfunction "36_RR") (pintype "bidirectional"))
    )
    (net (code "315") (name "unconnected-(J2-38-PadTT)") (class "Default")
      (node (ref "J2") (pin "TT") (pinfunction "38_TT") (pintype "bidirectional"))
    )
    (net (code "316") (name "unconnected-(J2-40-PadVV)") (class "Default")
      (node (ref "J2") (pin "VV") (pinfunction "40_VV") (pintype "bidirectional"))
    )
    (net (code "317") (name "~{BTP3}") (class "Default")
      (node (ref "E13") (pin "14") (pinfunction "O_14") (pintype "output"))
      (node (ref "E14") (pin "9") (pinfunction "I_9") (pintype "input"))
      (node (ref "E20") (pin "12") (pinfunction "I1_12") (pintype "input"))
      (node (ref "E20") (pin "3") (pinfunction "I1_3") (pintype "input"))
    )
    (net (code "318") (name "~{B_DICD}") (class "Default")
      (node (ref "E22") (pin "3") (pinfunction "O_3") (pintype "output"))
      (node (ref "E23") (pin "5") (pinfunction "I3_5") (pintype "input"))
    )
    (net (code "319") (name "~{B_DIXY}") (class "Default")
      (node (ref "E15") (pin "1") (pinfunction "P$1_1") (pintype "input"))
      (node (ref "E15") (pin "2") (pinfunction "P$2_2") (pintype "input"))
      (node (ref "E22") (pin "6") (pinfunction "O_6") (pintype "output"))
      (node (ref "E23") (pin "4") (pinfunction "I2_4") (pintype "input"))
    )
    (net (code "320") (name "~{B_LOAD_EN}") (class "Default")
      (node (ref "E23") (pin "2") (pinfunction "I1_2") (pintype "input"))
      (node (ref "E26") (pin "11") (pinfunction "O_11") (pintype "output"))
    )
    (net (code "321") (name "~{C0}") (class "Default")
      (node (ref "E16") (pin "10") (pinfunction "O_10") (pintype "open_collector"))
      (node (ref "OMNIBUS") (pin "CE1") (pinfunction "1_CE1") (pintype "bidirectional"))
    )
    (net (code "322") (name "~{C1}") (class "Default")
      (node (ref "E16") (pin "13") (pinfunction "O_13") (pintype "open_collector"))
      (node (ref "OMNIBUS") (pin "CH1") (pinfunction "1_CH1") (pintype "bidirectional"))
    )
    (net (code "323") (name "~{CHAN}") (class "Default")
      (node (ref "E28") (pin "2") (pinfunction "O_2") (pintype "open_collector"))
      (node (ref "F") (pin "R1") (pinfunction "P_R1") (pintype "passive"))
      (node (ref "F1") (pin "R1") (pinfunction "P_R1") (pintype "passive"))
      (node (ref "H1") (pin "E1") (pinfunction "P_E1") (pintype "passive"))
      (node (ref "J2") (pin "Z") (pinfunction "22_Z") (pintype "bidirectional"))
      (node (ref "R12") (pin "1") (pinfunction "1_1") (pintype "passive"))
    )
    (net (code "324") (name "~{CLEAR_DONE}") (class "Default")
      (node (ref "E26") (pin "10") (pinfunction "I1_10") (pintype "input"))
      (node (ref "E3") (pin "13") (pinfunction "O_13") (pintype "output"))
    )
    (net (code "325") (name "~{CLEAR}") (class "Default")
      (node (ref "E18") (pin "1") (pinfunction "CLR_1") (pintype "input"))
      (node (ref "E18") (pin "13") (pinfunction "CLR_13") (pintype "input"))
      (node (ref "E23") (pin "1") (pinfunction "I0_1") (pintype "input"))
      (node (ref "E28") (pin "6") (pinfunction "O_6") (pintype "open_collector"))
      (node (ref "E5") (pin "1") (pinfunction "CLR_1") (pintype "input"))
      (node (ref "E5") (pin "13") (pinfunction "CLR_13") (pintype "input"))
      (node (ref "E6") (pin "13") (pinfunction "CLR_13") (pintype "input"))
      (node (ref "R5") (pin "1") (pinfunction "1_1") (pintype "passive"))
    )
    (net (code "326") (name "~{CL_DONE}") (class "Default")
      (node (ref "E19") (pin "1") (pinfunction "CLR_1") (pintype "input"))
      (node (ref "E23") (pin "6") (pinfunction "O_6") (pintype "output"))
    )
    (net (code "327") (name "~{COLOR}") (class "Default")
      (node (ref "E10") (pin "11") (pinfunction "I_11") (pintype "input"))
      (node (ref "E2") (pin "2") (pinfunction "B_2") (pintype "input"))
      (node (ref "E6") (pin "8") (pinfunction "~{Q}_8") (pintype "output"))
      (node (ref "E7") (pin "6") (pinfunction "I1_6") (pintype "input"))
    )
    (net (code "328") (name "~{COL_RED}") (class "Default")
      (node (ref "E7") (pin "1") (pinfunction "O_1") (pintype "open_collector"))
      (node (ref "F") (pin "L1") (pinfunction "P_L1") (pintype "passive"))
      (node (ref "F1") (pin "L1") (pinfunction "P_L1") (pintype "passive"))
      (node (ref "J2") (pin "DD") (pinfunction "26_DD") (pintype "bidirectional"))
      (node (ref "R21") (pin "1") (pinfunction "1_1") (pintype "passive"))
    )
    (net (code "329") (name "~{DATA00}") (class "Default")
      (node (ref "E17") (pin "13") (pinfunction "O_13") (pintype "open_collector"))
      (node (ref "OMNIBUS") (pin "AR1") (pinfunction "1_AR1") (pintype "bidirectional"))
    )
    (net (code "330") (name "~{DATA02}") (class "Default")
      (node (ref "E31") (pin "7") (pinfunction "I1_7") (pintype "input"))
      (node (ref "E41") (pin "4") (pinfunction "F1_4") (pintype "open_collector"))
      (node (ref "OMNIBUS1") (pin "AU1") (pinfunction "1_AU1") (pintype "bidirectional"))
    )
    (net (code "331") (name "~{DATA03}") (class "Default")
      (node (ref "E31") (pin "4") (pinfunction "I0_4") (pintype "input"))
      (node (ref "E41") (pin "3") (pinfunction "F0_3") (pintype "open_collector"))
      (node (ref "OMNIBUS1") (pin "AV1") (pinfunction "1_AV1") (pintype "bidirectional"))
    )
    (net (code "332") (name "~{DATA04}") (class "Default")
      (node (ref "E32") (pin "4") (pinfunction "I0_4") (pintype "input"))
      (node (ref "E40") (pin "13") (pinfunction "F3_13") (pintype "open_collector"))
      (node (ref "OMNIBUS1") (pin "BR1") (pinfunction "1_BR1") (pintype "bidirectional"))
    )
    (net (code "333") (name "~{DATA05}") (class "Default")
      (node (ref "E32") (pin "7") (pinfunction "I1_7") (pintype "input"))
      (node (ref "E40") (pin "12") (pinfunction "F2_12") (pintype "open_collector"))
      (node (ref "OMNIBUS1") (pin "BS1") (pinfunction "1_BS1") (pintype "bidirectional"))
    )
    (net (code "334") (name "~{DATA06}") (class "Default")
      (node (ref "E32") (pin "10") (pinfunction "I1_10") (pintype "input"))
      (node (ref "E40") (pin "4") (pinfunction "F1_4") (pintype "open_collector"))
      (node (ref "E8") (pin "13") (pinfunction "O_13") (pintype "open_collector"))
      (node (ref "E9") (pin "9") (pinfunction "I0_9") (pintype "input"))
      (node (ref "OMNIBUS") (pin "BU1") (pinfunction "1_BU1") (pintype "bidirectional"))
      (node (ref "OMNIBUS1") (pin "BU1") (pinfunction "1_BU1") (pintype "bidirectional"))
    )
    (net (code "335") (name "~{DATA07}") (class "Default")
      (node (ref "E32") (pin "12") (pinfunction "I1_12") (pintype "input"))
      (node (ref "E40") (pin "3") (pinfunction "F0_3") (pintype "open_collector"))
      (node (ref "E8") (pin "1") (pinfunction "O_1") (pintype "open_collector"))
      (node (ref "E9") (pin "7") (pinfunction "I1_7") (pintype "input"))
      (node (ref "OMNIBUS") (pin "BV1") (pinfunction "1_BV1") (pintype "bidirectional"))
      (node (ref "OMNIBUS1") (pin "BV1") (pinfunction "1_BV1") (pintype "bidirectional"))
    )
    (net (code "336") (name "~{DATA08}") (class "Default")
      (node (ref "E31") (pin "12") (pinfunction "I1_12") (pintype "input"))
      (node (ref "E39") (pin "13") (pinfunction "F3_13") (pintype "open_collector"))
      (node (ref "E9") (pin "4") (pinfunction "I0_4") (pintype "input"))
      (node (ref "OMNIBUS") (pin "DR1") (pinfunction "1_DR1") (pintype "bidirectional"))
      (node (ref "OMNIBUS1") (pin "DR1") (pinfunction "1_DR1") (pintype "bidirectional"))
    )
    (net (code "337") (name "~{DATA09}") (class "Default")
      (node (ref "E31") (pin "9") (pinfunction "I0_9") (pintype "input"))
      (node (ref "E39") (pin "12") (pinfunction "F2_12") (pintype "open_collector"))
      (node (ref "E8") (pin "10") (pinfunction "O_10") (pintype "open_collector"))
      (node (ref "E9") (pin "12") (pinfunction "I1_12") (pintype "input"))
      (node (ref "OMNIBUS") (pin "DS1") (pinfunction "1_DS1") (pintype "bidirectional"))
      (node (ref "OMNIBUS1") (pin "DS1") (pinfunction "1_DS1") (pintype "bidirectional"))
    )
    (net (code "338") (name "~{DATA10}") (class "Default")
      (node (ref "E13") (pin "4") (pinfunction "I0_4") (pintype "input"))
      (node (ref "E16") (pin "1") (pinfunction "O_1") (pintype "open_collector"))
      (node (ref "E39") (pin "3") (pinfunction "F0_3") (pintype "open_collector"))
      (node (ref "OMNIBUS") (pin "DU1") (pinfunction "1_DU1") (pintype "bidirectional"))
      (node (ref "OMNIBUS1") (pin "DU1") (pinfunction "1_DU1") (pintype "bidirectional"))
    )
    (net (code "339") (name "~{DATA11}") (class "Default")
      (node (ref "E13") (pin "6") (pinfunction "I0_6") (pintype "input"))
      (node (ref "E16") (pin "4") (pinfunction "O_4") (pintype "open_collector"))
      (node (ref "E39") (pin "4") (pinfunction "F1_4") (pintype "open_collector"))
      (node (ref "OMNIBUS") (pin "DV1") (pinfunction "1_DV1") (pintype "bidirectional"))
      (node (ref "OMNIBUS1") (pin "DV1") (pinfunction "1_DV1") (pintype "bidirectional"))
    )
    (net (code "340") (name "~{DEL_1}") (class "Default")
      (node (ref "E15") (pin "6") (pinfunction "~{Q}_6") (pintype "output"))
      (node (ref "E23") (pin "9") (pinfunction "I0_9") (pintype "input"))
      (node (ref "E27") (pin "13") (pinfunction "I1_13") (pintype "input"))
    )
    (net (code "341") (name "~{DICD}") (class "Default")
      (node (ref "E21") (pin "3") (pinfunction "I_3") (pintype "input"))
      (node (ref "E25") (pin "12") (pinfunction "1_12") (pintype "output"))
    )
    (net (code "342") (name "~{DICL}") (class "Default")
      (node (ref "E20") (pin "11") (pinfunction "I0_11") (pintype "input"))
      (node (ref "E25") (pin "13") (pinfunction "0_13") (pintype "output"))
    )
    (net (code "343") (name "~{DILE}") (class "Default")
      (node (ref "E20") (pin "2") (pinfunction "I0_2") (pintype "input"))
      (node (ref "E25") (pin "4") (pinfunction "6_4") (pintype "output"))
      (node (ref "E26") (pin "1") (pinfunction "I0_1") (pintype "input"))
      (node (ref "E26") (pin "4") (pinfunction "I0_4") (pintype "input"))
      (node (ref "F") (pin "P1") (pinfunction "P_P1") (pintype "passive"))
      (node (ref "F1") (pin "P1") (pinfunction "P_P1") (pintype "passive"))
      (node (ref "H1") (pin "F1") (pinfunction "P_F1") (pintype "passive"))
    )
    (net (code "344") (name "~{DILX}") (class "Default")
      (node (ref "E21") (pin "11") (pinfunction "I_11") (pintype "input"))
      (node (ref "E25") (pin "10") (pinfunction "3_10") (pintype "output"))
    )
    (net (code "345") (name "~{DILY}") (class "Default")
      (node (ref "E21") (pin "9") (pinfunction "I_9") (pintype "input"))
      (node (ref "E25") (pin "9") (pinfunction "4_9") (pintype "output"))
    )
    (net (code "346") (name "~{DIRE}") (class "Default")
      (node (ref "E21") (pin "13") (pinfunction "I_13") (pintype "input"))
      (node (ref "E25") (pin "5") (pinfunction "7_5") (pintype "output"))
      (node (ref "E26") (pin "2") (pinfunction "I1_2") (pintype "input"))
      (node (ref "F") (pin "B2") (pinfunction "P_B2") (pintype "passive"))
      (node (ref "F1") (pin "B2") (pinfunction "P_B2") (pintype "passive"))
      (node (ref "H1") (pin "U2") (pinfunction "P_U2") (pintype "passive"))
    )
    (net (code "347") (name "~{DISD}") (class "Default")
      (node (ref "E21") (pin "5") (pinfunction "I_5") (pintype "input"))
      (node (ref "E25") (pin "11") (pinfunction "2_11") (pintype "output"))
    )
    (net (code "348") (name "~{DIXY}") (class "Default")
      (node (ref "E21") (pin "1") (pinfunction "I_1") (pintype "input"))
      (node (ref "E25") (pin "3") (pinfunction "5_3") (pintype "output"))
    )
    (net (code "349") (name "~{DLY_DONE}") (class "Default")
      (node (ref "E23") (pin "12") (pinfunction "I2_12") (pintype "input"))
      (node (ref "E3") (pin "1") (pinfunction "O_1") (pintype "output"))
    )
    (net (code "350") (name "~{ERASE_INTERVAL}") (class "Default")
      (node (ref "F") (pin "D2") (pinfunction "P_D2") (pintype "passive"))
      (node (ref "F1") (pin "D2") (pinfunction "P_D2") (pintype "passive"))
      (node (ref "J2") (pin "NN") (pinfunction "34_NN") (pintype "bidirectional"))
      (node (ref "R14") (pin "1") (pinfunction "1_1") (pintype "passive"))
    )
    (net (code "351") (name "~{ERASE}") (class "Default")
      (node (ref "E10") (pin "4") (pinfunction "O_4") (pintype "open_collector"))
      (node (ref "F") (pin "K1") (pinfunction "P_K1") (pintype "passive"))
      (node (ref "F1") (pin "K1") (pinfunction "P_K1") (pintype "passive"))
      (node (ref "J2") (pin "FF") (pinfunction "28_FF") (pintype "bidirectional"))
    )
    (net (code "352") (name "~{INTERNAL_IO}") (class "Default")
      (node (ref "E17") (pin "10") (pinfunction "O_10") (pintype "open_collector"))
      (node (ref "OMNIBUS") (pin "CL1") (pinfunction "1_CL1") (pintype "bidirectional"))
    )
    (net (code "353") (name "~{INTERRUPT}") (class "Default")
      (node (ref "E17") (pin "4") (pinfunction "O_4") (pintype "open_collector"))
      (node (ref "OMNIBUS") (pin "CP1") (pinfunction "1_CP1") (pintype "bidirectional"))
    )
    (net (code "354") (name "~{IOT}") (class "Default")
      (node (ref "E24") (pin "12") (pinfunction "I1_12") (pintype "input"))
      (node (ref "E24") (pin "5") (pinfunction "I1_5") (pintype "input"))
      (node (ref "E24") (pin "6") (pinfunction "I0_6") (pintype "input"))
      (node (ref "E25") (pin "2") (pinfunction "D_2") (pintype "input"))
      (node (ref "E28") (pin "10") (pinfunction "O_10") (pintype "open_collector"))
      (node (ref "R2") (pin "1") (pinfunction "1_1") (pintype "passive"))
    )
    (net (code "355") (name "~{LD_DEL}") (class "Default")
      (node (ref "E23") (pin "13") (pinfunction "I3_13") (pintype "input"))
      (node (ref "E4") (pin "6") (pinfunction "~{Q}_6") (pintype "output"))
    )
    (net (code "356") (name "~{LOAD_DATA}") (class "Default")
      (node (ref "E13") (pin "5") (pinfunction "I1_5") (pintype "input"))
      (node (ref "E13") (pin "7") (pinfunction "I1_7") (pintype "input"))
      (node (ref "E28") (pin "12") (pinfunction "O_12") (pintype "open_collector"))
      (node (ref "E9") (pin "10") (pinfunction "I1_10") (pintype "input"))
      (node (ref "E9") (pin "11") (pinfunction "I0_11") (pintype "input"))
      (node (ref "E9") (pin "5") (pinfunction "I1_5") (pintype "input"))
      (node (ref "E9") (pin "6") (pinfunction "I0_6") (pintype "input"))
      (node (ref "R6") (pin "1") (pinfunction "1_1") (pintype "passive"))
    )
    (net (code "357") (name "~{LOAD_EN}") (class "Default")
      (node (ref "E20") (pin "10") (pinfunction "O_10") (pintype "output"))
      (node (ref "E26") (pin "5") (pinfunction "I1_5") (pintype "input"))
      (node (ref "E26") (pin "9") (pinfunction "I0_9") (pintype "input"))
      (node (ref "E31") (pin "10") (pinfunction "I1_10") (pintype "input"))
      (node (ref "E31") (pin "11") (pinfunction "I0_11") (pintype "input"))
      (node (ref "E31") (pin "5") (pinfunction "I1_5") (pintype "input"))
      (node (ref "E31") (pin "6") (pinfunction "I0_6") (pintype "input"))
      (node (ref "E32") (pin "11") (pinfunction "I0_11") (pintype "input"))
      (node (ref "E32") (pin "5") (pinfunction "I1_5") (pintype "input"))
      (node (ref "E32") (pin "6") (pinfunction "I0_6") (pintype "input"))
      (node (ref "E32") (pin "9") (pinfunction "I0_9") (pintype "input"))
      (node (ref "E4") (pin "1") (pinfunction "P$1_1") (pintype "input"))
      (node (ref "E4") (pin "2") (pinfunction "P$2_2") (pintype "input"))
      (node (ref "F") (pin "V1") (pinfunction "P_V1") (pintype "passive"))
      (node (ref "F1") (pin "V1") (pinfunction "P_V1") (pintype "passive"))
      (node (ref "R23") (pin "1") (pinfunction "1_1") (pintype "passive"))
    )
    (net (code "358") (name "~{MD3}") (class "Default")
      (node (ref "E11") (pin "12") (pinfunction "I1_12") (pintype "input"))
      (node (ref "OMNIBUS") (pin "AP1") (pinfunction "1_AP1") (pintype "bidirectional"))
    )
    (net (code "359") (name "~{MD4}") (class "Default")
      (node (ref "E11") (pin "9") (pinfunction "I0_9") (pintype "input"))
      (node (ref "OMNIBUS") (pin "BK1") (pinfunction "1_BK1") (pintype "bidirectional"))
    )
    (net (code "360") (name "~{MD5}") (class "Default")
      (node (ref "E11") (pin "4") (pinfunction "I0_4") (pintype "input"))
      (node (ref "OMNIBUS") (pin "BL1") (pinfunction "1_BL1") (pintype "bidirectional"))
      (node (ref "W2") (pin "1") (pinfunction "1_1") (pintype "passive"))
    )
    (net (code "361") (name "~{MD6}") (class "Default")
      (node (ref "E12") (pin "11") (pinfunction "I5_11") (pintype "input"))
      (node (ref "OMNIBUS") (pin "BM1") (pinfunction "1_BM1") (pintype "bidirectional"))
    )
    (net (code "362") (name "~{MD7}") (class "Default")
      (node (ref "E11") (pin "7") (pinfunction "I1_7") (pintype "input"))
      (node (ref "OMNIBUS") (pin "BP1") (pinfunction "1_BP1") (pintype "bidirectional"))
    )
    (net (code "363") (name "~{MD8}") (class "Default")
      (node (ref "E12") (pin "12") (pinfunction "I6_12") (pintype "input"))
      (node (ref "OMNIBUS") (pin "DK1") (pinfunction "1_DK1") (pintype "bidirectional"))
    )
    (net (code "364") (name "~{MD9}") (class "Default")
      (node (ref "E24") (pin "11") (pinfunction "I0_11") (pintype "input"))
      (node (ref "OMNIBUS") (pin "DL1") (pinfunction "1_DL1") (pintype "bidirectional"))
    )
    (net (code "365") (name "~{MD10}") (class "Default")
      (node (ref "E24") (pin "7") (pinfunction "I1_7") (pintype "input"))
      (node (ref "OMNIBUS") (pin "DM1") (pinfunction "1_DM1") (pintype "bidirectional"))
    )
    (net (code "366") (name "~{MD11}") (class "Default")
      (node (ref "E24") (pin "4") (pinfunction "I0_4") (pintype "input"))
      (node (ref "OMNIBUS") (pin "DP1") (pinfunction "1_DP1") (pintype "bidirectional"))
    )
    (net (code "367") (name "~{NON_STORE}") (class "Default")
      (node (ref "E10") (pin "12") (pinfunction "O_12") (pintype "open_collector"))
      (node (ref "F") (pin "C2") (pinfunction "P_C2") (pintype "passive"))
      (node (ref "F1") (pin "C2") (pinfunction "P_C2") (pintype "passive"))
      (node (ref "J2") (pin "LL") (pinfunction "32_LL") (pintype "bidirectional"))
    )
    (net (code "368") (name "~{PAUSE}") (class "Default")
      (node (ref "E13") (pin "12") (pinfunction "I1_12") (pintype "input"))
      (node (ref "OMNIBUS") (pin "CD1") (pinfunction "1_CD1") (pintype "bidirectional"))
    )
    (net (code "369") (name "~{SET_DONE}") (class "Default")
      (node (ref "E1") (pin "12") (pinfunction "~{Q}_12") (pintype "output"))
      (node (ref "E23") (pin "10") (pinfunction "I1_10") (pintype "input"))
    )
    (net (code "370") (name "~{SKIP}") (class "Default")
      (node (ref "E17") (pin "1") (pinfunction "O_1") (pintype "open_collector"))
      (node (ref "OMNIBUS") (pin "CS1") (pinfunction "1_CS1") (pintype "bidirectional"))
    )
    (net (code "371") (name "~{STORE}") (class "Default")
      (node (ref "E10") (pin "13") (pinfunction "I_13") (pintype "input"))
      (node (ref "E5") (pin "8") (pinfunction "~{Q}_8") (pintype "output"))
      (node (ref "E7") (pin "5") (pinfunction "I0_5") (pintype "input"))
    )
    (net (code "372") (name "~{WRITE_THRU}") (class "Default")
      (node (ref "E10") (pin "8") (pinfunction "O_8") (pintype "open_collector"))
      (node (ref "F") (pin "M1") (pinfunction "P_M1") (pintype "passive"))
      (node (ref "F1") (pin "M1") (pinfunction "P_M1") (pintype "passive"))
      (node (ref "J2") (pin "JJ") (pinfunction "30_JJ") (pintype "bidirectional"))
    )
    (net (code "373") (name "~{X_AC}") (class "Default")
      (node (ref "E39") (pin "7") (pinfunction "S1_7") (pintype "input"))
      (node (ref "E40") (pin "7") (pinfunction "S1_7") (pintype "input"))
      (node (ref "E41") (pin "7") (pinfunction "S1_7") (pintype "input"))
      (node (ref "H1") (pin "K2") (pinfunction "P_K2") (pintype "passive"))
      (node (ref "R24") (pin "1") (pinfunction "1_1") (pintype "passive"))
    )
    (net (code "374") (name "~{Y_AC}") (class "Default")
      (node (ref "E39") (pin "9") (pinfunction "S0_9") (pintype "input"))
      (node (ref "E40") (pin "9") (pinfunction "S0_9") (pintype "input"))
      (node (ref "E41") (pin "9") (pinfunction "S0_9") (pintype "input"))
      (node (ref "H1") (pin "L2") (pinfunction "P_L2") (pintype "passive"))
      (node (ref "R25") (pin "1") (pinfunction "1_1") (pintype "passive"))
    )
  )
)
